# SCH_Aladdin_Flight_Controller_FC-H7_Easy.net
KiCad netlist of a schematic drawn in EasyEDA
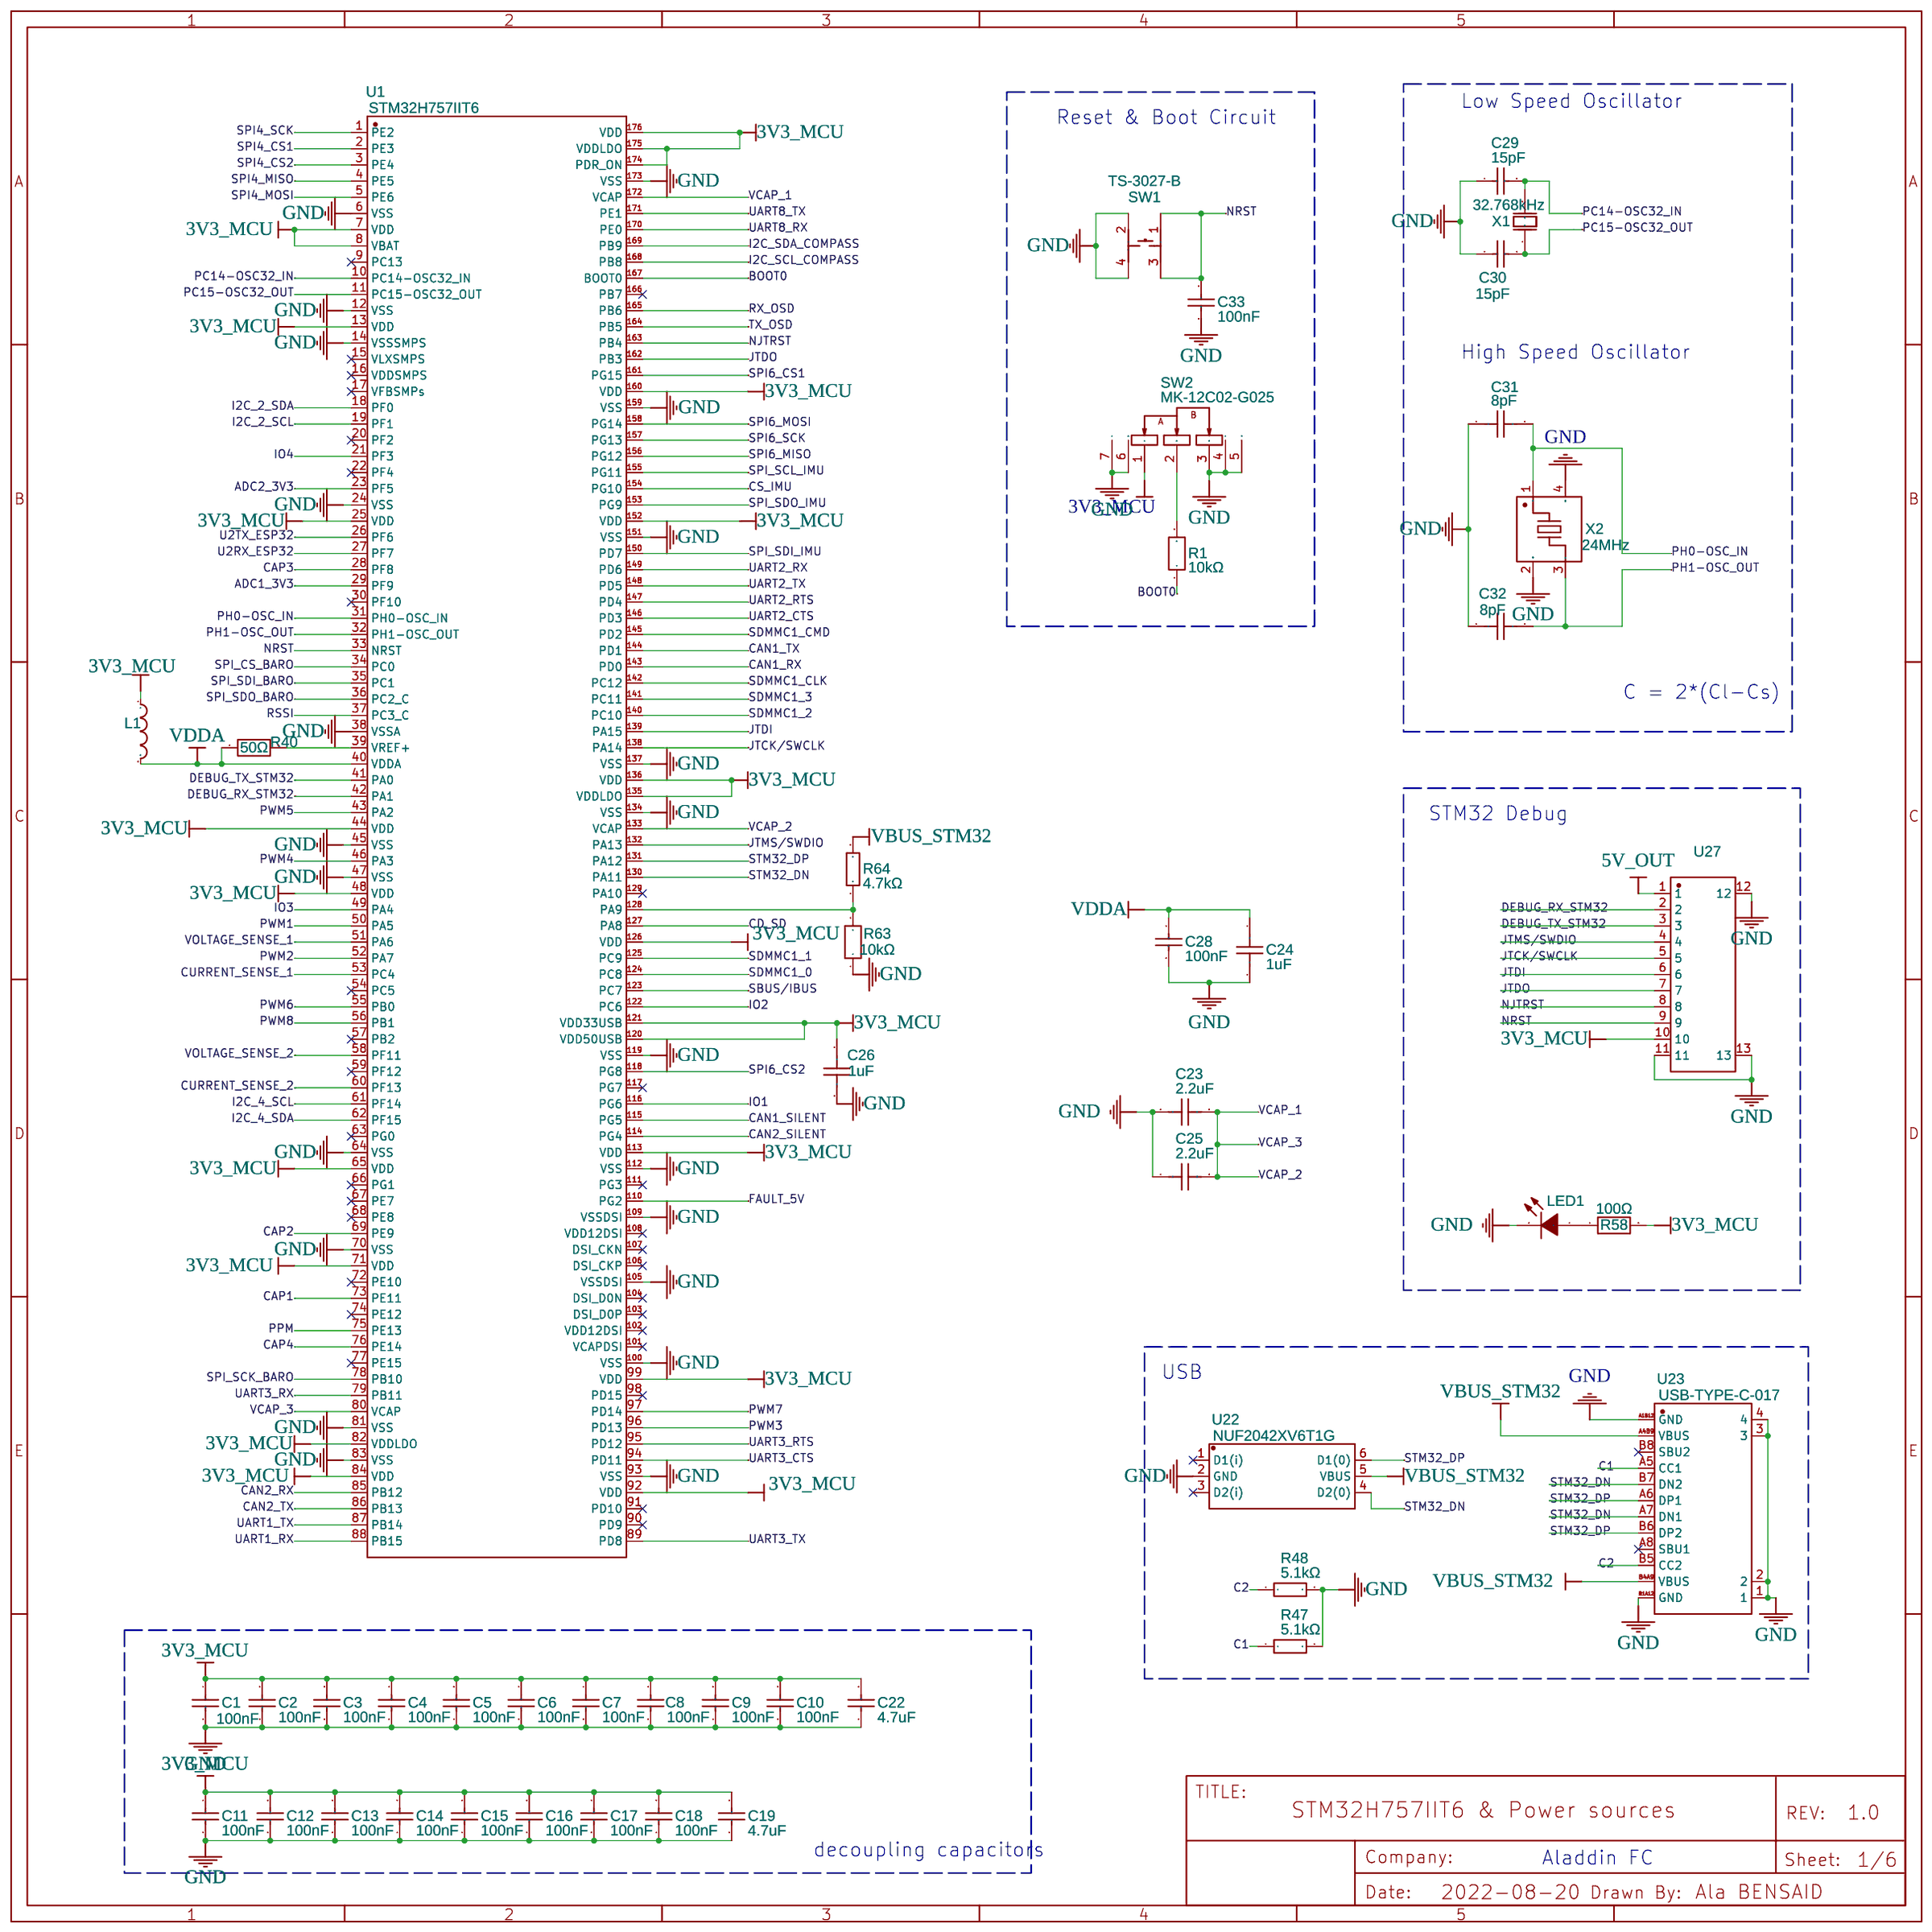
[diagram p0: STM32H757IIT6]
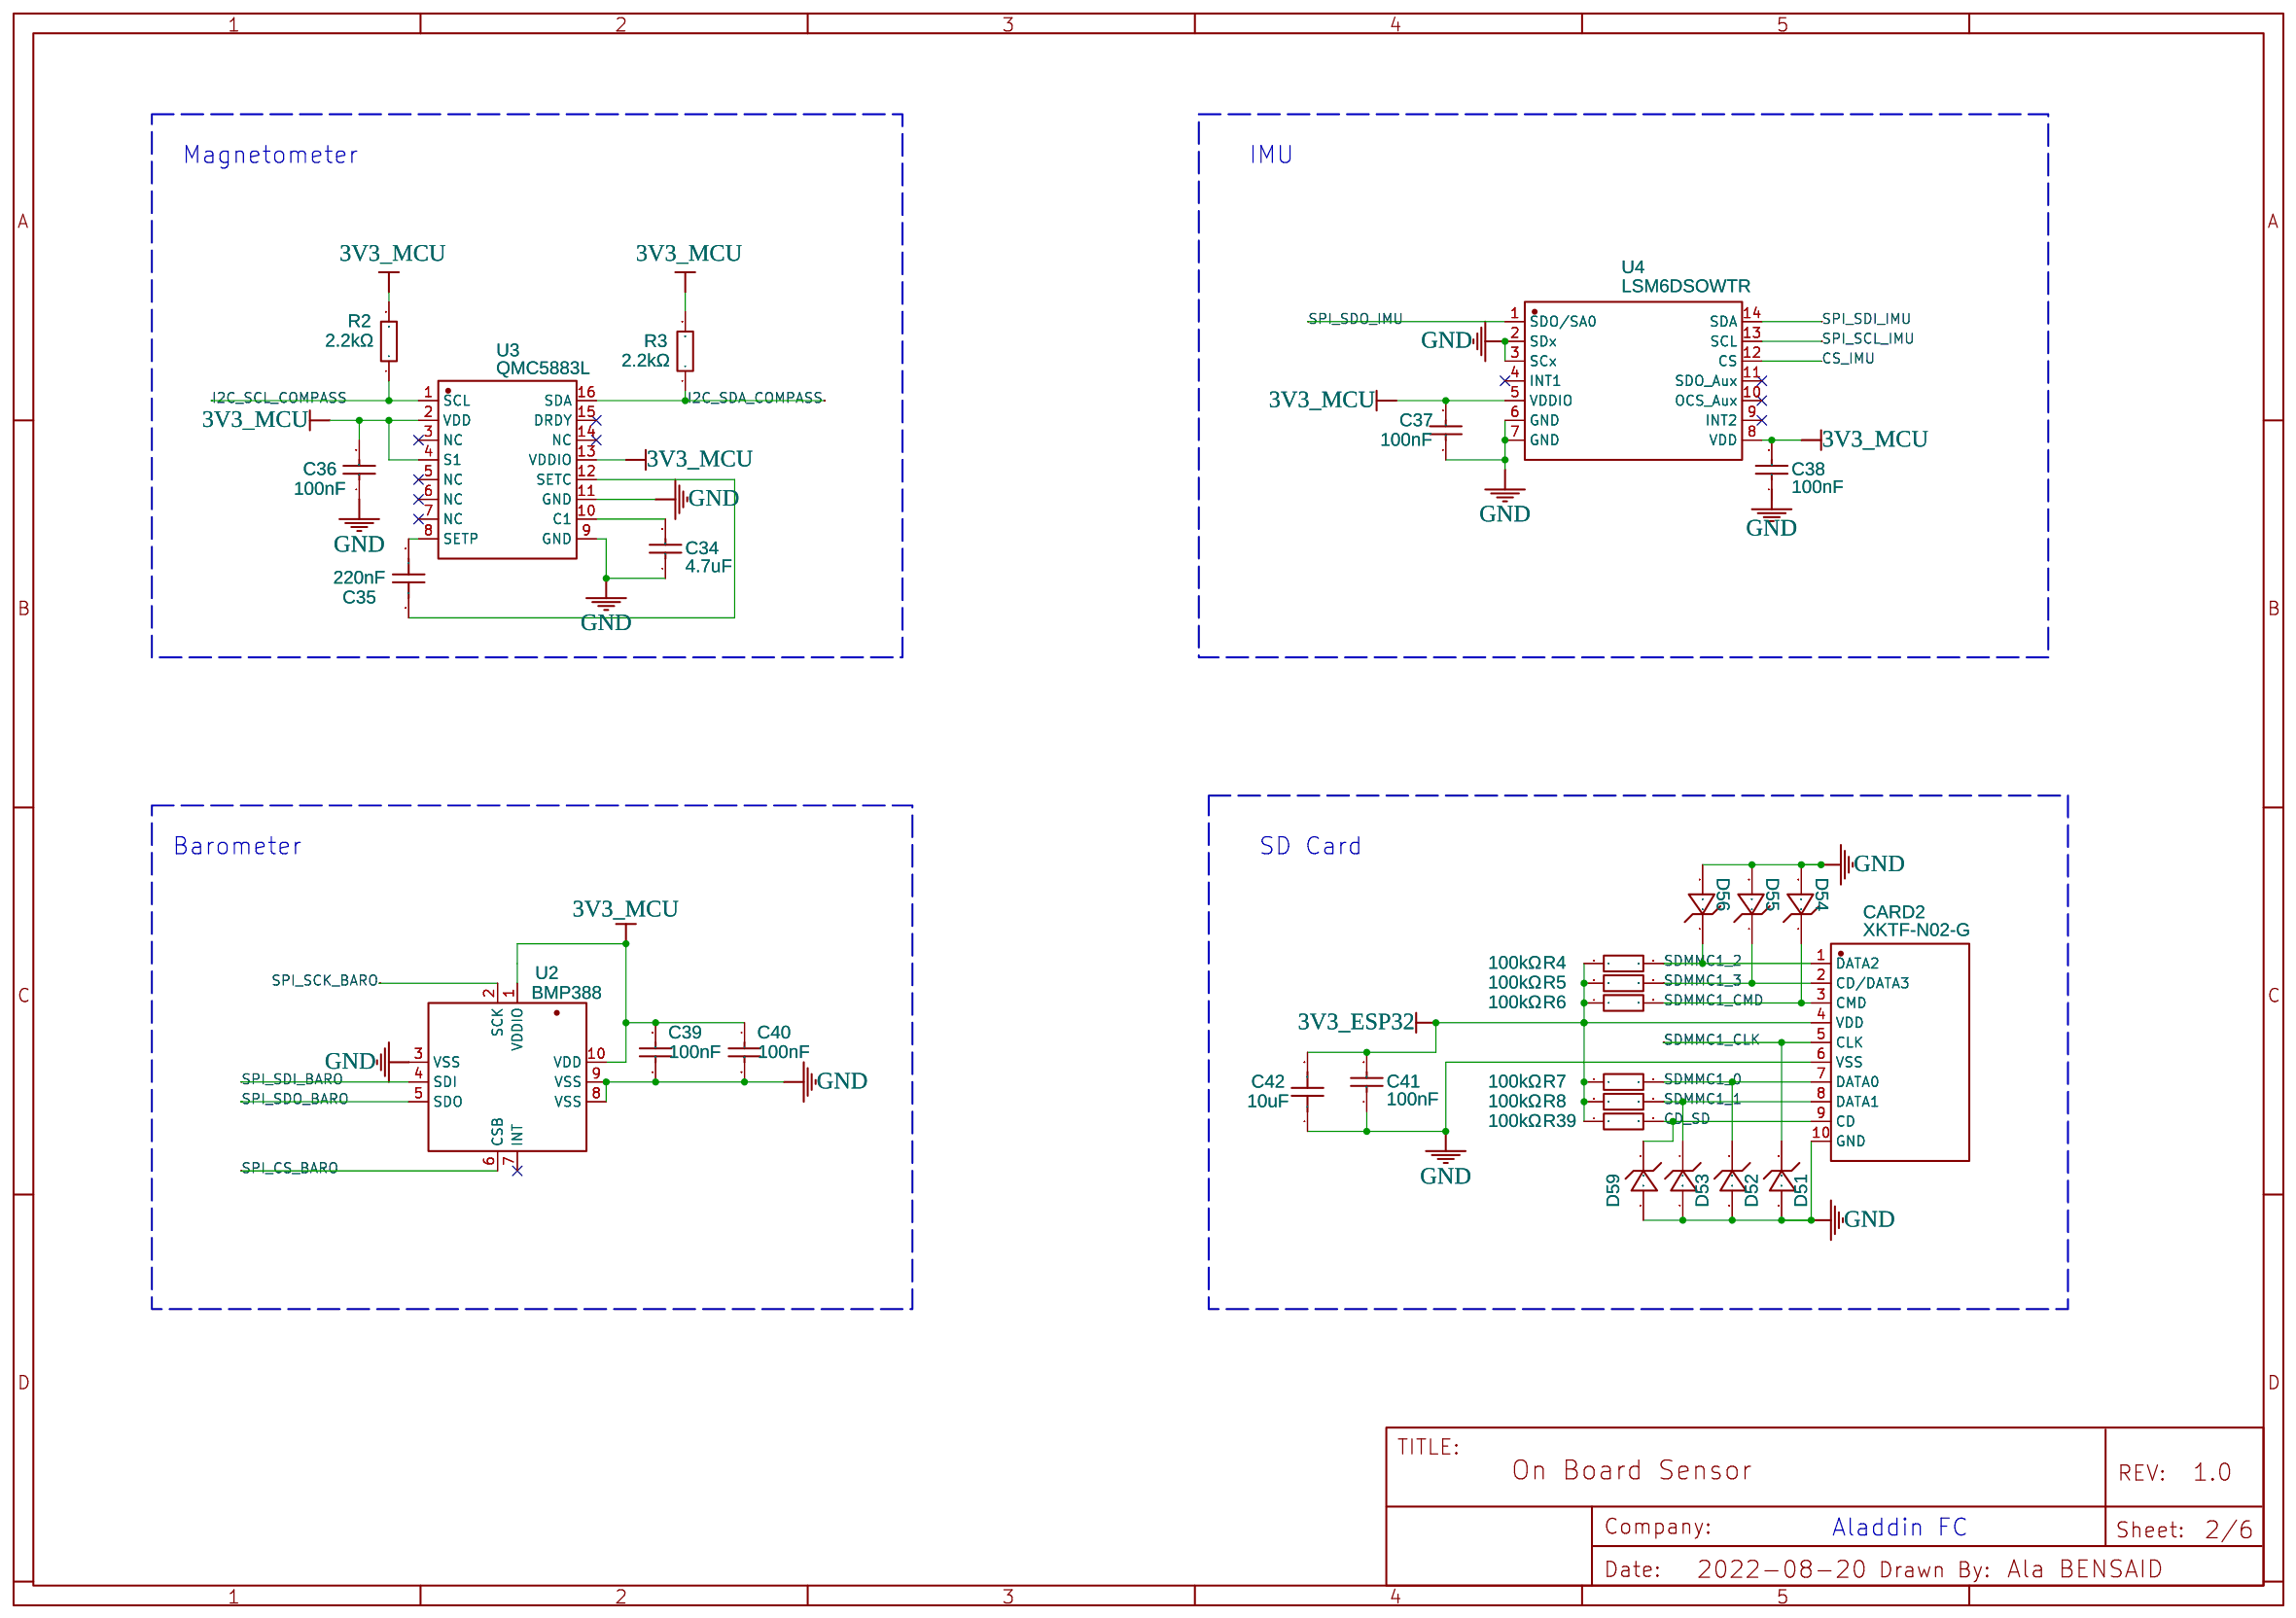
[diagram p1: On Board Sensor]
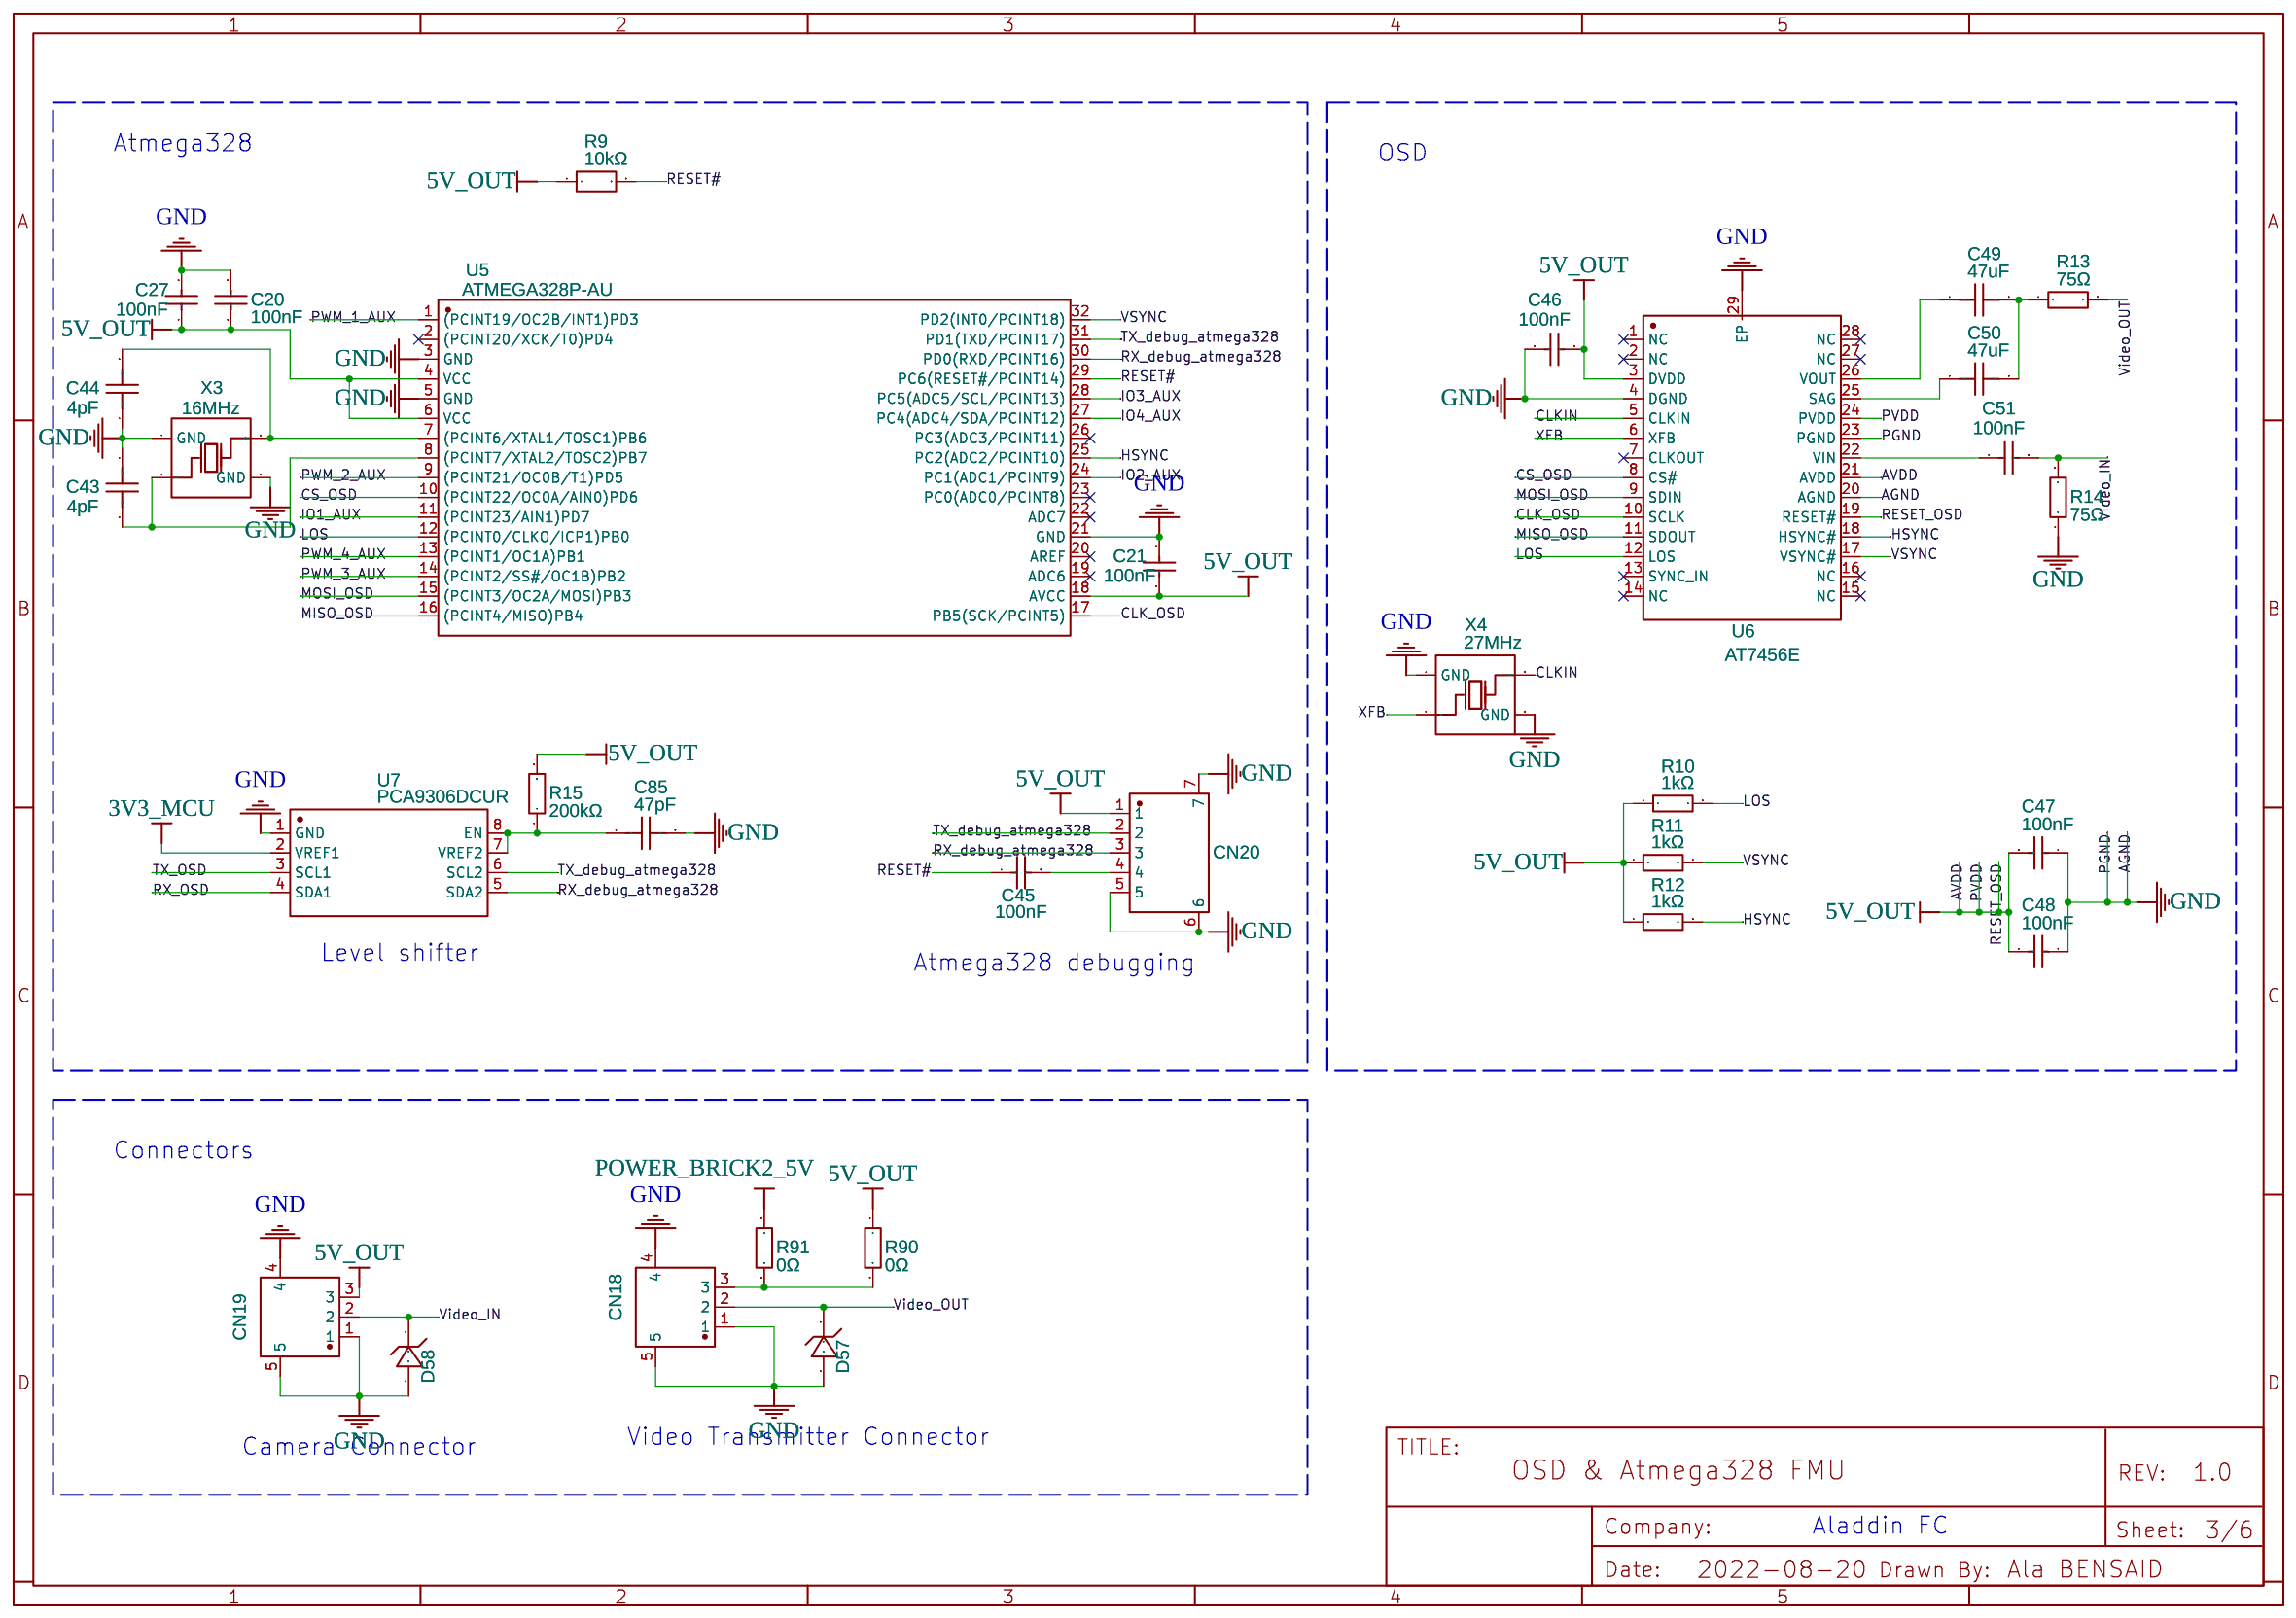
[diagram p2: OSD]
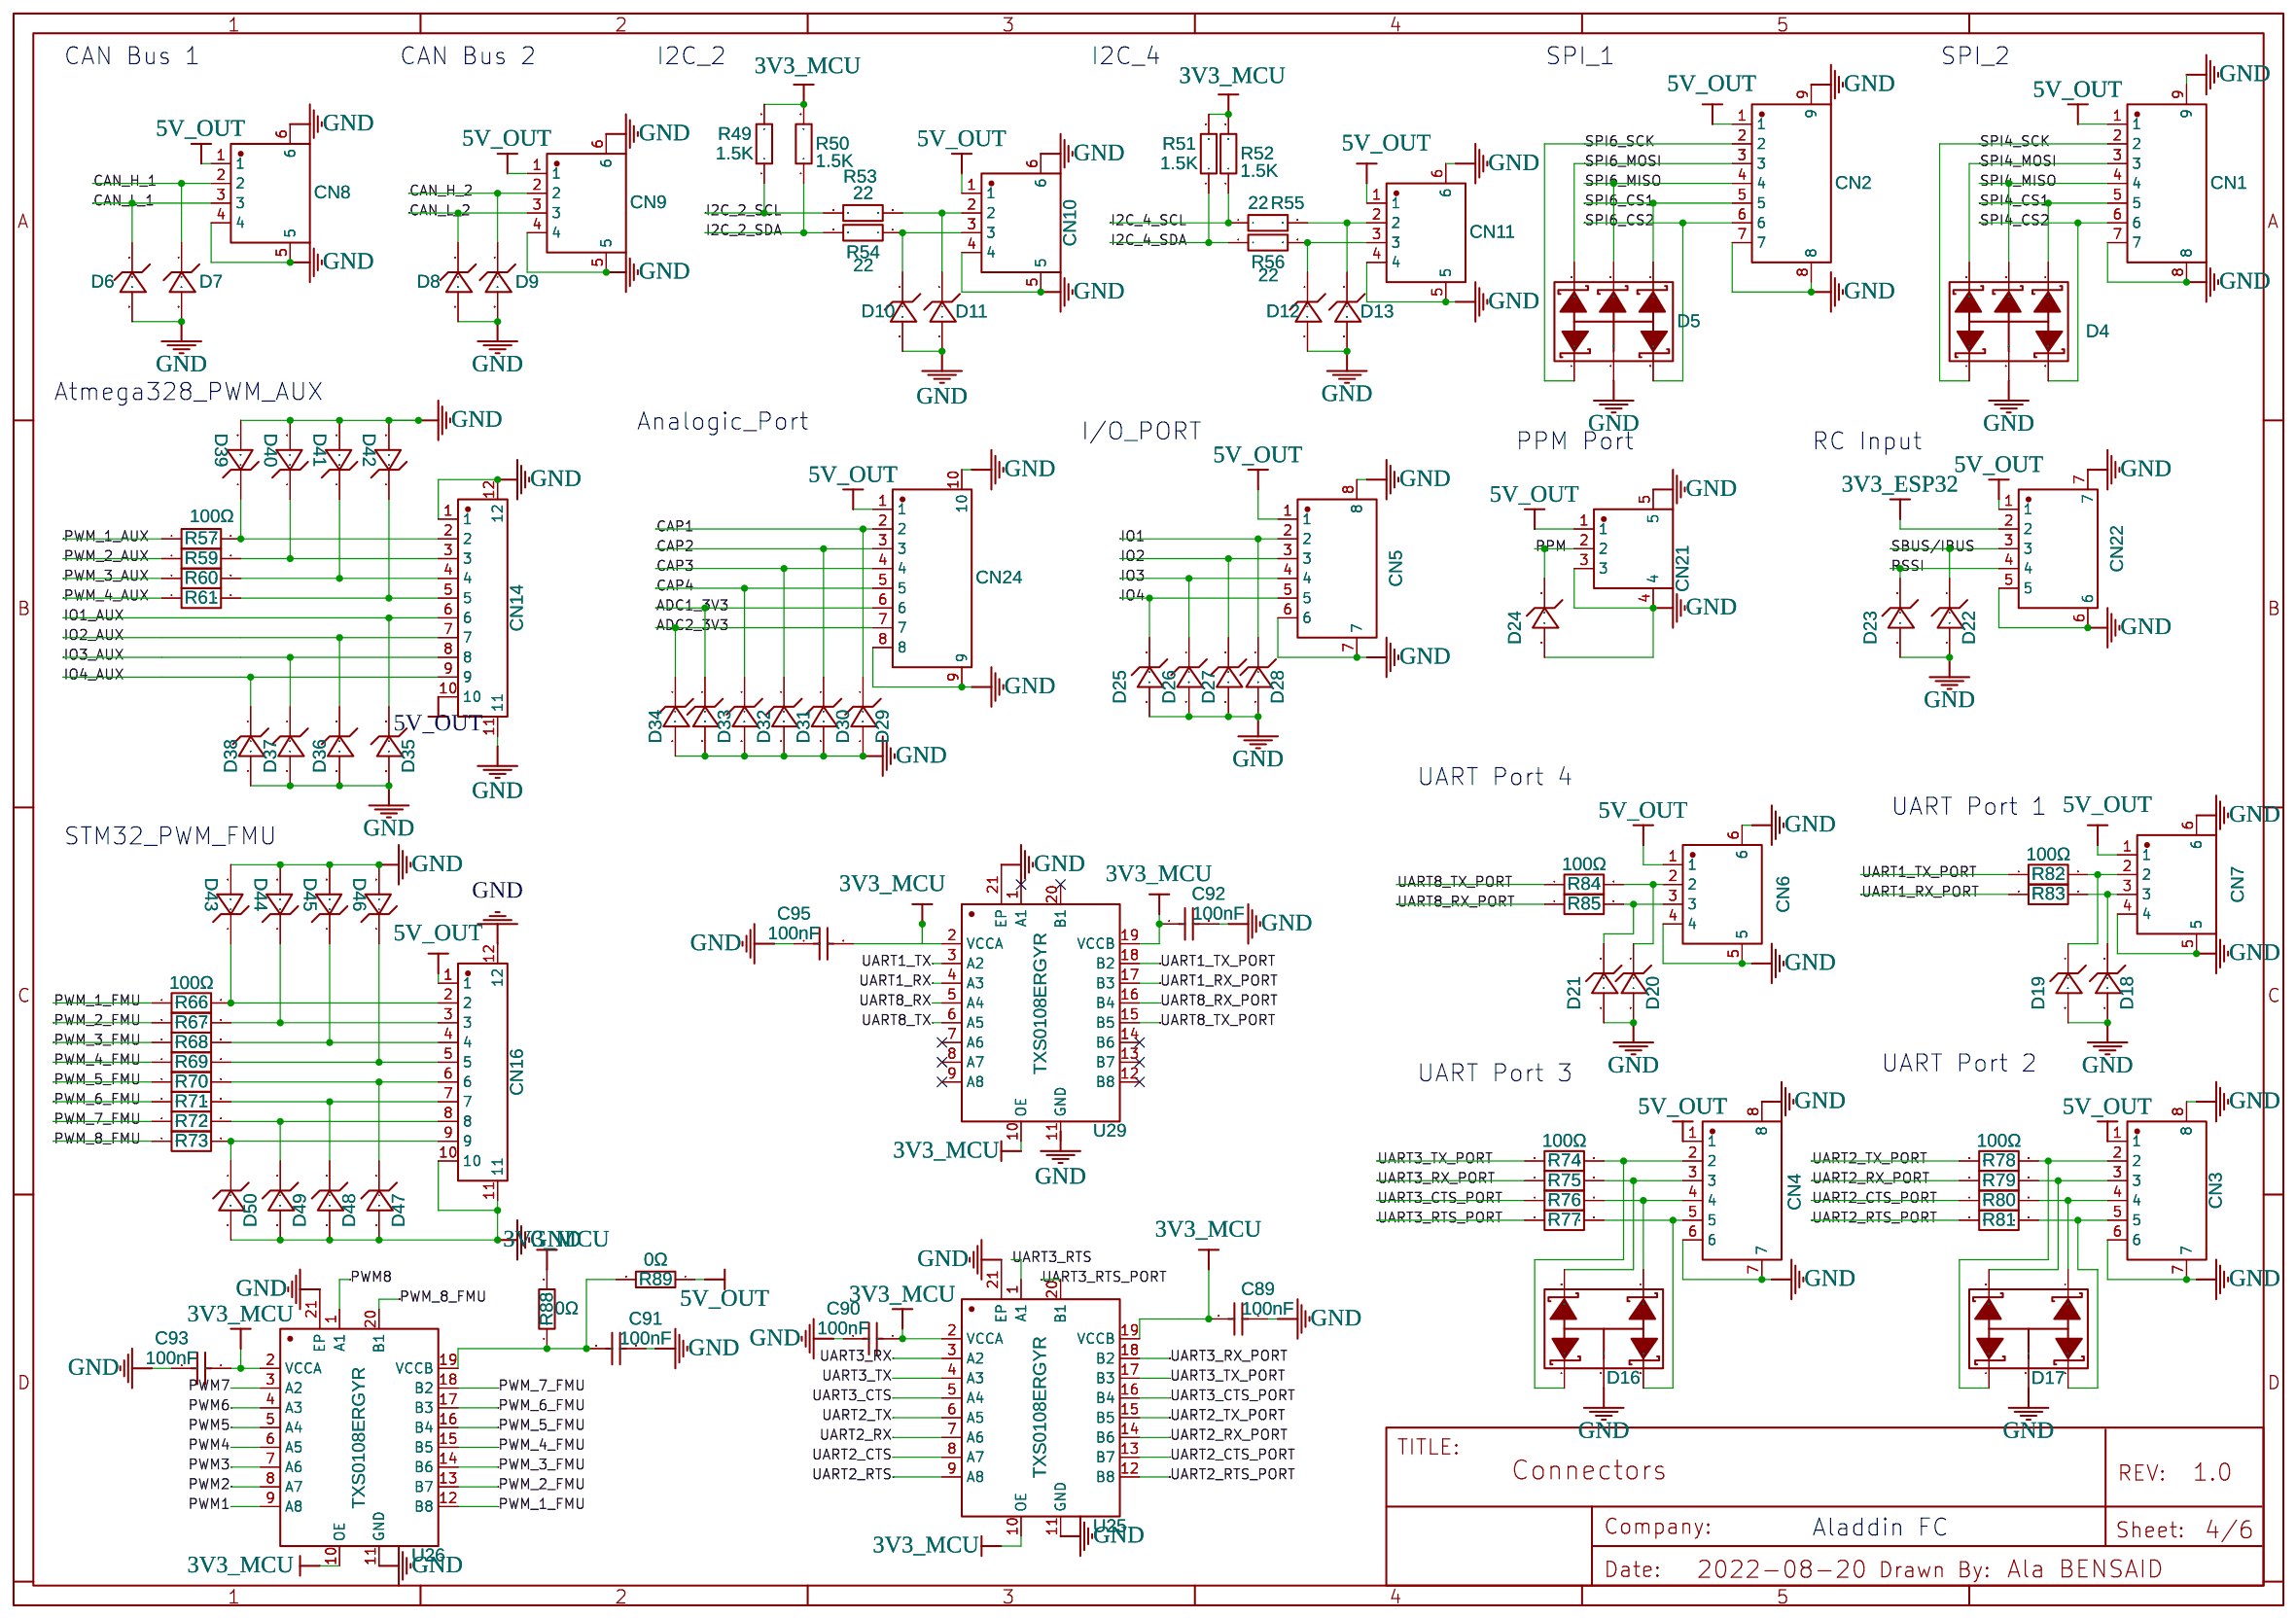
[diagram p3: Connectors]
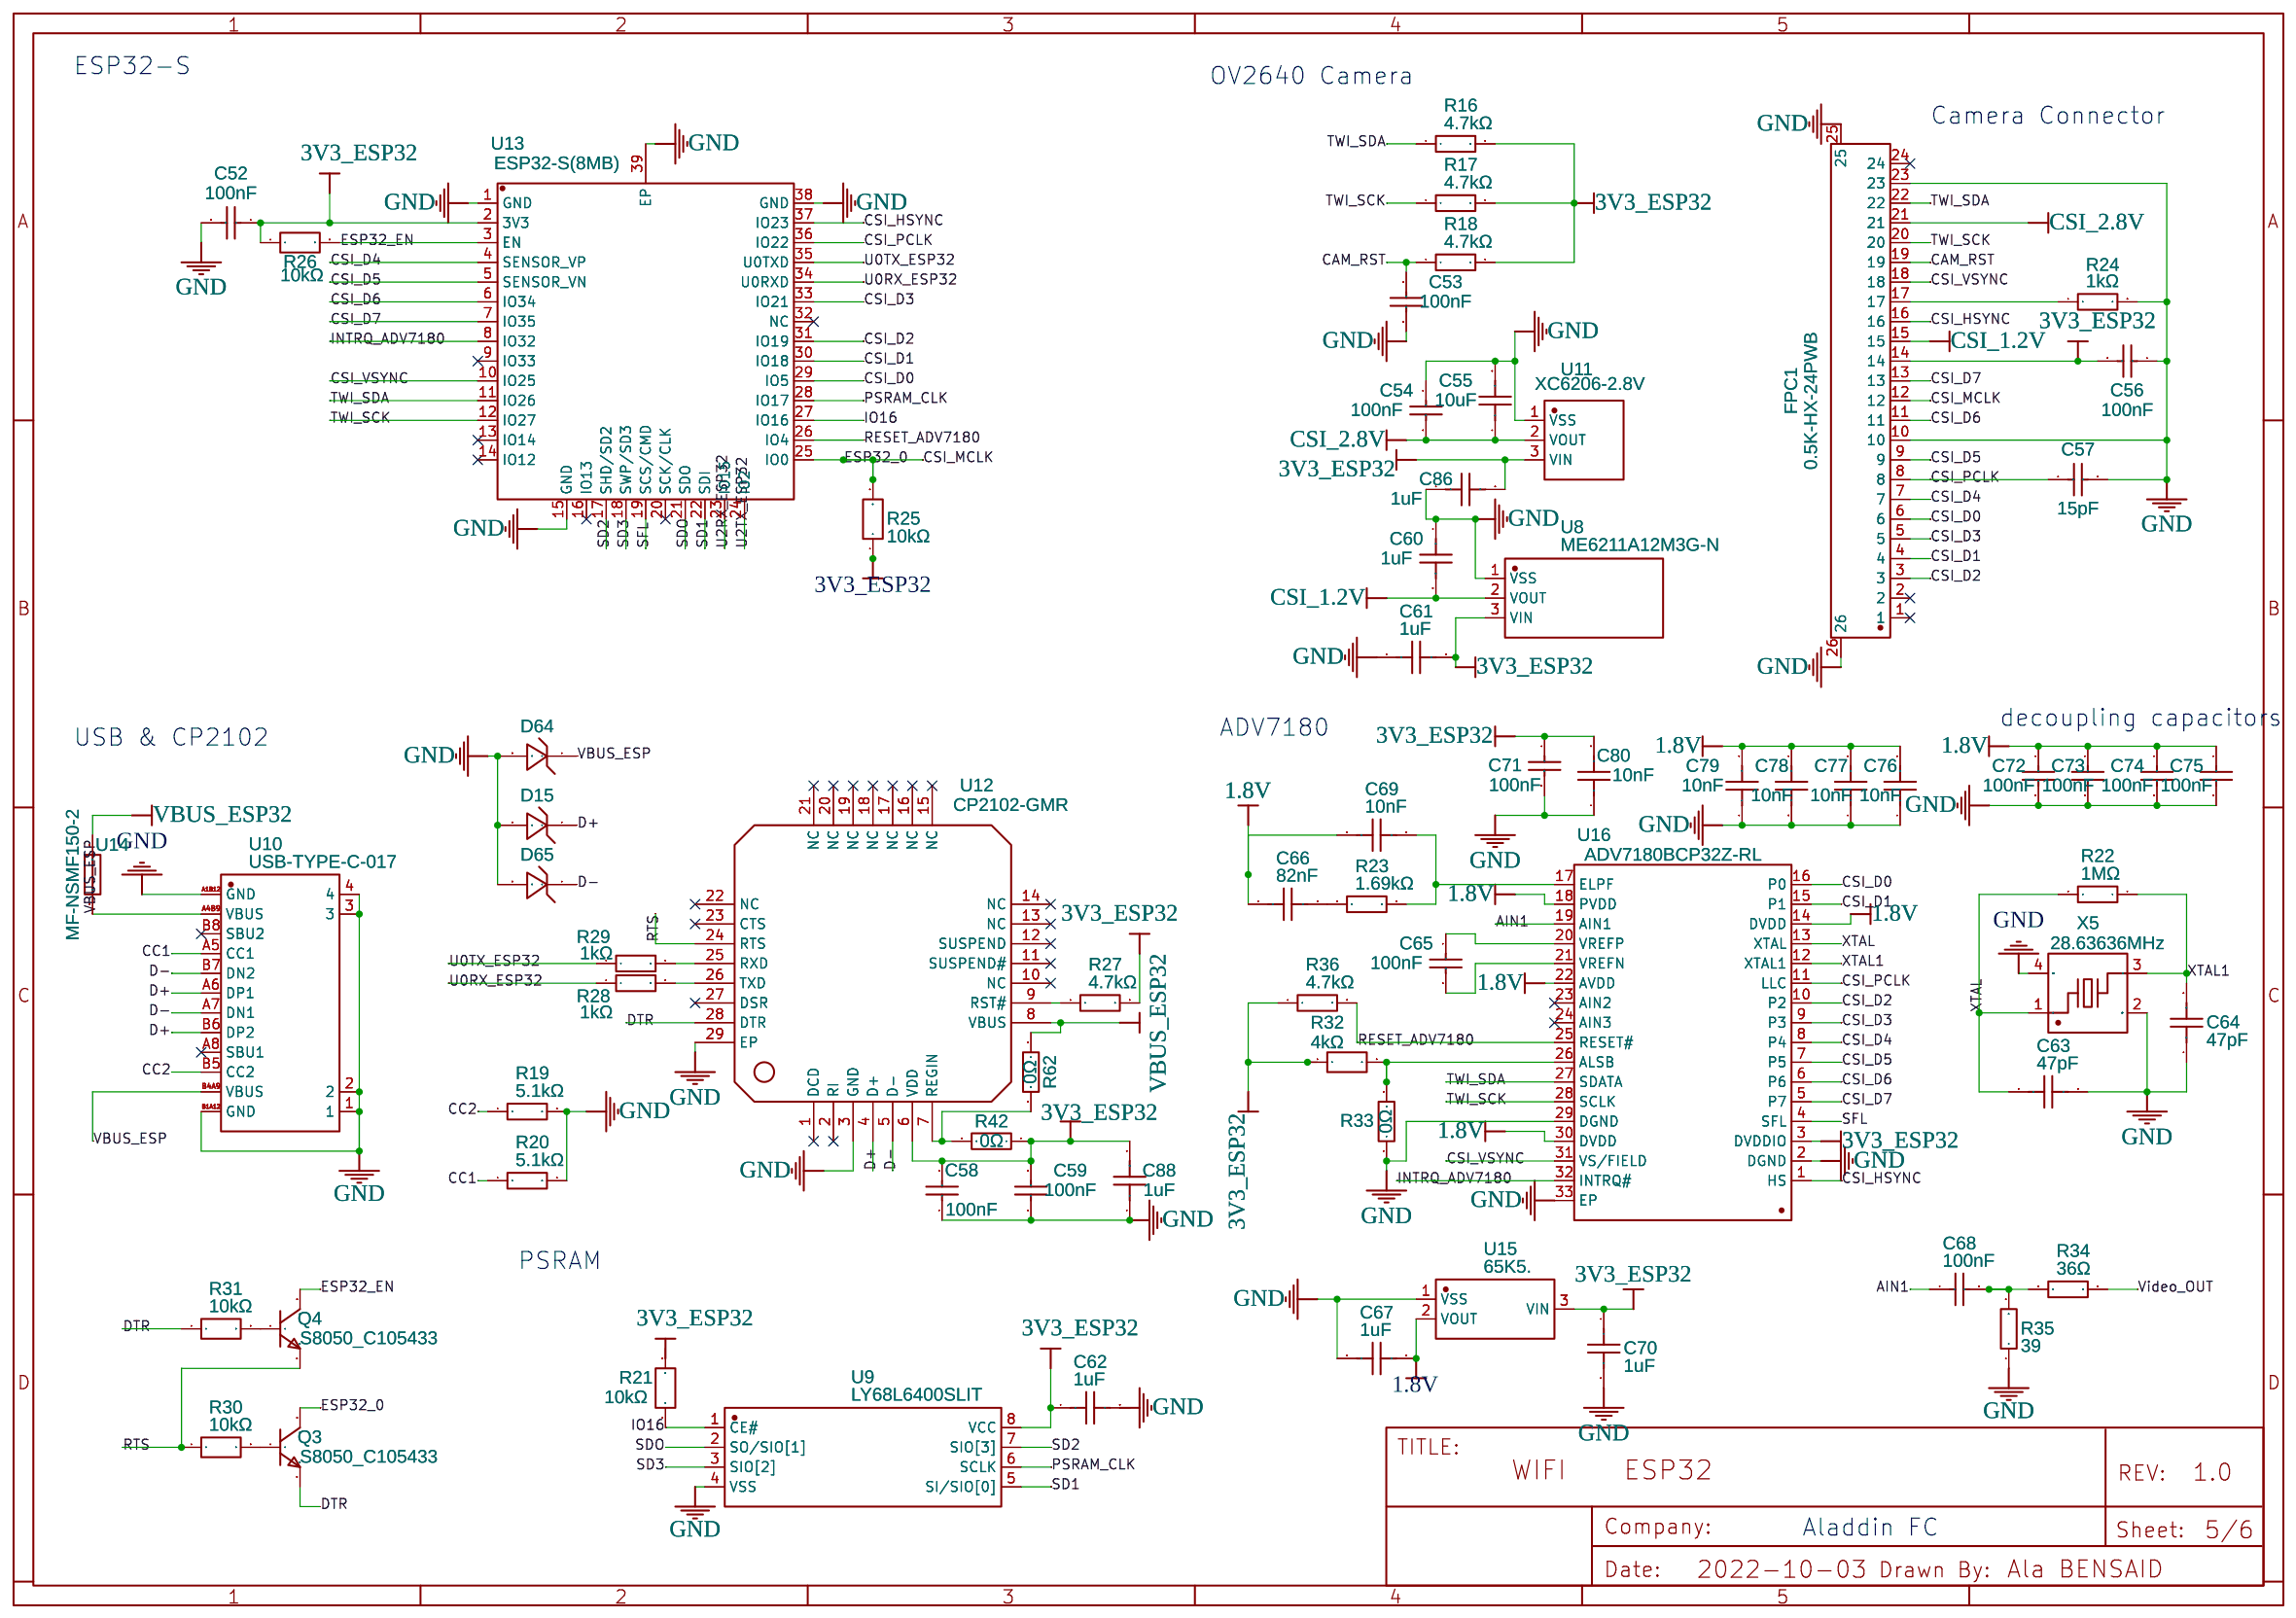
[diagram p4: WIFI ESP32]
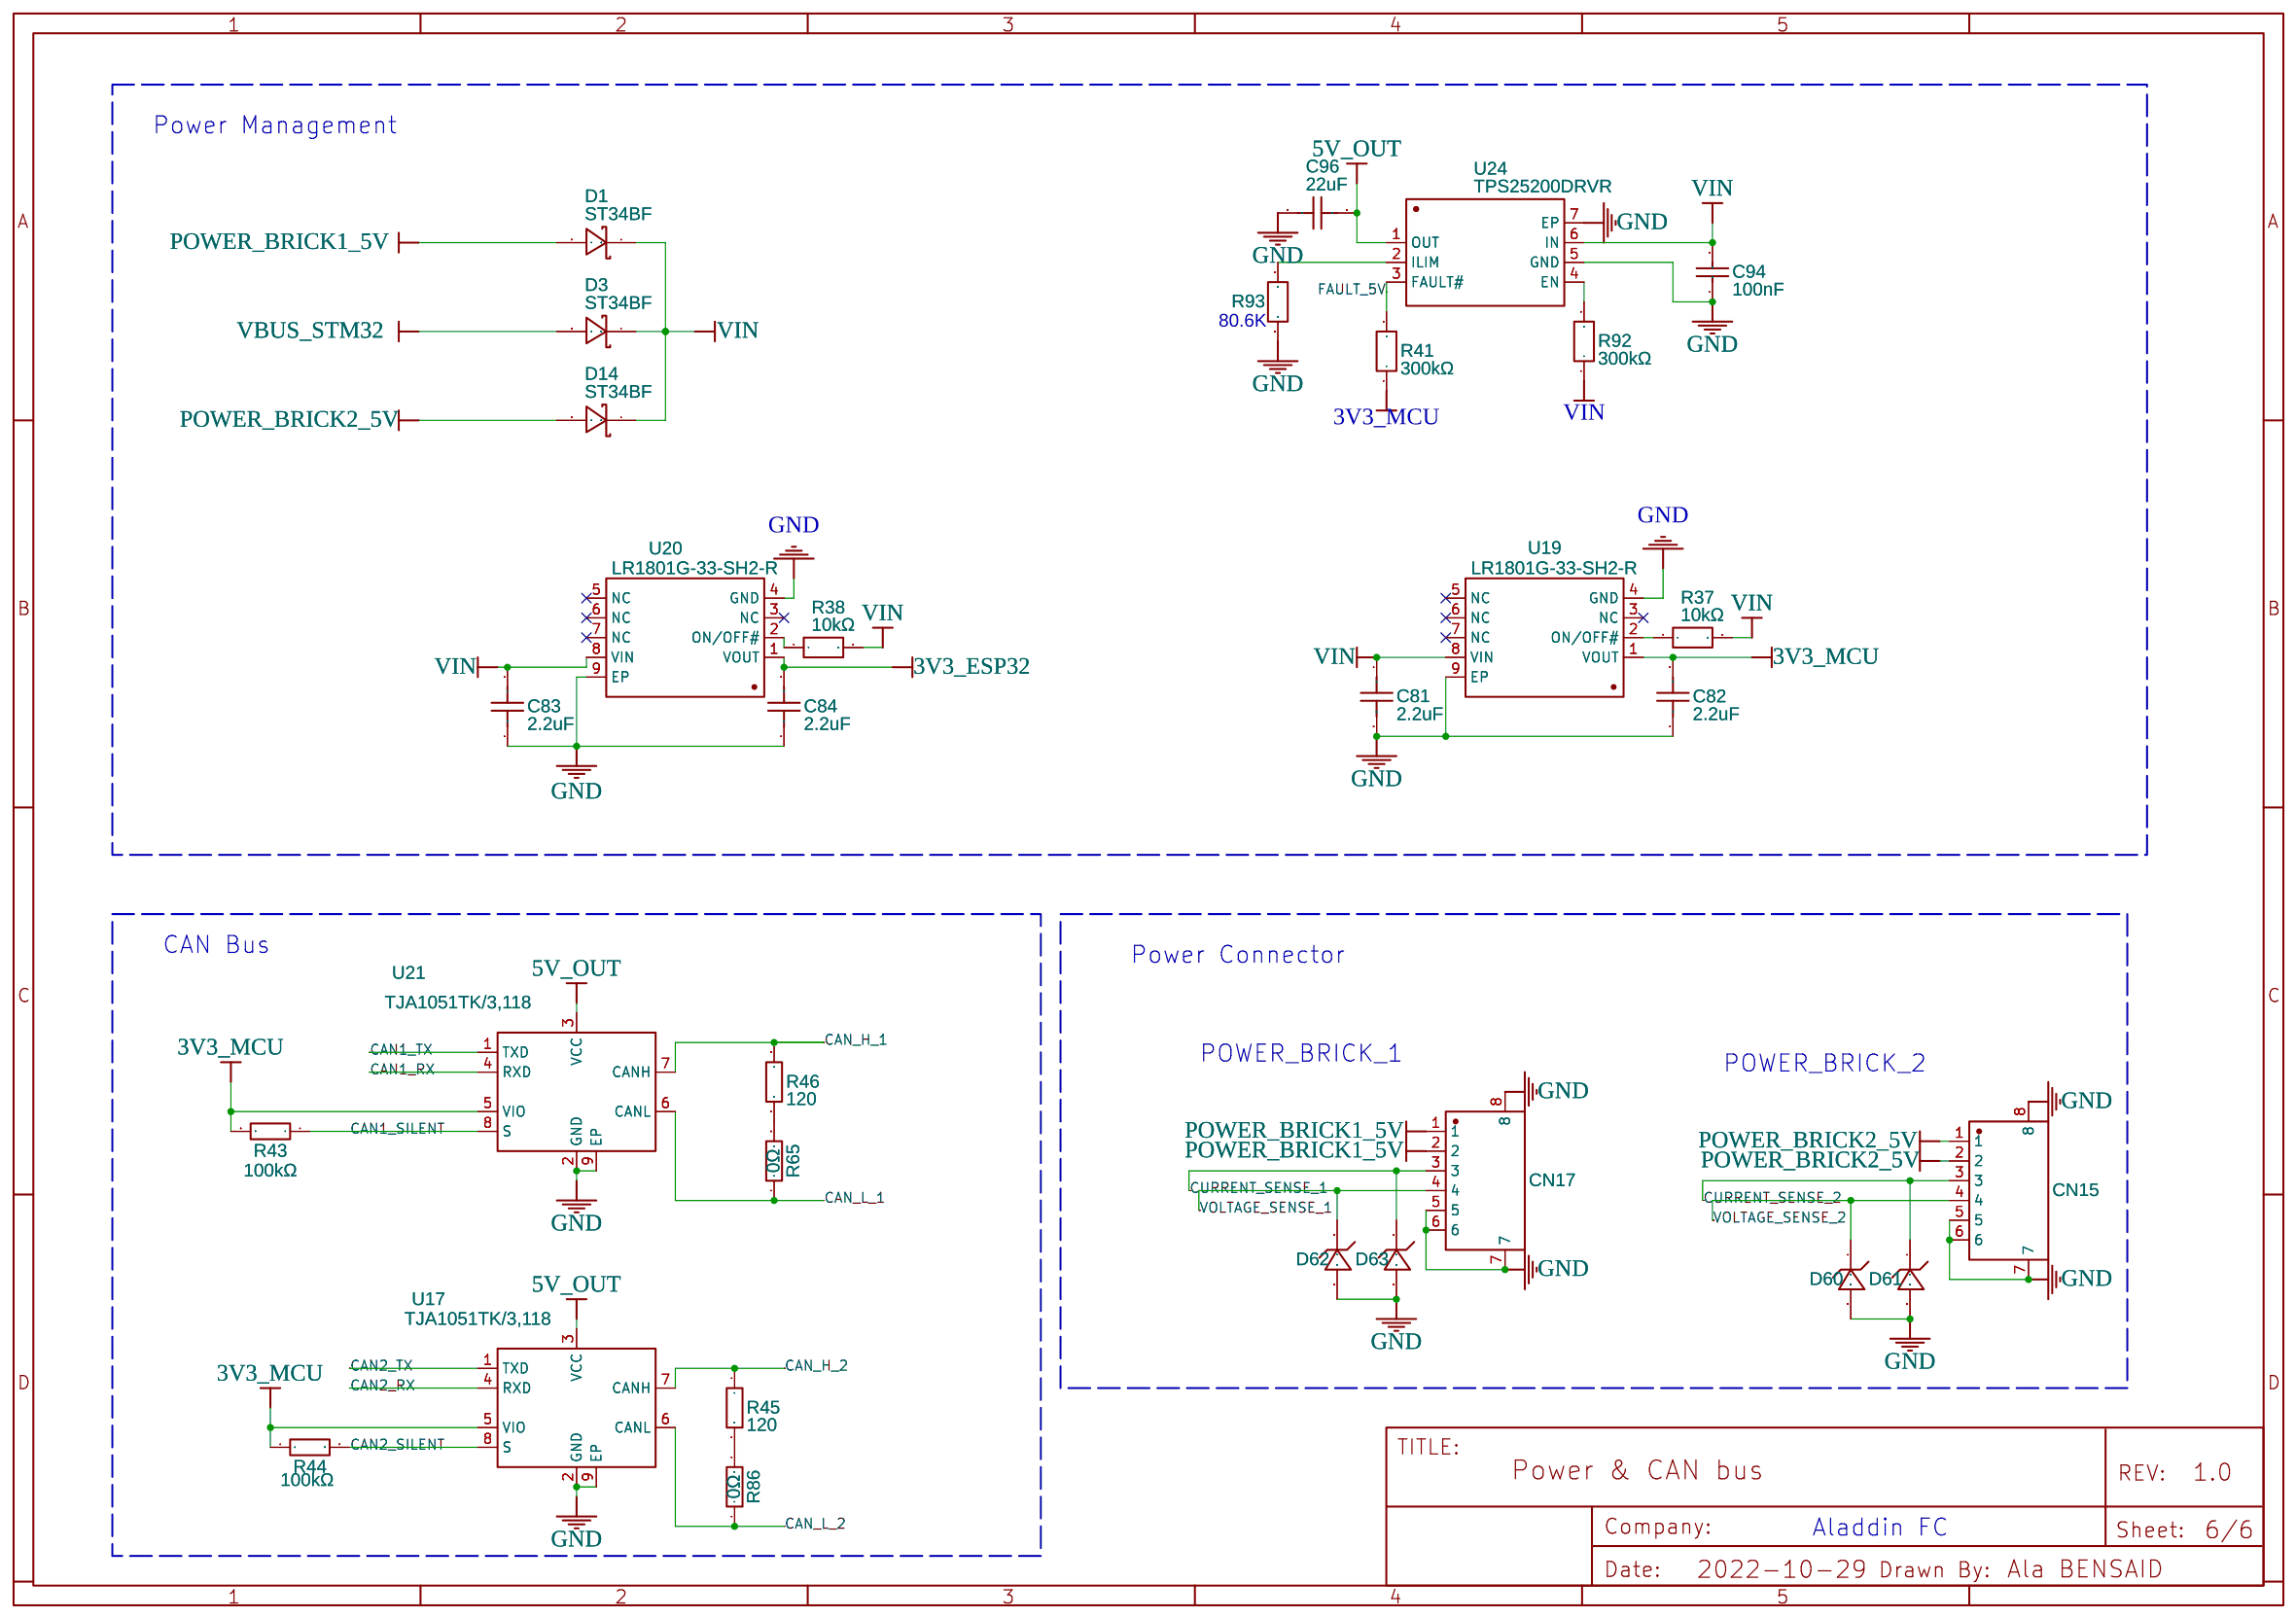
[diagram p5: Power & CAN bus]

(export (version "E")
  (design (tool "Eeschema 10.0.6"))
  (components
    (comp (ref "C1")
      (value "100nF")
      (fields
        (field (name "BOM_Manufacturer Part") "CL21B104KBCNNNC")
        (field (name "BOM_Supplier Part") "C1711")
      )
      (libsource (lib "") (part "CL21B104KBCNNNC"))
    )
    (comp (ref "C2")
      (value "100nF")
      (fields
        (field (name "BOM_Manufacturer Part") "CL21B104KBCNNNC")
        (field (name "BOM_Supplier Part") "C1711")
      )
      (libsource (lib "") (part "CL21B104KBCNNNC_1"))
    )
    (comp (ref "C3")
      (value "100nF")
      (fields
        (field (name "BOM_Manufacturer Part") "CL21B104KBCNNNC")
        (field (name "BOM_Supplier Part") "C1711")
      )
      (libsource (lib "") (part "CL21B104KBCNNNC_1"))
    )
    (comp (ref "C4")
      (value "100nF")
      (fields
        (field (name "BOM_Manufacturer Part") "CL21B104KBCNNNC")
        (field (name "BOM_Supplier Part") "C1711")
      )
      (libsource (lib "") (part "CL21B104KBCNNNC_1"))
    )
    (comp (ref "C5")
      (value "100nF")
      (fields
        (field (name "BOM_Manufacturer Part") "CL21B104KBCNNNC")
        (field (name "BOM_Supplier Part") "C1711")
      )
      (libsource (lib "") (part "CL21B104KBCNNNC_1"))
    )
    (comp (ref "C6")
      (value "100nF")
      (fields
        (field (name "BOM_Manufacturer Part") "CL21B104KBCNNNC")
        (field (name "BOM_Supplier Part") "C1711")
      )
      (libsource (lib "") (part "CL21B104KBCNNNC_1"))
    )
    (comp (ref "C7")
      (value "100nF")
      (fields
        (field (name "BOM_Manufacturer Part") "CL21B104KBCNNNC")
        (field (name "BOM_Supplier Part") "C1711")
      )
      (libsource (lib "") (part "CL21B104KBCNNNC"))
    )
    (comp (ref "C8")
      (value "100nF")
      (fields
        (field (name "BOM_Manufacturer Part") "CL21B104KBCNNNC")
        (field (name "BOM_Supplier Part") "C1711")
      )
      (libsource (lib "") (part "CL21B104KBCNNNC_1"))
    )
    (comp (ref "C9")
      (value "100nF")
      (fields
        (field (name "BOM_Manufacturer Part") "CL21B104KBCNNNC")
        (field (name "BOM_Supplier Part") "C1711")
      )
      (libsource (lib "") (part "CL21B104KBCNNNC_1"))
    )
    (comp (ref "C10")
      (value "100nF")
      (fields
        (field (name "BOM_Manufacturer Part") "CL21B104KBCNNNC")
        (field (name "BOM_Supplier Part") "C1711")
      )
      (libsource (lib "") (part "CL21B104KBCNNNC_1"))
    )
    (comp (ref "C11")
      (value "100nF")
      (fields
        (field (name "BOM_Manufacturer Part") "CL21B104KBCNNNC")
        (field (name "BOM_Supplier Part") "C1711")
      )
      (libsource (lib "") (part "CL21B104KBCNNNC"))
    )
    (comp (ref "C12")
      (value "100nF")
      (fields
        (field (name "BOM_Manufacturer Part") "CL21B104KBCNNNC")
        (field (name "BOM_Supplier Part") "C1711")
      )
      (libsource (lib "") (part "CL21B104KBCNNNC_1"))
    )
    (comp (ref "C13")
      (value "100nF")
      (fields
        (field (name "BOM_Manufacturer Part") "CL21B104KBCNNNC")
        (field (name "BOM_Supplier Part") "C1711")
      )
      (libsource (lib "") (part "CL21B104KBCNNNC_1"))
    )
    (comp (ref "C14")
      (value "100nF")
      (fields
        (field (name "BOM_Manufacturer Part") "CL21B104KBCNNNC")
        (field (name "BOM_Supplier Part") "C1711")
      )
      (libsource (lib "") (part "CL21B104KBCNNNC_1"))
    )
    (comp (ref "C15")
      (value "100nF")
      (fields
        (field (name "BOM_Manufacturer Part") "CL21B104KBCNNNC")
        (field (name "BOM_Supplier Part") "C1711")
      )
      (libsource (lib "") (part "CL21B104KBCNNNC_1"))
    )
    (comp (ref "C16")
      (value "100nF")
      (fields
        (field (name "BOM_Manufacturer Part") "CL21B104KBCNNNC")
        (field (name "BOM_Supplier Part") "C1711")
      )
      (libsource (lib "") (part "CL21B104KBCNNNC_1"))
    )
    (comp (ref "C17")
      (value "100nF")
      (fields
        (field (name "BOM_Manufacturer Part") "CL21B104KBCNNNC")
        (field (name "BOM_Supplier Part") "C1711")
      )
      (libsource (lib "") (part "CL21B104KBCNNNC"))
    )
    (comp (ref "C18")
      (value "100nF")
      (fields
        (field (name "BOM_Manufacturer Part") "CL21B104KBCNNNC")
        (field (name "BOM_Supplier Part") "C1711")
      )
      (libsource (lib "") (part "CL21B104KBCNNNC_1"))
    )
    (comp (ref "C19")
      (value "4.7uF")
      (fields
        (field (name "BOM_Manufacturer Part") "CL21B475KAFNNNE")
        (field (name "BOM_Supplier Part") "C98195")
      )
      (libsource (lib "") (part "CL21B475KAFNNNE"))
    )
    (comp (ref "C22")
      (value "4.7uF")
      (fields
        (field (name "BOM_Manufacturer Part") "CL21B475KAFNNNE")
        (field (name "BOM_Supplier Part") "C98195")
      )
      (libsource (lib "") (part "CL21B475KAFNNNE"))
    )
    (comp (ref "C23")
      (value "2.2uF")
      (fields
        (field (name "BOM_Manufacturer Part") "CS2012X5R225K500NRE")
        (field (name "BOM_Supplier Part") "C513763")
      )
      (libsource (lib "") (part "CS2012X5R225K500NRE"))
    )
    (comp (ref "C24")
      (value "1uF")
      (fields
        (field (name "BOM_Manufacturer Part") "UMK212BJ105KG-T")
        (field (name "BOM_Supplier Part") "C319195")
      )
      (libsource (lib "") (part "UMK212BJ105KG-T"))
    )
    (comp (ref "C25")
      (value "2.2uF")
      (fields
        (field (name "BOM_Manufacturer Part") "CS2012X5R225K500NRE")
        (field (name "BOM_Supplier Part") "C513763")
      )
      (libsource (lib "") (part "CS2012X5R225K500NRE"))
    )
    (comp (ref "C26")
      (value "1uF")
      (fields
        (field (name "BOM_Manufacturer Part") "UMK212BJ105KG-T")
        (field (name "BOM_Supplier Part") "C319195")
      )
      (libsource (lib "") (part "UMK212BJ105KG-T"))
    )
    (comp (ref "C28")
      (value "100nF")
      (fields
        (field (name "BOM_Manufacturer Part") "CL21B104KBCNNNC")
        (field (name "BOM_Supplier Part") "C1711")
      )
      (libsource (lib "") (part "CL21B104KBCNNNC"))
    )
    (comp (ref "C29")
      (value "15pF")
      (fields
        (field (name "BOM_Manufacturer Part") "CL10C150JB8NNNC")
        (field (name "BOM_Supplier Part") "C1644")
      )
      (libsource (lib "") (part "CL10C150JB8NNNC"))
    )
    (comp (ref "C30")
      (value "15pF")
      (fields
        (field (name "BOM_Manufacturer Part") "CL10C150JB8NNNC")
        (field (name "BOM_Supplier Part") "C1644")
      )
      (libsource (lib "") (part "CL10C150JB8NNNC"))
    )
    (comp (ref "C31")
      (value "8pF")
      (fields
        (field (name "BOM_Manufacturer Part") "CL21C080DBANNNC")
        (field (name "BOM_Supplier Part") "C170111")
      )
      (libsource (lib "") (part "CL21C080DBANNNC"))
    )
    (comp (ref "C32")
      (value "8pF")
      (fields
        (field (name "BOM_Manufacturer Part") "CL21C080DBANNNC")
        (field (name "BOM_Supplier Part") "C170111")
      )
      (libsource (lib "") (part "CL21C080DBANNNC"))
    )
    (comp (ref "C33")
      (value "100nF")
      (fields
        (field (name "BOM_Manufacturer Part") "CL21B104KBCNNNC")
        (field (name "BOM_Supplier Part") "C1711")
      )
      (libsource (lib "") (part "CL21B104KBCNNNC_1"))
    )
    (comp (ref "L1")
      (value "FCM1005KF-601T03")
      (fields (field (name "BOM_Supplier Part") "C427432"))
      (libsource (lib "") (part "FCM1005KF-601T03"))
    )
    (comp (ref "LED1")
      (value "SZYY0805B")
      (fields (field (name "BOM_Supplier Part") "C434433"))
      (libsource (lib "") (part "SZYY0805B"))
    )
    (comp (ref "R1")
      (value "10kΩ")
      (fields
        (field (name "BOM_Manufacturer Part") "ARG05BTC1002")
        (field (name "BOM_Supplier Part") "C406725")
      )
      (libsource (lib "") (part "ARG05BTC1002"))
    )
    (comp (ref "R40")
      (value "50Ω")
      (fields
        (field (name "BOM_Manufacturer Part") "ARG05FTC0500")
        (field (name "BOM_Supplier Part") "C2828866")
      )
      (libsource (lib "") (part "ARG05FTC0500"))
    )
    (comp (ref "R47")
      (value "5.1kΩ")
      (fields
        (field (name "BOM_Manufacturer Part") "RMC04025.1K5%N")
        (field (name "BOM_Supplier Part") "C325524")
      )
      (libsource (lib "") (part "RMC04025.1K5%N"))
    )
    (comp (ref "R48")
      (value "5.1kΩ")
      (fields
        (field (name "BOM_Manufacturer Part") "RMC04025.1K5%N")
        (field (name "BOM_Supplier Part") "C325524")
      )
      (libsource (lib "") (part "RMC04025.1K5%N"))
    )
    (comp (ref "R58")
      (value "100Ω")
      (fields
        (field (name "BOM_Manufacturer Part") "FRC0603J101 TS")
        (field (name "BOM_Supplier Part") "C2907089")
      )
      (libsource (lib "") (part "FRC0603J101 TS"))
    )
    (comp (ref "R63")
      (value "10kΩ")
      (fields
        (field (name "BOM_Manufacturer Part") "ARG05BTC1002")
        (field (name "BOM_Supplier Part") "C406725")
      )
      (libsource (lib "") (part "ARG05BTC1002"))
    )
    (comp (ref "R64")
      (value "4.7kΩ")
      (fields
        (field (name "BOM_Manufacturer Part") "RMC08054.7K1%N")
        (field (name "BOM_Supplier Part") "C269746")
      )
      (libsource (lib "") (part "RMC08054.7K1%N"))
    )
    (comp (ref "SW1")
      (value "TS-3027-B")
      (fields (field (name "BOM_Supplier Part") "C561482"))
      (libsource (lib "") (part "TS-3027-B"))
    )
    (comp (ref "SW2")
      (value "MK-12C02-G025")
      (fields (field (name "BOM_Supplier Part") "C778186"))
      (libsource (lib "") (part "MK-12C02-G025"))
    )
    (comp (ref "U1")
      (value "STM32H757IIT6")
      (fields (field (name "BOM_Supplier Part") "C730215"))
      (libsource (lib "") (part "STM32H757IIT6"))
    )
    (comp (ref "U22")
      (value "NUF2042XV6T1G")
      (fields (field (name "BOM_Supplier Part") "C90707"))
      (libsource (lib "") (part "NUF2042XV6T1G"))
    )
    (comp (ref "U23")
      (value "USB-TYPE-C-017")
      (fields (field (name "BOM_Supplier Part") "C2927037"))
      (libsource (lib "") (part "USB-TYPE-C-017"))
    )
    (comp (ref "U27")
      (value "A1257WR-S-11P")
      (fields (field (name "BOM_Supplier Part") "C272991"))
      (libsource (lib "") (part "A1257WR-S-11P"))
    )
    (comp (ref "X1")
      (value "32.768kHz")
      (fields
        (field (name "BOM_Manufacturer Part") "CM315D32768DZFT")
        (field (name "BOM_Supplier Part") "C182057")
      )
      (libsource (lib "") (part "CM315D32768DZFT"))
    )
    (comp (ref "X2")
      (value "24MHz")
      (fields (field (name "BOM_Manufacturer Part") "TZ1620C") (field (name "BOM_Supplier Part") "C498196"))
      (libsource (lib "") (part "TZ1620C"))
    )
    (comp (ref "C34")
      (value "4.7uF")
      (fields
        (field (name "BOM_Manufacturer Part") "CL21B475KAFNNNE")
        (field (name "BOM_Supplier Part") "C98195")
      )
      (libsource (lib "") (part "CL21B475KAFNNNE"))
    )
    (comp (ref "C35")
      (value "220nF")
      (fields
        (field (name "BOM_Manufacturer Part") "CC0805ZRY5V8BB224")
        (field (name "BOM_Supplier Part") "C327192")
      )
      (libsource (lib "") (part "CC0805ZRY5V8BB224"))
    )
    (comp (ref "C36")
      (value "100nF")
      (fields
        (field (name "BOM_Manufacturer Part") "CL21B104KBCNNNC")
        (field (name "BOM_Supplier Part") "C1711")
      )
      (libsource (lib "") (part "CL21B104KBCNNNC"))
    )
    (comp (ref "C37")
      (value "100nF")
      (fields
        (field (name "BOM_Manufacturer Part") "CL21B104KBCNNNC")
        (field (name "BOM_Supplier Part") "C1711")
      )
      (libsource (lib "") (part "CL21B104KBCNNNC"))
    )
    (comp (ref "C38")
      (value "100nF")
      (fields
        (field (name "BOM_Manufacturer Part") "CL21B104KBCNNNC")
        (field (name "BOM_Supplier Part") "C1711")
      )
      (libsource (lib "") (part "CL21B104KBCNNNC"))
    )
    (comp (ref "C39")
      (value "100nF")
      (fields
        (field (name "BOM_Manufacturer Part") "CL21B104KBCNNNC")
        (field (name "BOM_Supplier Part") "C1711")
      )
      (libsource (lib "") (part "CL21B104KBCNNNC_1"))
    )
    (comp (ref "C40")
      (value "100nF")
      (fields
        (field (name "BOM_Manufacturer Part") "CL21B104KBCNNNC")
        (field (name "BOM_Supplier Part") "C1711")
      )
      (libsource (lib "") (part "CL21B104KBCNNNC_1"))
    )
    (comp (ref "C41")
      (value "100nF")
      (fields
        (field (name "BOM_Manufacturer Part") "CL21B104KBCNNNC")
        (field (name "BOM_Supplier Part") "C1711")
      )
      (libsource (lib "") (part "CL21B104KBCNNNC"))
    )
    (comp (ref "C42")
      (value "10uF")
      (fields
        (field (name "BOM_Manufacturer Part") "TMK212BBJ106KGHT")
        (field (name "BOM_Supplier Part") "C386084")
      )
      (libsource (lib "") (part "TMK212BBJ106KGHT"))
    )
    (comp (ref "CARD2")
      (value "XKTF-N02-G")
      (fields (field (name "BOM_Supplier Part") "C1121875"))
      (libsource (lib "") (part "XKTF-N02-G"))
    )
    (comp (ref "D51")
      (value "ESD9X5V-2/TR")
      (fields (field (name "BOM_Supplier Part") "C239552"))
      (libsource (lib "") (part "ESD9X5V-2/TR_1"))
    )
    (comp (ref "D52")
      (value "ESD9X5V-2/TR")
      (fields (field (name "BOM_Supplier Part") "C239552"))
      (libsource (lib "") (part "ESD9X5V-2/TR_1"))
    )
    (comp (ref "D53")
      (value "ESD9X5V-2/TR")
      (fields (field (name "BOM_Supplier Part") "C239552"))
      (libsource (lib "") (part "ESD9X5V-2/TR_1"))
    )
    (comp (ref "D54")
      (value "ESD9X5V-2/TR")
      (fields (field (name "BOM_Supplier Part") "C239552"))
      (libsource (lib "") (part "ESD9X5V-2/TR"))
    )
    (comp (ref "D55")
      (value "ESD9X5V-2/TR")
      (fields (field (name "BOM_Supplier Part") "C239552"))
      (libsource (lib "") (part "ESD9X5V-2/TR"))
    )
    (comp (ref "D56")
      (value "ESD9X5V-2/TR")
      (fields (field (name "BOM_Supplier Part") "C239552"))
      (libsource (lib "") (part "ESD9X5V-2/TR"))
    )
    (comp (ref "D59")
      (value "ESD9X5V-2/TR")
      (fields (field (name "BOM_Supplier Part") "C239552"))
      (libsource (lib "") (part "ESD9X5V-2/TR_1"))
    )
    (comp (ref "R2")
      (value "2.2kΩ")
      (fields
        (field (name "BOM_Manufacturer Part") "AR05BTB2201")
        (field (name "BOM_Supplier Part") "C374634")
      )
      (libsource (lib "") (part "AR05BTB2201"))
    )
    (comp (ref "R3")
      (value "2.2kΩ")
      (fields
        (field (name "BOM_Manufacturer Part") "AR05BTB2201")
        (field (name "BOM_Supplier Part") "C374634")
      )
      (libsource (lib "") (part "AR05BTB2201"))
    )
    (comp (ref "R4")
      (value "100kΩ")
      (fields
        (field (name "BOM_Manufacturer Part") "ARG05BTC1003")
        (field (name "BOM_Supplier Part") "C406726")
      )
      (libsource (lib "") (part "ARG05BTC1003"))
    )
    (comp (ref "R5")
      (value "100kΩ")
      (fields
        (field (name "BOM_Manufacturer Part") "ARG05BTC1003")
        (field (name "BOM_Supplier Part") "C406726")
      )
      (libsource (lib "") (part "ARG05BTC1003"))
    )
    (comp (ref "R6")
      (value "100kΩ")
      (fields
        (field (name "BOM_Manufacturer Part") "ARG05BTC1003")
        (field (name "BOM_Supplier Part") "C406726")
      )
      (libsource (lib "") (part "ARG05BTC1003"))
    )
    (comp (ref "R7")
      (value "100kΩ")
      (fields
        (field (name "BOM_Manufacturer Part") "ARG05BTC1003")
        (field (name "BOM_Supplier Part") "C406726")
      )
      (libsource (lib "") (part "ARG05BTC1003"))
    )
    (comp (ref "R8")
      (value "100kΩ")
      (fields
        (field (name "BOM_Manufacturer Part") "ARG05BTC1003")
        (field (name "BOM_Supplier Part") "C406726")
      )
      (libsource (lib "") (part "ARG05BTC1003"))
    )
    (comp (ref "R39")
      (value "100kΩ")
      (fields
        (field (name "BOM_Manufacturer Part") "ARG05BTC1003")
        (field (name "BOM_Supplier Part") "C406726")
      )
      (libsource (lib "") (part "ARG05BTC1003"))
    )
    (comp (ref "U2")
      (value "BMP388")
      (fields (field (name "BOM_Supplier Part") "C779278"))
      (libsource (lib "") (part "BMP388"))
    )
    (comp (ref "U3")
      (value "QMC5883L")
      (fields (field (name "BOM_Supplier Part") "C976032"))
      (libsource (lib "") (part "QMC5883L"))
    )
    (comp (ref "U4")
      (value "LSM6DSOWTR")
      (fields (field (name "BOM_Supplier Part") "C2829074"))
      (libsource (lib "") (part "LSM6DSOWTR"))
    )
    (comp (ref "C20")
      (value "100nF")
      (fields
        (field (name "BOM_Manufacturer Part") "CL21B104KBCNNNC")
        (field (name "BOM_Supplier Part") "C1711")
      )
      (libsource (lib "") (part "CL21B104KBCNNNC_1"))
    )
    (comp (ref "C21")
      (value "100nF")
      (fields
        (field (name "BOM_Manufacturer Part") "CL21B104KBCNNNC")
        (field (name "BOM_Supplier Part") "C1711")
      )
      (libsource (lib "") (part "CL21B104KBCNNNC_3"))
    )
    (comp (ref "C27")
      (value "100nF")
      (fields
        (field (name "BOM_Manufacturer Part") "CL21B104KBCNNNC")
        (field (name "BOM_Supplier Part") "C1711")
      )
      (libsource (lib "") (part "CL21B104KBCNNNC_1"))
    )
    (comp (ref "C43")
      (value "4pF")
      (fields
        (field (name "BOM_Manufacturer Part") "TCC0805C0G4R0C500BT")
        (field (name "BOM_Supplier Part") "C282704")
      )
      (libsource (lib "") (part "TCC0805C0G4R0C500BT"))
    )
    (comp (ref "C44")
      (value "4pF")
      (fields
        (field (name "BOM_Manufacturer Part") "TCC0805C0G4R0C500BT")
        (field (name "BOM_Supplier Part") "C282704")
      )
      (libsource (lib "") (part "TCC0805C0G4R0C500BT_1"))
    )
    (comp (ref "C45")
      (value "100nF")
      (fields
        (field (name "BOM_Manufacturer Part") "CL21B104KBCNNNC")
        (field (name "BOM_Supplier Part") "C1711")
      )
      (libsource (lib "") (part "CL21B104KBCNNNC_2"))
    )
    (comp (ref "C46")
      (value "100nF")
      (fields
        (field (name "BOM_Manufacturer Part") "CL21B104KBCNNNC")
        (field (name "BOM_Supplier Part") "C1711")
      )
      (libsource (lib "") (part "CL21B104KBCNNNC_2"))
    )
    (comp (ref "C47")
      (value "100nF")
      (fields
        (field (name "BOM_Manufacturer Part") "CL21B104KBCNNNC")
        (field (name "BOM_Supplier Part") "C1711")
      )
      (libsource (lib "") (part "CL21B104KBCNNNC"))
    )
    (comp (ref "C48")
      (value "100nF")
      (fields
        (field (name "BOM_Manufacturer Part") "CL21B104KBCNNNC")
        (field (name "BOM_Supplier Part") "C1711")
      )
      (libsource (lib "") (part "CL21B104KBCNNNC"))
    )
    (comp (ref "C49")
      (value "47uF")
      (fields
        (field (name "BOM_Manufacturer Part") "JMK212BJ476MG-T")
        (field (name "BOM_Supplier Part") "C87159")
      )
      (libsource (lib "") (part "JMK212BJ476MG-T"))
    )
    (comp (ref "C50")
      (value "47uF")
      (fields
        (field (name "BOM_Manufacturer Part") "JMK212BJ476MG-T")
        (field (name "BOM_Supplier Part") "C87159")
      )
      (libsource (lib "") (part "JMK212BJ476MG-T"))
    )
    (comp (ref "C51")
      (value "100nF")
      (fields
        (field (name "BOM_Manufacturer Part") "CL21B104KBCNNNC")
        (field (name "BOM_Supplier Part") "C1711")
      )
      (libsource (lib "") (part "CL21B104KBCNNNC_2"))
    )
    (comp (ref "C85")
      (value "47pF")
      (fields
        (field (name "BOM_Manufacturer Part") "GCM21A5C2E470JX01D")
        (field (name "BOM_Supplier Part") "C440149")
      )
      (libsource (lib "") (part "GCM21A5C2E470JX01D"))
    )
    (comp (ref "CN18")
      (value "A1257WR-S-3P")
      (fields (field (name "BOM_Supplier Part") "C225126"))
      (libsource (lib "") (part "A1257WR-S-3P"))
    )
    (comp (ref "CN19")
      (value "A1257WR-S-3P")
      (fields (field (name "BOM_Supplier Part") "C225126"))
      (libsource (lib "") (part "A1257WR-S-3P"))
    )
    (comp (ref "CN20")
      (value "A1257WR-S-5P")
      (fields (field (name "BOM_Supplier Part") "C225128"))
      (libsource (lib "") (part "A1257WR-S-5P"))
    )
    (comp (ref "D57")
      (value "ESD9X5V-2/TR")
      (fields (field (name "BOM_Supplier Part") "C239552"))
      (libsource (lib "") (part "ESD9X5V-2/TR"))
    )
    (comp (ref "D58")
      (value "ESD9X5V-2/TR")
      (fields (field (name "BOM_Supplier Part") "C239552"))
      (libsource (lib "") (part "ESD9X5V-2/TR"))
    )
    (comp (ref "R9")
      (value "10kΩ")
      (fields
        (field (name "BOM_Manufacturer Part") "ARG05BTC1002")
        (field (name "BOM_Supplier Part") "C406725")
      )
      (libsource (lib "") (part "ARG05BTC1002"))
    )
    (comp (ref "R10")
      (value "1kΩ")
      (fields
        (field (name "BOM_Manufacturer Part") "ARG05BTC1001")
        (field (name "BOM_Supplier Part") "C309081")
      )
      (libsource (lib "") (part "ARG05BTC1001"))
    )
    (comp (ref "R11")
      (value "1kΩ")
      (fields
        (field (name "BOM_Manufacturer Part") "ARG05BTC1001")
        (field (name "BOM_Supplier Part") "C309081")
      )
      (libsource (lib "") (part "ARG05BTC1001"))
    )
    (comp (ref "R12")
      (value "1kΩ")
      (fields
        (field (name "BOM_Manufacturer Part") "ARG05BTC1001")
        (field (name "BOM_Supplier Part") "C309081")
      )
      (libsource (lib "") (part "ARG05BTC1001"))
    )
    (comp (ref "R13")
      (value "75Ω")
      (fields
        (field (name "BOM_Manufacturer Part") "AR05BTDW0750")
        (field (name "BOM_Supplier Part") "C319469")
      )
      (libsource (lib "") (part "AR05BTDW0750"))
    )
    (comp (ref "R14")
      (value "75Ω")
      (fields
        (field (name "BOM_Manufacturer Part") "AR05BTDW0750")
        (field (name "BOM_Supplier Part") "C319469")
      )
      (libsource (lib "") (part "AR05BTDW0750_1"))
    )
    (comp (ref "R15")
      (value "200kΩ")
      (fields
        (field (name "BOM_Manufacturer Part") "AR05BTDW2003")
        (field (name "BOM_Supplier Part") "C319784")
      )
      (libsource (lib "") (part "AR05BTDW2003"))
    )
    (comp (ref "R90")
      (value "0Ω")
      (fields
        (field (name "BOM_Manufacturer Part") "0805W8F0000T5E")
        (field (name "BOM_Supplier Part") "C17477")
      )
      (libsource (lib "") (part "0805W8F0000T5E"))
    )
    (comp (ref "R91")
      (value "0Ω")
      (fields
        (field (name "BOM_Manufacturer Part") "0805W8F0000T5E")
        (field (name "BOM_Supplier Part") "C17477")
      )
      (libsource (lib "") (part "0805W8F0000T5E"))
    )
    (comp (ref "U5")
      (value "ATMEGA328P-AU")
      (fields (field (name "BOM_Supplier Part") "C14877"))
      (libsource (lib "") (part "ATMEGA328P-AU"))
    )
    (comp (ref "U6")
      (value "AT7456E")
      (fields (field (name "BOM_Supplier Part") "C82351"))
      (libsource (lib "") (part "AT7456E"))
    )
    (comp (ref "U7")
      (value "PCA9306DCUR")
      (fields (field (name "BOM_Supplier Part") "C33196"))
      (libsource (lib "") (part "PCA9306DCUR"))
    )
    (comp (ref "X3")
      (value "16MHz")
      (fields
        (field (name "BOM_Manufacturer Part") "X1E0003410273")
        (field (name "BOM_Supplier Part") "C255906")
      )
      (libsource (lib "") (part "X1E0003410273"))
    )
    (comp (ref "X4")
      (value "27MHz")
      (fields
        (field (name "BOM_Manufacturer Part") "Q24FA20H00238")
        (field (name "BOM_Supplier Part") "C255960")
      )
      (libsource (lib "") (part "Q24FA20H00238"))
    )
    (comp (ref "C89")
      (value "100nF")
      (fields
        (field (name "BOM_Manufacturer Part") "CL21B104KBCNNNC")
        (field (name "BOM_Supplier Part") "C1711")
      )
      (libsource (lib "") (part "CL21B104KBCNNNC"))
    )
    (comp (ref "C90")
      (value "100nF")
      (fields
        (field (name "BOM_Manufacturer Part") "CL21B104KBCNNNC")
        (field (name "BOM_Supplier Part") "C1711")
      )
      (libsource (lib "") (part "CL21B104KBCNNNC"))
    )
    (comp (ref "C91")
      (value "100nF")
      (fields
        (field (name "BOM_Manufacturer Part") "CL21B104KBCNNNC")
        (field (name "BOM_Supplier Part") "C1711")
      )
      (libsource (lib "") (part "CL21B104KBCNNNC"))
    )
    (comp (ref "C92")
      (value "100nF")
      (fields
        (field (name "BOM_Manufacturer Part") "CL21B104KBCNNNC")
        (field (name "BOM_Supplier Part") "C1711")
      )
      (libsource (lib "") (part "CL21B104KBCNNNC_1"))
    )
    (comp (ref "C93")
      (value "100nF")
      (fields
        (field (name "BOM_Manufacturer Part") "CL21B104KBCNNNC")
        (field (name "BOM_Supplier Part") "C1711")
      )
      (libsource (lib "") (part "CL21B104KBCNNNC"))
    )
    (comp (ref "C95")
      (value "100nF")
      (fields
        (field (name "BOM_Manufacturer Part") "CL21B104KBCNNNC")
        (field (name "BOM_Supplier Part") "C1711")
      )
      (libsource (lib "") (part "CL21B104KBCNNNC_1"))
    )
    (comp (ref "CN1")
      (value "A1257WV-S-7P")
      (fields (field (name "BOM_Supplier Part") "C225123"))
      (libsource (lib "") (part "A1257WV-S-7P"))
    )
    (comp (ref "CN2")
      (value "A1257WV-S-7P")
      (fields (field (name "BOM_Supplier Part") "C225123"))
      (libsource (lib "") (part "A1257WV-S-7P"))
    )
    (comp (ref "CN3")
      (value "A1257WV-S-6P")
      (fields (field (name "BOM_Supplier Part") "C225122"))
      (libsource (lib "") (part "A1257WV-S-6P"))
    )
    (comp (ref "CN4")
      (value "A1257WV-S-6P")
      (fields (field (name "BOM_Supplier Part") "C225122"))
      (libsource (lib "") (part "A1257WV-S-6P"))
    )
    (comp (ref "CN5")
      (value "A1257WV-S-6P")
      (fields (field (name "BOM_Supplier Part") "C225122"))
      (libsource (lib "") (part "A1257WV-S-6P"))
    )
    (comp (ref "CN6")
      (value "A1257WV-S-4P")
      (fields (field (name "BOM_Supplier Part") "C225120"))
      (libsource (lib "") (part "A1257WV-S-4P"))
    )
    (comp (ref "CN7")
      (value "A1257WV-S-4P")
      (fields (field (name "BOM_Supplier Part") "C225120"))
      (libsource (lib "") (part "A1257WV-S-4P"))
    )
    (comp (ref "CN8")
      (value "A1257WV-S-4P")
      (fields (field (name "BOM_Supplier Part") "C225120"))
      (libsource (lib "") (part "A1257WV-S-4P"))
    )
    (comp (ref "CN9")
      (value "A1257WV-S-4P")
      (fields (field (name "BOM_Supplier Part") "C225120"))
      (libsource (lib "") (part "A1257WV-S-4P"))
    )
    (comp (ref "CN10")
      (value "A1257WV-S-4P")
      (fields (field (name "BOM_Supplier Part") "C225120"))
      (libsource (lib "") (part "A1257WV-S-4P"))
    )
    (comp (ref "CN11")
      (value "A1257WV-S-4P")
      (fields (field (name "BOM_Supplier Part") "C225120"))
      (libsource (lib "") (part "A1257WV-S-4P"))
    )
    (comp (ref "CN14")
      (value "GH125-S10CCA-00")
      (fields (field (name "BOM_Supplier Part") "C2886788"))
      (libsource (lib "") (part "GH125-S10CCA-00"))
    )
    (comp (ref "CN16")
      (value "GH125-S10CCA-00")
      (fields (field (name "BOM_Supplier Part") "C2886788"))
      (libsource (lib "") (part "GH125-S10CCA-00"))
    )
    (comp (ref "CN21")
      (value "A1257WR-S-3P")
      (fields (field (name "BOM_Supplier Part") "C225126"))
      (libsource (lib "") (part "A1257WR-S-3P"))
    )
    (comp (ref "CN22")
      (value "A1257WR-S-5P")
      (fields (field (name "BOM_Supplier Part") "C225128"))
      (libsource (lib "") (part "A1257WR-S-5P"))
    )
    (comp (ref "CN24")
      (value "A1257WR-S-8P")
      (fields (field (name "BOM_Supplier Part") "C225131"))
      (libsource (lib "") (part "A1257WR-S-8P"))
    )
    (comp (ref "D4")
      (value "SP1001-05JTG")
      (fields (field (name "BOM_Supplier Part") "C207268"))
      (libsource (lib "") (part "SP1001-05JTG"))
    )
    (comp (ref "D5")
      (value "SP1001-05JTG")
      (fields (field (name "BOM_Supplier Part") "C207268"))
      (libsource (lib "") (part "SP1001-05JTG"))
    )
    (comp (ref "D6")
      (value "ESD9X5V-2/TR")
      (fields (field (name "BOM_Supplier Part") "C239552"))
      (libsource (lib "") (part "ESD9X5V-2/TR"))
    )
    (comp (ref "D7")
      (value "ESD9X5V-2/TR")
      (fields (field (name "BOM_Supplier Part") "C239552"))
      (libsource (lib "") (part "ESD9X5V-2/TR"))
    )
    (comp (ref "D8")
      (value "ESD9X5V-2/TR")
      (fields (field (name "BOM_Supplier Part") "C239552"))
      (libsource (lib "") (part "ESD9X5V-2/TR"))
    )
    (comp (ref "D9")
      (value "ESD9X5V-2/TR")
      (fields (field (name "BOM_Supplier Part") "C239552"))
      (libsource (lib "") (part "ESD9X5V-2/TR"))
    )
    (comp (ref "D10")
      (value "ESD9X5V-2/TR")
      (fields (field (name "BOM_Supplier Part") "C239552"))
      (libsource (lib "") (part "ESD9X5V-2/TR"))
    )
    (comp (ref "D11")
      (value "ESD9X5V-2/TR")
      (fields (field (name "BOM_Supplier Part") "C239552"))
      (libsource (lib "") (part "ESD9X5V-2/TR"))
    )
    (comp (ref "D12")
      (value "ESD9X5V-2/TR")
      (fields (field (name "BOM_Supplier Part") "C239552"))
      (libsource (lib "") (part "ESD9X5V-2/TR"))
    )
    (comp (ref "D13")
      (value "ESD9X5V-2/TR")
      (fields (field (name "BOM_Supplier Part") "C239552"))
      (libsource (lib "") (part "ESD9X5V-2/TR"))
    )
    (comp (ref "D16")
      (value "SP1001-04JTG")
      (fields (field (name "BOM_Supplier Part") "C207267"))
      (libsource (lib "") (part "SP1001-04JTG"))
    )
    (comp (ref "D17")
      (value "SP1001-04JTG")
      (fields (field (name "BOM_Supplier Part") "C207267"))
      (libsource (lib "") (part "SP1001-04JTG"))
    )
    (comp (ref "D18")
      (value "ESD9X5V-2/TR")
      (fields (field (name "BOM_Supplier Part") "C239552"))
      (libsource (lib "") (part "ESD9X5V-2/TR"))
    )
    (comp (ref "D19")
      (value "ESD9X5V-2/TR")
      (fields (field (name "BOM_Supplier Part") "C239552"))
      (libsource (lib "") (part "ESD9X5V-2/TR"))
    )
    (comp (ref "D20")
      (value "ESD9X5V-2/TR")
      (fields (field (name "BOM_Supplier Part") "C239552"))
      (libsource (lib "") (part "ESD9X5V-2/TR"))
    )
    (comp (ref "D21")
      (value "ESD9X5V-2/TR")
      (fields (field (name "BOM_Supplier Part") "C239552"))
      (libsource (lib "") (part "ESD9X5V-2/TR"))
    )
    (comp (ref "D22")
      (value "ESD9X5V-2/TR")
      (fields (field (name "BOM_Supplier Part") "C239552"))
      (libsource (lib "") (part "ESD9X5V-2/TR"))
    )
    (comp (ref "D23")
      (value "ESD9X5V-2/TR")
      (fields (field (name "BOM_Supplier Part") "C239552"))
      (libsource (lib "") (part "ESD9X5V-2/TR"))
    )
    (comp (ref "D24")
      (value "ESD9X5V-2/TR")
      (fields (field (name "BOM_Supplier Part") "C239552"))
      (libsource (lib "") (part "ESD9X5V-2/TR"))
    )
    (comp (ref "D25")
      (value "ESD9X5V-2/TR")
      (fields (field (name "BOM_Supplier Part") "C239552"))
      (libsource (lib "") (part "ESD9X5V-2/TR"))
    )
    (comp (ref "D26")
      (value "ESD9X5V-2/TR")
      (fields (field (name "BOM_Supplier Part") "C239552"))
      (libsource (lib "") (part "ESD9X5V-2/TR"))
    )
    (comp (ref "D27")
      (value "ESD9X5V-2/TR")
      (fields (field (name "BOM_Supplier Part") "C239552"))
      (libsource (lib "") (part "ESD9X5V-2/TR"))
    )
    (comp (ref "D28")
      (value "ESD9X5V-2/TR")
      (fields (field (name "BOM_Supplier Part") "C239552"))
      (libsource (lib "") (part "ESD9X5V-2/TR"))
    )
    (comp (ref "D29")
      (value "ESD9X5V-2/TR")
      (fields (field (name "BOM_Supplier Part") "C239552"))
      (libsource (lib "") (part "ESD9X5V-2/TR"))
    )
    (comp (ref "D30")
      (value "ESD9X5V-2/TR")
      (fields (field (name "BOM_Supplier Part") "C239552"))
      (libsource (lib "") (part "ESD9X5V-2/TR"))
    )
    (comp (ref "D31")
      (value "ESD9X5V-2/TR")
      (fields (field (name "BOM_Supplier Part") "C239552"))
      (libsource (lib "") (part "ESD9X5V-2/TR"))
    )
    (comp (ref "D32")
      (value "ESD9X5V-2/TR")
      (fields (field (name "BOM_Supplier Part") "C239552"))
      (libsource (lib "") (part "ESD9X5V-2/TR"))
    )
    (comp (ref "D33")
      (value "ESD9X5V-2/TR")
      (fields (field (name "BOM_Supplier Part") "C239552"))
      (libsource (lib "") (part "ESD9X5V-2/TR"))
    )
    (comp (ref "D34")
      (value "ESD9X5V-2/TR")
      (fields (field (name "BOM_Supplier Part") "C239552"))
      (libsource (lib "") (part "ESD9X5V-2/TR"))
    )
    (comp (ref "D35")
      (value "ESD9X5V-2/TR")
      (fields (field (name "BOM_Supplier Part") "C239552"))
      (libsource (lib "") (part "ESD9X5V-2/TR"))
    )
    (comp (ref "D36")
      (value "ESD9X5V-2/TR")
      (fields (field (name "BOM_Supplier Part") "C239552"))
      (libsource (lib "") (part "ESD9X5V-2/TR"))
    )
    (comp (ref "D37")
      (value "ESD9X5V-2/TR")
      (fields (field (name "BOM_Supplier Part") "C239552"))
      (libsource (lib "") (part "ESD9X5V-2/TR"))
    )
    (comp (ref "D38")
      (value "ESD9X5V-2/TR")
      (fields (field (name "BOM_Supplier Part") "C239552"))
      (libsource (lib "") (part "ESD9X5V-2/TR"))
    )
    (comp (ref "D39")
      (value "ESD9X5V-2/TR")
      (fields (field (name "BOM_Supplier Part") "C239552"))
      (libsource (lib "") (part "ESD9X5V-2/TR_1"))
    )
    (comp (ref "D40")
      (value "ESD9X5V-2/TR")
      (fields (field (name "BOM_Supplier Part") "C239552"))
      (libsource (lib "") (part "ESD9X5V-2/TR_1"))
    )
    (comp (ref "D41")
      (value "ESD9X5V-2/TR")
      (fields (field (name "BOM_Supplier Part") "C239552"))
      (libsource (lib "") (part "ESD9X5V-2/TR_1"))
    )
    (comp (ref "D42")
      (value "ESD9X5V-2/TR")
      (fields (field (name "BOM_Supplier Part") "C239552"))
      (libsource (lib "") (part "ESD9X5V-2/TR_1"))
    )
    (comp (ref "D43")
      (value "ESD9X5V-2/TR")
      (fields (field (name "BOM_Supplier Part") "C239552"))
      (libsource (lib "") (part "ESD9X5V-2/TR_1"))
    )
    (comp (ref "D44")
      (value "ESD9X5V-2/TR")
      (fields (field (name "BOM_Supplier Part") "C239552"))
      (libsource (lib "") (part "ESD9X5V-2/TR_1"))
    )
    (comp (ref "D45")
      (value "ESD9X5V-2/TR")
      (fields (field (name "BOM_Supplier Part") "C239552"))
      (libsource (lib "") (part "ESD9X5V-2/TR_1"))
    )
    (comp (ref "D46")
      (value "ESD9X5V-2/TR")
      (fields (field (name "BOM_Supplier Part") "C239552"))
      (libsource (lib "") (part "ESD9X5V-2/TR_1"))
    )
    (comp (ref "D47")
      (value "ESD9X5V-2/TR")
      (fields (field (name "BOM_Supplier Part") "C239552"))
      (libsource (lib "") (part "ESD9X5V-2/TR"))
    )
    (comp (ref "D48")
      (value "ESD9X5V-2/TR")
      (fields (field (name "BOM_Supplier Part") "C239552"))
      (libsource (lib "") (part "ESD9X5V-2/TR"))
    )
    (comp (ref "D49")
      (value "ESD9X5V-2/TR")
      (fields (field (name "BOM_Supplier Part") "C239552"))
      (libsource (lib "") (part "ESD9X5V-2/TR"))
    )
    (comp (ref "D50")
      (value "ESD9X5V-2/TR")
      (fields (field (name "BOM_Supplier Part") "C239552"))
      (libsource (lib "") (part "ESD9X5V-2/TR"))
    )
    (comp (ref "R49")
      (value "1.5K")
      (fields
        (field (name "BOM_Manufacturer Part") "CR0805-FX-1501ELF")
        (field (name "BOM_Supplier Part") "C203762")
      )
      (libsource (lib "") (part "CR0805-FX-1501ELF"))
    )
    (comp (ref "R50")
      (value "1.5K")
      (fields
        (field (name "BOM_Manufacturer Part") "CR0805-FX-1501ELF")
        (field (name "BOM_Supplier Part") "C203762")
      )
      (libsource (lib "") (part "CR0805-FX-1501ELF"))
    )
    (comp (ref "R51")
      (value "1.5K")
      (fields
        (field (name "BOM_Manufacturer Part") "CR0805-FX-1501ELF")
        (field (name "BOM_Supplier Part") "C203762")
      )
      (libsource (lib "") (part "CR0805-FX-1501ELF"))
    )
    (comp (ref "R52")
      (value "1.5K")
      (fields
        (field (name "BOM_Manufacturer Part") "CR0805-FX-1501ELF")
        (field (name "BOM_Supplier Part") "C203762")
      )
      (libsource (lib "") (part "CR0805-FX-1501ELF"))
    )
    (comp (ref "R53")
      (value "22")
      (fields
        (field (name "BOM_Manufacturer Part") "CR0805-FX-22R0ELF")
        (field (name "BOM_Supplier Part") "C204317")
      )
      (libsource (lib "") (part "CR0805-FX-22R0ELF"))
    )
    (comp (ref "R54")
      (value "22")
      (fields
        (field (name "BOM_Manufacturer Part") "CR0805-FX-22R0ELF")
        (field (name "BOM_Supplier Part") "C204317")
      )
      (libsource (lib "") (part "CR0805-FX-22R0ELF_1"))
    )
    (comp (ref "R55")
      (value "22")
      (fields
        (field (name "BOM_Manufacturer Part") "CR0805-FX-22R0ELF")
        (field (name "BOM_Supplier Part") "C204317")
      )
      (libsource (lib "") (part "CR0805-FX-22R0ELF"))
    )
    (comp (ref "R56")
      (value "22")
      (fields
        (field (name "BOM_Manufacturer Part") "CR0805-FX-22R0ELF")
        (field (name "BOM_Supplier Part") "C204317")
      )
      (libsource (lib "") (part "CR0805-FX-22R0ELF"))
    )
    (comp (ref "R57")
      (value "100Ω")
      (fields
        (field (name "BOM_Manufacturer Part") "FRC0603J101 TS")
        (field (name "BOM_Supplier Part") "C2907089")
      )
      (libsource (lib "") (part "FRC0603J101 TS"))
    )
    (comp (ref "R59")
      (value "100Ω")
      (fields
        (field (name "BOM_Manufacturer Part") "FRC0603J101 TS")
        (field (name "BOM_Supplier Part") "C2907089")
      )
      (libsource (lib "") (part "FRC0603J101 TS"))
    )
    (comp (ref "R60")
      (value "100Ω")
      (fields
        (field (name "BOM_Manufacturer Part") "FRC0603J101 TS")
        (field (name "BOM_Supplier Part") "C2907089")
      )
      (libsource (lib "") (part "FRC0603J101 TS"))
    )
    (comp (ref "R61")
      (value "100Ω")
      (fields
        (field (name "BOM_Manufacturer Part") "FRC0603J101 TS")
        (field (name "BOM_Supplier Part") "C2907089")
      )
      (libsource (lib "") (part "FRC0603J101 TS"))
    )
    (comp (ref "R66")
      (value "100Ω")
      (fields
        (field (name "BOM_Manufacturer Part") "FRC0603J101 TS")
        (field (name "BOM_Supplier Part") "C2907089")
      )
      (libsource (lib "") (part "FRC0603J101 TS"))
    )
    (comp (ref "R67")
      (value "100Ω")
      (fields
        (field (name "BOM_Manufacturer Part") "FRC0603J101 TS")
        (field (name "BOM_Supplier Part") "C2907089")
      )
      (libsource (lib "") (part "FRC0603J101 TS"))
    )
    (comp (ref "R68")
      (value "100Ω")
      (fields
        (field (name "BOM_Manufacturer Part") "FRC0603J101 TS")
        (field (name "BOM_Supplier Part") "C2907089")
      )
      (libsource (lib "") (part "FRC0603J101 TS"))
    )
    (comp (ref "R69")
      (value "100Ω")
      (fields
        (field (name "BOM_Manufacturer Part") "FRC0603J101 TS")
        (field (name "BOM_Supplier Part") "C2907089")
      )
      (libsource (lib "") (part "FRC0603J101 TS"))
    )
    (comp (ref "R70")
      (value "100Ω")
      (fields
        (field (name "BOM_Manufacturer Part") "FRC0603J101 TS")
        (field (name "BOM_Supplier Part") "C2907089")
      )
      (libsource (lib "") (part "FRC0603J101 TS"))
    )
    (comp (ref "R71")
      (value "100Ω")
      (fields
        (field (name "BOM_Manufacturer Part") "FRC0603J101 TS")
        (field (name "BOM_Supplier Part") "C2907089")
      )
      (libsource (lib "") (part "FRC0603J101 TS"))
    )
    (comp (ref "R72")
      (value "100Ω")
      (fields
        (field (name "BOM_Manufacturer Part") "FRC0603J101 TS")
        (field (name "BOM_Supplier Part") "C2907089")
      )
      (libsource (lib "") (part "FRC0603J101 TS"))
    )
    (comp (ref "R73")
      (value "100Ω")
      (fields
        (field (name "BOM_Manufacturer Part") "FRC0603J101 TS")
        (field (name "BOM_Supplier Part") "C2907089")
      )
      (libsource (lib "") (part "FRC0603J101 TS"))
    )
    (comp (ref "R74")
      (value "100Ω")
      (fields
        (field (name "BOM_Manufacturer Part") "FRC0603J101 TS")
        (field (name "BOM_Supplier Part") "C2907089")
      )
      (libsource (lib "") (part "FRC0603J101 TS"))
    )
    (comp (ref "R75")
      (value "100Ω")
      (fields
        (field (name "BOM_Manufacturer Part") "FRC0603J101 TS")
        (field (name "BOM_Supplier Part") "C2907089")
      )
      (libsource (lib "") (part "FRC0603J101 TS"))
    )
    (comp (ref "R76")
      (value "100Ω")
      (fields
        (field (name "BOM_Manufacturer Part") "FRC0603J101 TS")
        (field (name "BOM_Supplier Part") "C2907089")
      )
      (libsource (lib "") (part "FRC0603J101 TS"))
    )
    (comp (ref "R77")
      (value "100Ω")
      (fields
        (field (name "BOM_Manufacturer Part") "FRC0603J101 TS")
        (field (name "BOM_Supplier Part") "C2907089")
      )
      (libsource (lib "") (part "FRC0603J101 TS"))
    )
    (comp (ref "R78")
      (value "100Ω")
      (fields
        (field (name "BOM_Manufacturer Part") "FRC0603J101 TS")
        (field (name "BOM_Supplier Part") "C2907089")
      )
      (libsource (lib "") (part "FRC0603J101 TS"))
    )
    (comp (ref "R79")
      (value "100Ω")
      (fields
        (field (name "BOM_Manufacturer Part") "FRC0603J101 TS")
        (field (name "BOM_Supplier Part") "C2907089")
      )
      (libsource (lib "") (part "FRC0603J101 TS"))
    )
    (comp (ref "R80")
      (value "100Ω")
      (fields
        (field (name "BOM_Manufacturer Part") "FRC0603J101 TS")
        (field (name "BOM_Supplier Part") "C2907089")
      )
      (libsource (lib "") (part "FRC0603J101 TS"))
    )
    (comp (ref "R81")
      (value "100Ω")
      (fields
        (field (name "BOM_Manufacturer Part") "FRC0603J101 TS")
        (field (name "BOM_Supplier Part") "C2907089")
      )
      (libsource (lib "") (part "FRC0603J101 TS"))
    )
    (comp (ref "R82")
      (value "100Ω")
      (fields
        (field (name "BOM_Manufacturer Part") "FRC0603J101 TS")
        (field (name "BOM_Supplier Part") "C2907089")
      )
      (libsource (lib "") (part "FRC0603J101 TS"))
    )
    (comp (ref "R83")
      (value "100Ω")
      (fields
        (field (name "BOM_Manufacturer Part") "FRC0603J101 TS")
        (field (name "BOM_Supplier Part") "C2907089")
      )
      (libsource (lib "") (part "FRC0603J101 TS"))
    )
    (comp (ref "R84")
      (value "100Ω")
      (fields
        (field (name "BOM_Manufacturer Part") "FRC0603J101 TS")
        (field (name "BOM_Supplier Part") "C2907089")
      )
      (libsource (lib "") (part "FRC0603J101 TS"))
    )
    (comp (ref "R85")
      (value "100Ω")
      (fields
        (field (name "BOM_Manufacturer Part") "FRC0603J101 TS")
        (field (name "BOM_Supplier Part") "C2907089")
      )
      (libsource (lib "") (part "FRC0603J101 TS"))
    )
    (comp (ref "R88")
      (value "0Ω")
      (fields
        (field (name "BOM_Manufacturer Part") "0805W8F0000T5E")
        (field (name "BOM_Supplier Part") "C17477")
      )
      (libsource (lib "") (part "0805W8F0000T5E"))
    )
    (comp (ref "R89")
      (value "0Ω")
      (fields
        (field (name "BOM_Manufacturer Part") "0805W8F0000T5E")
        (field (name "BOM_Supplier Part") "C17477")
      )
      (libsource (lib "") (part "0805W8F0000T5E_1"))
    )
    (comp (ref "U25")
      (value "TXS0108ERGYR")
      (fields (field (name "BOM_Supplier Part") "C90706"))
      (libsource (lib "") (part "TXS0108ERGYR"))
    )
    (comp (ref "U26")
      (value "TXS0108ERGYR")
      (fields (field (name "BOM_Supplier Part") "C90706"))
      (libsource (lib "") (part "TXS0108ERGYR"))
    )
    (comp (ref "U29")
      (value "TXS0108ERGYR")
      (fields (field (name "BOM_Supplier Part") "C90706"))
      (libsource (lib "") (part "TXS0108ERGYR"))
    )
    (comp (ref "C52")
      (value "100nF")
      (fields
        (field (name "BOM_Manufacturer Part") "CL21B104KBCNNNC")
        (field (name "BOM_Supplier Part") "C1711")
      )
      (libsource (lib "") (part "CL21B104KBCNNNC"))
    )
    (comp (ref "C53")
      (value "100nF")
      (fields
        (field (name "BOM_Manufacturer Part") "CL21B104KBCNNNC")
        (field (name "BOM_Supplier Part") "C1711")
      )
      (libsource (lib "") (part "CL21B104KBCNNNC_1"))
    )
    (comp (ref "C54")
      (value "100nF")
      (fields
        (field (name "BOM_Manufacturer Part") "CL21B104KBCNNNC")
        (field (name "BOM_Supplier Part") "C1711")
      )
      (libsource (lib "") (part "CL21B104KBCNNNC_1"))
    )
    (comp (ref "C55")
      (value "10uF")
      (fields
        (field (name "BOM_Manufacturer Part") "TMK212BBJ106KGHT")
        (field (name "BOM_Supplier Part") "C386084")
      )
      (libsource (lib "") (part "TMK212BBJ106KGHT"))
    )
    (comp (ref "C56")
      (value "100nF")
      (fields
        (field (name "BOM_Manufacturer Part") "CL21B104KBCNNNC")
        (field (name "BOM_Supplier Part") "C1711")
      )
      (libsource (lib "") (part "CL21B104KBCNNNC"))
    )
    (comp (ref "C57")
      (value "15pF")
      (fields
        (field (name "BOM_Manufacturer Part") "0805CG150J500NT")
        (field (name "BOM_Supplier Part") "C63339")
      )
      (libsource (lib "") (part "0805CG150J500NT"))
    )
    (comp (ref "C58")
      (value "100nF")
      (fields
        (field (name "BOM_Manufacturer Part") "CL21B104KBCNNNC")
        (field (name "BOM_Supplier Part") "C1711")
      )
      (libsource (lib "") (part "CL21B104KBCNNNC_2"))
    )
    (comp (ref "C59")
      (value "100nF")
      (fields
        (field (name "BOM_Manufacturer Part") "CL21B104KBCNNNC")
        (field (name "BOM_Supplier Part") "C1711")
      )
      (libsource (lib "") (part "CL21B104KBCNNNC_2"))
    )
    (comp (ref "C60")
      (value "1uF")
      (fields
        (field (name "BOM_Manufacturer Part") "UMK212BJ105KG-T")
        (field (name "BOM_Supplier Part") "C319195")
      )
      (libsource (lib "") (part "UMK212BJ105KG-T_2"))
    )
    (comp (ref "C61")
      (value "1uF")
      (fields
        (field (name "BOM_Manufacturer Part") "UMK212BJ105KG-T")
        (field (name "BOM_Supplier Part") "C319195")
      )
      (libsource (lib "") (part "UMK212BJ105KG-T"))
    )
    (comp (ref "C62")
      (value "1uF")
      (fields
        (field (name "BOM_Manufacturer Part") "UMK212BJ105KG-T")
        (field (name "BOM_Supplier Part") "C319195")
      )
      (libsource (lib "") (part "UMK212BJ105KG-T"))
    )
    (comp (ref "C63")
      (value "47pF")
      (fields
        (field (name "BOM_Manufacturer Part") "GCM21A5C2E470JX01D")
        (field (name "BOM_Supplier Part") "C440149")
      )
      (libsource (lib "") (part "GCM21A5C2E470JX01D_1"))
    )
    (comp (ref "C64")
      (value "47pF")
      (fields
        (field (name "BOM_Manufacturer Part") "GCM21A5C2E470JX01D")
        (field (name "BOM_Supplier Part") "C440149")
      )
      (libsource (lib "") (part "GCM21A5C2E470JX01D"))
    )
    (comp (ref "C65")
      (value "100nF")
      (fields
        (field (name "BOM_Manufacturer Part") "CL21B104KBCNNNC")
        (field (name "BOM_Supplier Part") "C1711")
      )
      (libsource (lib "") (part "CL21B104KBCNNNC_1"))
    )
    (comp (ref "C66")
      (value "82nF")
      (fields
        (field (name "BOM_Manufacturer Part") "CC0805JRX7R9BB823")
        (field (name "BOM_Supplier Part") "C520047")
      )
      (libsource (lib "") (part "CC0805JRX7R9BB823"))
    )
    (comp (ref "C67")
      (value "1uF")
      (fields
        (field (name "BOM_Manufacturer Part") "UMK212BJ105KG-T")
        (field (name "BOM_Supplier Part") "C319195")
      )
      (libsource (lib "") (part "UMK212BJ105KG-T"))
    )
    (comp (ref "C68")
      (value "100nF")
      (fields
        (field (name "BOM_Manufacturer Part") "CL21B104KBCNNNC")
        (field (name "BOM_Supplier Part") "C1711")
      )
      (libsource (lib "") (part "CL21B104KBCNNNC_3"))
    )
    (comp (ref "C69")
      (value "10nF")
      (fields
        (field (name "BOM_Manufacturer Part") "CC0805KRX7R9BB103")
        (field (name "BOM_Supplier Part") "C83170")
      )
      (libsource (lib "") (part "CC0805KRX7R9BB103_1"))
    )
    (comp (ref "C70")
      (value "1uF")
      (fields
        (field (name "BOM_Manufacturer Part") "UMK212BJ105KG-T")
        (field (name "BOM_Supplier Part") "C319195")
      )
      (libsource (lib "") (part "UMK212BJ105KG-T_2"))
    )
    (comp (ref "C71")
      (value "100nF")
      (fields
        (field (name "BOM_Manufacturer Part") "CL21B104KBCNNNC")
        (field (name "BOM_Supplier Part") "C1711")
      )
      (libsource (lib "") (part "CL21B104KBCNNNC_1"))
    )
    (comp (ref "C72")
      (value "100nF")
      (fields
        (field (name "BOM_Manufacturer Part") "CL21B104KBCNNNC")
        (field (name "BOM_Supplier Part") "C1711")
      )
      (libsource (lib "") (part "CL21B104KBCNNNC_1"))
    )
    (comp (ref "C73")
      (value "100nF")
      (fields
        (field (name "BOM_Manufacturer Part") "CL21B104KBCNNNC")
        (field (name "BOM_Supplier Part") "C1711")
      )
      (libsource (lib "") (part "CL21B104KBCNNNC_1"))
    )
    (comp (ref "C74")
      (value "100nF")
      (fields
        (field (name "BOM_Manufacturer Part") "CL21B104KBCNNNC")
        (field (name "BOM_Supplier Part") "C1711")
      )
      (libsource (lib "") (part "CL21B104KBCNNNC_1"))
    )
    (comp (ref "C75")
      (value "100nF")
      (fields
        (field (name "BOM_Manufacturer Part") "CL21B104KBCNNNC")
        (field (name "BOM_Supplier Part") "C1711")
      )
      (libsource (lib "") (part "CL21B104KBCNNNC_1"))
    )
    (comp (ref "C76")
      (value "10nF")
      (fields
        (field (name "BOM_Manufacturer Part") "CC0805KRX7R9BB103")
        (field (name "BOM_Supplier Part") "C83170")
      )
      (libsource (lib "") (part "CC0805KRX7R9BB103"))
    )
    (comp (ref "C77")
      (value "10nF")
      (fields
        (field (name "BOM_Manufacturer Part") "CC0805KRX7R9BB103")
        (field (name "BOM_Supplier Part") "C83170")
      )
      (libsource (lib "") (part "CC0805KRX7R9BB103"))
    )
    (comp (ref "C78")
      (value "10nF")
      (fields
        (field (name "BOM_Manufacturer Part") "CC0805KRX7R9BB103")
        (field (name "BOM_Supplier Part") "C83170")
      )
      (libsource (lib "") (part "CC0805KRX7R9BB103_2"))
    )
    (comp (ref "C79")
      (value "10nF")
      (fields
        (field (name "BOM_Manufacturer Part") "CC0805KRX7R9BB103")
        (field (name "BOM_Supplier Part") "C83170")
      )
      (libsource (lib "") (part "CC0805KRX7R9BB103"))
    )
    (comp (ref "C80")
      (value "10nF")
      (fields
        (field (name "BOM_Manufacturer Part") "CC0805KRX7R9BB103")
        (field (name "BOM_Supplier Part") "C83170")
      )
      (libsource (lib "") (part "CC0805KRX7R9BB103"))
    )
    (comp (ref "C86")
      (value "1uF")
      (fields
        (field (name "BOM_Manufacturer Part") "UMK212BJ105KG-T")
        (field (name "BOM_Supplier Part") "C319195")
      )
      (libsource (lib "") (part "UMK212BJ105KG-T"))
    )
    (comp (ref "C88")
      (value "1uF")
      (fields
        (field (name "BOM_Manufacturer Part") "UMK212BJ105KG-T")
        (field (name "BOM_Supplier Part") "C319195")
      )
      (libsource (lib "") (part "UMK212BJ105KG-T_1"))
    )
    (comp (ref "D15")
      (value "ESD9X5V-2/TR")
      (fields (field (name "BOM_Supplier Part") "C239552"))
      (libsource (lib "") (part "ESD9X5V-2/TR"))
    )
    (comp (ref "D64")
      (value "ESD9X5V-2/TR")
      (fields (field (name "BOM_Supplier Part") "C239552"))
      (libsource (lib "") (part "ESD9X5V-2/TR"))
    )
    (comp (ref "D65")
      (value "ESD9X5V-2/TR")
      (fields (field (name "BOM_Supplier Part") "C239552"))
      (libsource (lib "") (part "ESD9X5V-2/TR"))
    )
    (comp (ref "FPC1")
      (value "0.5K-HX-24PWB")
      (fields (field (name "BOM_Supplier Part") "C2919499"))
      (libsource (lib "") (part "0.5K-HX-24PWB"))
    )
    (comp (ref "Q3")
      (value "S8050_C105433")
      (fields (field (name "BOM_Manufacturer Part") "S8050") (field (name "BOM_Supplier Part") "C105433"))
      (libsource (lib "") (part "S8050_C105433"))
    )
    (comp (ref "Q4")
      (value "S8050_C105433")
      (fields (field (name "BOM_Manufacturer Part") "S8050") (field (name "BOM_Supplier Part") "C105433"))
      (libsource (lib "") (part "S8050_C105433"))
    )
    (comp (ref "R16")
      (value "4.7kΩ")
      (fields
        (field (name "BOM_Manufacturer Part") "RMC08054.7K1%N")
        (field (name "BOM_Supplier Part") "C269746")
      )
      (libsource (lib "") (part "RMC08054.7K1%N"))
    )
    (comp (ref "R17")
      (value "4.7kΩ")
      (fields
        (field (name "BOM_Manufacturer Part") "RMC08054.7K1%N")
        (field (name "BOM_Supplier Part") "C269746")
      )
      (libsource (lib "") (part "RMC08054.7K1%N"))
    )
    (comp (ref "R18")
      (value "4.7kΩ")
      (fields
        (field (name "BOM_Manufacturer Part") "RMC08054.7K1%N")
        (field (name "BOM_Supplier Part") "C269746")
      )
      (libsource (lib "") (part "RMC08054.7K1%N"))
    )
    (comp (ref "R19")
      (value "5.1kΩ")
      (fields
        (field (name "BOM_Manufacturer Part") "RMC04025.1K5%N")
        (field (name "BOM_Supplier Part") "C325524")
      )
      (libsource (lib "") (part "RMC04025.1K5%N"))
    )
    (comp (ref "R20")
      (value "5.1kΩ")
      (fields
        (field (name "BOM_Manufacturer Part") "RMC04025.1K5%N")
        (field (name "BOM_Supplier Part") "C325524")
      )
      (libsource (lib "") (part "RMC04025.1K5%N"))
    )
    (comp (ref "R21")
      (value "10kΩ")
      (fields
        (field (name "BOM_Manufacturer Part") "ARG05BTC1002")
        (field (name "BOM_Supplier Part") "C406725")
      )
      (libsource (lib "") (part "ARG05BTC1002"))
    )
    (comp (ref "R22")
      (value "1MΩ")
      (fields
        (field (name "BOM_Manufacturer Part") "AR05BTCW1004")
        (field (name "BOM_Supplier Part") "C316223")
      )
      (libsource (lib "") (part "AR05BTCW1004"))
    )
    (comp (ref "R23")
      (value "1.69kΩ")
      (fields
        (field (name "BOM_Manufacturer Part") "ARG05FTC1691")
        (field (name "BOM_Supplier Part") "C218401")
      )
      (libsource (lib "") (part "ARG05FTC1691"))
    )
    (comp (ref "R24")
      (value "1kΩ")
      (fields
        (field (name "BOM_Manufacturer Part") "ARG05BTC1001")
        (field (name "BOM_Supplier Part") "C309081")
      )
      (libsource (lib "") (part "ARG05BTC1001"))
    )
    (comp (ref "R25")
      (value "10kΩ")
      (fields
        (field (name "BOM_Manufacturer Part") "ARG05BTC1002")
        (field (name "BOM_Supplier Part") "C406725")
      )
      (libsource (lib "") (part "ARG05BTC1002"))
    )
    (comp (ref "R26")
      (value "10kΩ")
      (fields
        (field (name "BOM_Manufacturer Part") "ARG05BTC1002")
        (field (name "BOM_Supplier Part") "C406725")
      )
      (libsource (lib "") (part "ARG05BTC1002_1"))
    )
    (comp (ref "R27")
      (value "4.7kΩ")
      (fields
        (field (name "BOM_Manufacturer Part") "RMC08054.7K1%N")
        (field (name "BOM_Supplier Part") "C269746")
      )
      (libsource (lib "") (part "RMC08054.7K1%N"))
    )
    (comp (ref "R28")
      (value "1kΩ")
      (fields
        (field (name "BOM_Manufacturer Part") "ARG05BTC1001")
        (field (name "BOM_Supplier Part") "C309081")
      )
      (libsource (lib "") (part "ARG05BTC1001"))
    )
    (comp (ref "R29")
      (value "1kΩ")
      (fields
        (field (name "BOM_Manufacturer Part") "ARG05BTC1001")
        (field (name "BOM_Supplier Part") "C309081")
      )
      (libsource (lib "") (part "ARG05BTC1001"))
    )
    (comp (ref "R30")
      (value "10kΩ")
      (fields
        (field (name "BOM_Manufacturer Part") "ARG05BTC1002")
        (field (name "BOM_Supplier Part") "C406725")
      )
      (libsource (lib "") (part "ARG05BTC1002_1"))
    )
    (comp (ref "R31")
      (value "10kΩ")
      (fields
        (field (name "BOM_Manufacturer Part") "ARG05BTC1002")
        (field (name "BOM_Supplier Part") "C406725")
      )
      (libsource (lib "") (part "ARG05BTC1002_1"))
    )
    (comp (ref "R32")
      (value "4kΩ")
      (fields
        (field (name "BOM_Manufacturer Part") "ARG05FTC4001N")
        (field (name "BOM_Supplier Part") "C2828855")
      )
      (libsource (lib "") (part "ARG05FTC4001N"))
    )
    (comp (ref "R33")
      (value "0Ω")
      (fields
        (field (name "BOM_Manufacturer Part") "0805W8F0000T5E")
        (field (name "BOM_Supplier Part") "C17477")
      )
      (libsource (lib "") (part "0805W8F0000T5E_1"))
    )
    (comp (ref "R34")
      (value "36Ω")
      (fields
        (field (name "BOM_Manufacturer Part") "AECR0805F36R0K9")
        (field (name "BOM_Supplier Part") "C352217")
      )
      (libsource (lib "") (part "AECR0805F36R0K9"))
    )
    (comp (ref "R35")
      (value "39")
      (fields
        (field (name "BOM_Manufacturer Part") "AC0805JR-0739RL")
        (field (name "BOM_Supplier Part") "C229199")
      )
      (libsource (lib "") (part "AC0805JR-0739RL"))
    )
    (comp (ref "R36")
      (value "4.7kΩ")
      (fields
        (field (name "BOM_Manufacturer Part") "RMC08054.7K1%N")
        (field (name "BOM_Supplier Part") "C269746")
      )
      (libsource (lib "") (part "RMC08054.7K1%N"))
    )
    (comp (ref "R42")
      (value "0Ω")
      (fields
        (field (name "BOM_Manufacturer Part") "0805W8F0000T5E")
        (field (name "BOM_Supplier Part") "C17477")
      )
      (libsource (lib "") (part "0805W8F0000T5E"))
    )
    (comp (ref "R62")
      (value "0Ω")
      (fields
        (field (name "BOM_Manufacturer Part") "0805W8F0000T5E")
        (field (name "BOM_Supplier Part") "C17477")
      )
      (libsource (lib "") (part "0805W8F0000T5E_2"))
    )
    (comp (ref "U8")
      (value "ME6211A12M3G-N")
      (fields (field (name "BOM_Supplier Part") "C236678"))
      (libsource (lib "") (part "ME6211A12M3G-N"))
    )
    (comp (ref "U9")
      (value "LY68L6400SLIT")
      (fields (field (name "BOM_Supplier Part") "C261881"))
      (libsource (lib "") (part "LY68L6400SLIT"))
    )
    (comp (ref "U10")
      (value "USB-TYPE-C-017")
      (fields (field (name "BOM_Supplier Part") "C2927037"))
      (libsource (lib "") (part "USB-TYPE-C-017"))
    )
    (comp (ref "U11")
      (value "XC6206-2.8V")
      (fields (field (name "BOM_Supplier Part") "C2892669"))
      (libsource (lib "") (part "XC6206-2.8V"))
    )
    (comp (ref "U12")
      (value "CP2102-GMR")
      (fields (field (name "BOM_Supplier Part") "C6568"))
      (libsource (lib "") (part "CP2102-GMR"))
    )
    (comp (ref "U13")
      (value "ESP32-S(8MB)")
      (fields (field (name "BOM_Supplier Part") "C2991922"))
      (libsource (lib "") (part "ESP32-S(8MB)"))
    )
    (comp (ref "U14")
      (value "MF-NSMF150-2")
      (fields (field (name "BOM_Supplier Part") "C89655"))
      (libsource (lib "") (part "MF-NSMF150-2"))
    )
    (comp (ref "U15")
      (value "65K5.")
      (fields (field (name "BOM_Supplier Part") "C841299"))
      (libsource (lib "") (part "65K5."))
    )
    (comp (ref "U16")
      (value "ADV7180BCP32Z-RL")
      (fields (field (name "BOM_Supplier Part") "C459884"))
      (libsource (lib "") (part "ADV7180BCP32Z-RL"))
    )
    (comp (ref "X5")
      (value "28.63636MHz")
      (fields
        (field (name "BOM_Manufacturer Part") "7B028636R01")
        (field (name "BOM_Supplier Part") "C655017")
      )
      (libsource (lib "") (part "7B028636R01"))
    )
    (comp (ref "C81")
      (value "2.2uF")
      (fields
        (field (name "BOM_Manufacturer Part") "CC0805ZRY5V7BB225")
        (field (name "BOM_Supplier Part") "C107171")
      )
      (libsource (lib "") (part "CC0805ZRY5V7BB225_1"))
    )
    (comp (ref "C82")
      (value "2.2uF")
      (fields
        (field (name "BOM_Manufacturer Part") "CC0805ZRY5V7BB225")
        (field (name "BOM_Supplier Part") "C107171")
      )
      (libsource (lib "") (part "CC0805ZRY5V7BB225"))
    )
    (comp (ref "C83")
      (value "2.2uF")
      (fields
        (field (name "BOM_Manufacturer Part") "CC0805ZRY5V7BB225")
        (field (name "BOM_Supplier Part") "C107171")
      )
      (libsource (lib "") (part "CC0805ZRY5V7BB225"))
    )
    (comp (ref "C84")
      (value "2.2uF")
      (fields
        (field (name "BOM_Manufacturer Part") "CC0805ZRY5V7BB225")
        (field (name "BOM_Supplier Part") "C107171")
      )
      (libsource (lib "") (part "CC0805ZRY5V7BB225"))
    )
    (comp (ref "C94")
      (value "100nF")
      (fields
        (field (name "BOM_Manufacturer Part") "CL21B104KBCNNNC")
        (field (name "BOM_Supplier Part") "C1711")
      )
      (libsource (lib "") (part "CL21B104KBCNNNC"))
    )
    (comp (ref "C96")
      (value "22uF")
      (fields
        (field (name "BOM_Manufacturer Part") "CL21A226MAQNNNE")
        (field (name "BOM_Supplier Part") "C45783")
      )
      (libsource (lib "") (part "CL21A226MAQNNNE"))
    )
    (comp (ref "CN15")
      (value "A1257WV-S-6P")
      (fields (field (name "BOM_Supplier Part") "C225122"))
      (libsource (lib "") (part "A1257WV-S-6P"))
    )
    (comp (ref "CN17")
      (value "A1257WV-S-6P")
      (fields (field (name "BOM_Supplier Part") "C225122"))
      (libsource (lib "") (part "A1257WV-S-6P"))
    )
    (comp (ref "D1")
      (value "ST34BF")
      (fields (field (name "BOM_Supplier Part") "C414005"))
      (libsource (lib "") (part "ST34BF"))
    )
    (comp (ref "D3")
      (value "ST34BF")
      (fields (field (name "BOM_Supplier Part") "C414005"))
      (libsource (lib "") (part "ST34BF"))
    )
    (comp (ref "D14")
      (value "ST34BF")
      (fields (field (name "BOM_Supplier Part") "C414005"))
      (libsource (lib "") (part "ST34BF"))
    )
    (comp (ref "D60")
      (value "ESD9X5V-2/TR")
      (fields (field (name "BOM_Supplier Part") "C239552"))
      (libsource (lib "") (part "ESD9X5V-2/TR"))
    )
    (comp (ref "D61")
      (value "ESD9X5V-2/TR")
      (fields (field (name "BOM_Supplier Part") "C239552"))
      (libsource (lib "") (part "ESD9X5V-2/TR"))
    )
    (comp (ref "D62")
      (value "ESD9X5V-2/TR")
      (fields (field (name "BOM_Supplier Part") "C239552"))
      (libsource (lib "") (part "ESD9X5V-2/TR"))
    )
    (comp (ref "D63")
      (value "ESD9X5V-2/TR")
      (fields (field (name "BOM_Supplier Part") "C239552"))
      (libsource (lib "") (part "ESD9X5V-2/TR"))
    )
    (comp (ref "R37")
      (value "10kΩ")
      (fields
        (field (name "BOM_Manufacturer Part") "ARG05BTC1002")
        (field (name "BOM_Supplier Part") "C406725")
      )
      (libsource (lib "") (part "ARG05BTC1002"))
    )
    (comp (ref "R38")
      (value "10kΩ")
      (fields
        (field (name "BOM_Manufacturer Part") "ARG05BTC1002")
        (field (name "BOM_Supplier Part") "C406725")
      )
      (libsource (lib "") (part "ARG05BTC1002"))
    )
    (comp (ref "R41")
      (value "300kΩ")
      (fields
        (field (name "BOM_Manufacturer Part") "ERJ6GEYJ304V")
        (field (name "BOM_Supplier Part") "C410067")
      )
      (libsource (lib "") (part "ERJ6GEYJ304V"))
    )
    (comp (ref "R43")
      (value "100kΩ")
      (fields
        (field (name "BOM_Manufacturer Part") "ARG05BTC1003")
        (field (name "BOM_Supplier Part") "C406726")
      )
      (libsource (lib "") (part "ARG05BTC1003"))
    )
    (comp (ref "R44")
      (value "100kΩ")
      (fields
        (field (name "BOM_Manufacturer Part") "ARG05BTC1003")
        (field (name "BOM_Supplier Part") "C406726")
      )
      (libsource (lib "") (part "ARG05BTC1003_1"))
    )
    (comp (ref "R45")
      (value "120")
      (fields
        (field (name "BOM_Manufacturer Part") "AC0805FR-07120RL")
        (field (name "BOM_Supplier Part") "C228277")
      )
      (libsource (lib "") (part "AC0805FR-07120RL_1"))
    )
    (comp (ref "R46")
      (value "120")
      (fields
        (field (name "BOM_Manufacturer Part") "AC0805FR-07120RL")
        (field (name "BOM_Supplier Part") "C228277")
      )
      (libsource (lib "") (part "AC0805FR-07120RL"))
    )
    (comp (ref "R65")
      (value "0Ω")
      (fields
        (field (name "BOM_Manufacturer Part") "0805W8F0000T5E")
        (field (name "BOM_Supplier Part") "C17477")
      )
      (libsource (lib "") (part "0805W8F0000T5E"))
    )
    (comp (ref "R86")
      (value "0Ω")
      (fields
        (field (name "BOM_Manufacturer Part") "0805W8F0000T5E")
        (field (name "BOM_Supplier Part") "C17477")
      )
      (libsource (lib "") (part "0805W8F0000T5E"))
    )
    (comp (ref "R92")
      (value "300kΩ")
      (fields
        (field (name "BOM_Manufacturer Part") "ERJ6GEYJ304V")
        (field (name "BOM_Supplier Part") "C410067")
      )
      (libsource (lib "") (part "ERJ6GEYJ304V"))
    )
    (comp (ref "R93")
      (value "RC0805DR-0780K6L")
      (fields (field (name "BOM_Supplier Part") "C472215"))
      (libsource (lib "") (part "RC0805DR-0780K6L"))
    )
    (comp (ref "U17")
      (value "TJA1051TK/3,118")
      (fields (field (name "BOM_Supplier Part") "C124020"))
      (libsource (lib "") (part "TJA1051TK/3,118"))
    )
    (comp (ref "U19")
      (value "LR1801G-33-SH2-R")
      (fields (field (name "BOM_Supplier Part") "C410479"))
      (libsource (lib "") (part "LR1801G-33-SH2-R"))
    )
    (comp (ref "U20")
      (value "LR1801G-33-SH2-R")
      (fields (field (name "BOM_Supplier Part") "C410479"))
      (libsource (lib "") (part "LR1801G-33-SH2-R"))
    )
    (comp (ref "U21")
      (value "TJA1051TK/3,118")
      (fields (field (name "BOM_Supplier Part") "C124020"))
      (libsource (lib "") (part "TJA1051TK/3,118"))
    )
    (comp (ref "U24")
      (value "TPS25200DRVR")
      (fields (field (name "BOM_Supplier Part") "C128401"))
      (libsource (lib "") (part "TPS25200DRVR"))
    )
  )
  (nets
    (net (code "1") (name "1.8V") (class "Default")
      (node (ref "C66") (pin "1") (pinfunction "1_1") (pintype "unspecified"))
      (node (ref "C67") (pin "2") (pinfunction "2_2") (pintype "unspecified"))
      (node (ref "C69") (pin "1") (pinfunction "1_1") (pintype "unspecified"))
      (node (ref "C72") (pin "1") (pinfunction "1_1") (pintype "input"))
      (node (ref "C73") (pin "1") (pinfunction "1_1") (pintype "input"))
      (node (ref "C74") (pin "1") (pinfunction "1_1") (pintype "input"))
      (node (ref "C75") (pin "1") (pinfunction "1_1") (pintype "input"))
      (node (ref "C76") (pin "2") (pinfunction "2_2") (pintype "unspecified"))
      (node (ref "C77") (pin "2") (pinfunction "2_2") (pintype "unspecified"))
      (node (ref "C78") (pin "1") (pinfunction "1_1") (pintype "unspecified"))
      (node (ref "C79") (pin "2") (pinfunction "2_2") (pintype "unspecified"))
      (node (ref "U15") (pin "2") (pinfunction "VOUT_2") (pintype "unspecified"))
      (node (ref "U16") (pin "14") (pinfunction "DVDD_14") (pintype "unspecified"))
      (node (ref "U16") (pin "18") (pinfunction "PVDD_18") (pintype "unspecified"))
      (node (ref "U16") (pin "22") (pinfunction "AVDD_22") (pintype "unspecified"))
      (node (ref "U16") (pin "30") (pinfunction "DVDD_30") (pintype "unspecified"))
    )
    (net (code "2") (name "3V3_ESP32") (class "Default")
      (node (ref "C41") (pin "2") (pinfunction "2_2") (pintype "input"))
      (node (ref "C42") (pin "2") (pinfunction "2_2") (pintype "unspecified"))
      (node (ref "C52") (pin "1") (pinfunction "1_1") (pintype "input"))
      (node (ref "C56") (pin "2") (pinfunction "2_2") (pintype "input"))
      (node (ref "C58") (pin "2") (pinfunction "2_2") (pintype "input"))
      (node (ref "C59") (pin "2") (pinfunction "2_2") (pintype "input"))
      (node (ref "C61") (pin "2") (pinfunction "2_2") (pintype "unspecified"))
      (node (ref "C62") (pin "1") (pinfunction "1_1") (pintype "unspecified"))
      (node (ref "C70") (pin "1") (pinfunction "1_1") (pintype "unspecified"))
      (node (ref "C71") (pin "1") (pinfunction "1_1") (pintype "input"))
      (node (ref "C80") (pin "2") (pinfunction "2_2") (pintype "unspecified"))
      (node (ref "C84") (pin "2") (pinfunction "2_2") (pintype "unspecified"))
      (node (ref "C86") (pin "2") (pinfunction "2_2") (pintype "unspecified"))
      (node (ref "C88") (pin "2") (pinfunction "2_2") (pintype "unspecified"))
      (node (ref "CARD2") (pin "4") (pinfunction "VDD_4") (pintype "unspecified"))
      (node (ref "CN22") (pin "2") (pinfunction "2_2") (pintype "unspecified"))
      (node (ref "FPC1") (pin "14") (pinfunction "14_14") (pintype "unspecified"))
      (node (ref "R16") (pin "2") (pinfunction "2_2") (pintype "unspecified"))
      (node (ref "R17") (pin "2") (pinfunction "2_2") (pintype "unspecified"))
      (node (ref "R18") (pin "2") (pinfunction "2_2") (pintype "unspecified"))
      (node (ref "R21") (pin "2") (pinfunction "2_2") (pintype "unspecified"))
      (node (ref "R25") (pin "1") (pinfunction "1_1") (pintype "unspecified"))
      (node (ref "R26") (pin "1") (pinfunction "1_1") (pintype "unspecified"))
      (node (ref "R27") (pin "2") (pinfunction "2_2") (pintype "unspecified"))
      (node (ref "R32") (pin "1") (pinfunction "1_1") (pintype "unspecified"))
      (node (ref "R36") (pin "1") (pinfunction "1_1") (pintype "unspecified"))
      (node (ref "R39") (pin "1") (pinfunction "1_1") (pintype "unspecified"))
      (node (ref "R4") (pin "1") (pinfunction "1_1") (pintype "unspecified"))
      (node (ref "R42") (pin "1") (pinfunction "1_1") (pintype "input"))
      (node (ref "R5") (pin "1") (pinfunction "1_1") (pintype "unspecified"))
      (node (ref "R6") (pin "1") (pinfunction "1_1") (pintype "unspecified"))
      (node (ref "R7") (pin "1") (pinfunction "1_1") (pintype "unspecified"))
      (node (ref "R8") (pin "1") (pinfunction "1_1") (pintype "unspecified"))
      (node (ref "U11") (pin "3") (pinfunction "VIN_3") (pintype "unspecified"))
      (node (ref "U12") (pin "6") (pinfunction "VDD_6") (pintype "unspecified"))
      (node (ref "U13") (pin "2") (pinfunction "3V3_2") (pintype "unspecified"))
      (node (ref "U15") (pin "3") (pinfunction "VIN_3") (pintype "unspecified"))
      (node (ref "U16") (pin "3") (pinfunction "DVDDIO_3") (pintype "unspecified"))
      (node (ref "U20") (pin "1") (pinfunction "VOUT_1") (pintype "unspecified"))
      (node (ref "U8") (pin "3") (pinfunction "VIN_3") (pintype "unspecified"))
      (node (ref "U9") (pin "8") (pinfunction "VCC_8") (pintype "unspecified"))
    )
    (net (code "3") (name "3V3_MCU") (class "Default")
      (node (ref "C1") (pin "1") (pinfunction "1_1") (pintype "input"))
      (node (ref "C10") (pin "2") (pinfunction "2_2") (pintype "input"))
      (node (ref "C11") (pin "1") (pinfunction "1_1") (pintype "input"))
      (node (ref "C12") (pin "2") (pinfunction "2_2") (pintype "input"))
      (node (ref "C13") (pin "2") (pinfunction "2_2") (pintype "input"))
      (node (ref "C14") (pin "2") (pinfunction "2_2") (pintype "input"))
      (node (ref "C15") (pin "2") (pinfunction "2_2") (pintype "input"))
      (node (ref "C16") (pin "2") (pinfunction "2_2") (pintype "input"))
      (node (ref "C17") (pin "1") (pinfunction "1_1") (pintype "input"))
      (node (ref "C18") (pin "2") (pinfunction "2_2") (pintype "input"))
      (node (ref "C19") (pin "2") (pinfunction "2_2") (pintype "input"))
      (node (ref "C2") (pin "2") (pinfunction "2_2") (pintype "input"))
      (node (ref "C22") (pin "2") (pinfunction "2_2") (pintype "input"))
      (node (ref "C26") (pin "1") (pinfunction "1_1") (pintype "unspecified"))
      (node (ref "C3") (pin "2") (pinfunction "2_2") (pintype "input"))
      (node (ref "C36") (pin "2") (pinfunction "2_2") (pintype "input"))
      (node (ref "C37") (pin "2") (pinfunction "2_2") (pintype "input"))
      (node (ref "C38") (pin "2") (pinfunction "2_2") (pintype "input"))
      (node (ref "C39") (pin "1") (pinfunction "1_1") (pintype "input"))
      (node (ref "C4") (pin "2") (pinfunction "2_2") (pintype "input"))
      (node (ref "C40") (pin "1") (pinfunction "1_1") (pintype "input"))
      (node (ref "C5") (pin "2") (pinfunction "2_2") (pintype "input"))
      (node (ref "C6") (pin "2") (pinfunction "2_2") (pintype "input"))
      (node (ref "C7") (pin "1") (pinfunction "1_1") (pintype "input"))
      (node (ref "C8") (pin "2") (pinfunction "2_2") (pintype "input"))
      (node (ref "C82") (pin "2") (pinfunction "2_2") (pintype "unspecified"))
      (node (ref "C89") (pin "2") (pinfunction "2_2") (pintype "input"))
      (node (ref "C9") (pin "2") (pinfunction "2_2") (pintype "input"))
      (node (ref "C90") (pin "1") (pinfunction "1_1") (pintype "input"))
      (node (ref "C92") (pin "1") (pinfunction "1_1") (pintype "input"))
      (node (ref "C93") (pin "1") (pinfunction "1_1") (pintype "input"))
      (node (ref "C95") (pin "2") (pinfunction "2_2") (pintype "input"))
      (node (ref "L1") (pin "1") (pinfunction "1_1") (pintype "unspecified"))
      (node (ref "R2") (pin "2") (pinfunction "2_2") (pintype "unspecified"))
      (node (ref "R3") (pin "2") (pinfunction "2_2") (pintype "unspecified"))
      (node (ref "R41") (pin "1") (pinfunction "1_1") (pintype "unspecified"))
      (node (ref "R43") (pin "2") (pinfunction "2_2") (pintype "unspecified"))
      (node (ref "R44") (pin "1") (pinfunction "1_1") (pintype "unspecified"))
      (node (ref "R49") (pin "2") (pinfunction "2_2") (pintype "unspecified"))
      (node (ref "R50") (pin "2") (pinfunction "2_2") (pintype "unspecified"))
      (node (ref "R51") (pin "2") (pinfunction "2_2") (pintype "unspecified"))
      (node (ref "R52") (pin "2") (pinfunction "2_2") (pintype "unspecified"))
      (node (ref "R58") (pin "2") (pinfunction "2_2") (pintype "unspecified"))
      (node (ref "R88") (pin "2") (pinfunction "2_2") (pintype "input"))
      (node (ref "SW2") (pin "1") (pinfunction "1_1") (pintype "unspecified"))
      (node (ref "U1") (pin "113") (pinfunction "VDD_113") (pintype "unspecified"))
      (node (ref "U1") (pin "120") (pinfunction "VDD50USB_120") (pintype "unspecified"))
      (node (ref "U1") (pin "121") (pinfunction "VDD33USB_121") (pintype "unspecified"))
      (node (ref "U1") (pin "126") (pinfunction "VDD_126") (pintype "unspecified"))
      (node (ref "U1") (pin "13") (pinfunction "VDD_13") (pintype "unspecified"))
      (node (ref "U1") (pin "135") (pinfunction "VDDLDO_135") (pintype "unspecified"))
      (node (ref "U1") (pin "136") (pinfunction "VDD_136") (pintype "unspecified"))
      (node (ref "U1") (pin "152") (pinfunction "VDD_152") (pintype "unspecified"))
      (node (ref "U1") (pin "160") (pinfunction "VDD_160") (pintype "unspecified"))
      (node (ref "U1") (pin "174") (pinfunction "PDR_ON_174") (pintype "unspecified"))
      (node (ref "U1") (pin "175") (pinfunction "VDDLDO_175") (pintype "unspecified"))
      (node (ref "U1") (pin "176") (pinfunction "VDD_176") (pintype "unspecified"))
      (node (ref "U1") (pin "25") (pinfunction "VDD_25") (pintype "unspecified"))
      (node (ref "U1") (pin "44") (pinfunction "VDD_44") (pintype "unspecified"))
      (node (ref "U1") (pin "48") (pinfunction "VDD_48") (pintype "unspecified"))
      (node (ref "U1") (pin "65") (pinfunction "VDD_65") (pintype "unspecified"))
      (node (ref "U1") (pin "7") (pinfunction "VDD_7") (pintype "unspecified"))
      (node (ref "U1") (pin "71") (pinfunction "VDD_71") (pintype "unspecified"))
      (node (ref "U1") (pin "8") (pinfunction "VBAT_8") (pintype "unspecified"))
      (node (ref "U1") (pin "82") (pinfunction "VDDLDO_82") (pintype "unspecified"))
      (node (ref "U1") (pin "84") (pinfunction "VDD_84") (pintype "unspecified"))
      (node (ref "U1") (pin "92") (pinfunction "VDD_92") (pintype "unspecified"))
      (node (ref "U1") (pin "99") (pinfunction "VDD_99") (pintype "unspecified"))
      (node (ref "U17") (pin "5") (pinfunction "VIO_5") (pintype "bidirectional"))
      (node (ref "U19") (pin "1") (pinfunction "VOUT_1") (pintype "unspecified"))
      (node (ref "U2") (pin "1") (pinfunction "VDDIO_1") (pintype "unspecified"))
      (node (ref "U2") (pin "10") (pinfunction "VDD_10") (pintype "unspecified"))
      (node (ref "U21") (pin "5") (pinfunction "VIO_5") (pintype "bidirectional"))
      (node (ref "U25") (pin "10") (pinfunction "OE_10") (pintype "unspecified"))
      (node (ref "U25") (pin "19") (pinfunction "VCCB_19") (pintype "unspecified"))
      (node (ref "U25") (pin "2") (pinfunction "VCCA_2") (pintype "unspecified"))
      (node (ref "U26") (pin "10") (pinfunction "OE_10") (pintype "unspecified"))
      (node (ref "U26") (pin "2") (pinfunction "VCCA_2") (pintype "unspecified"))
      (node (ref "U27") (pin "10") (pinfunction "10_10") (pintype "unspecified"))
      (node (ref "U29") (pin "10") (pinfunction "OE_10") (pintype "unspecified"))
      (node (ref "U29") (pin "19") (pinfunction "VCCB_19") (pintype "unspecified"))
      (node (ref "U29") (pin "2") (pinfunction "VCCA_2") (pintype "unspecified"))
      (node (ref "U3") (pin "13") (pinfunction "VDDIO_13") (pintype "unspecified"))
      (node (ref "U3") (pin "2") (pinfunction "VDD_2") (pintype "unspecified"))
      (node (ref "U3") (pin "4") (pinfunction "S1_4") (pintype "unspecified"))
      (node (ref "U4") (pin "5") (pinfunction "VDDIO_5") (pintype "unspecified"))
      (node (ref "U4") (pin "8") (pinfunction "VDD_8") (pintype "unspecified"))
      (node (ref "U7") (pin "2") (pinfunction "VREF1_2") (pintype "unspecified"))
    )
    (net (code "4") (name "ADC1_3V3") (class "Default")
      (node (ref "CN24") (pin "6") (pinfunction "6_6") (pintype "unspecified"))
      (node (ref "D33") (pin "1") (pinfunction "1_1") (pintype "unspecified"))
      (node (ref "U1") (pin "29") (pinfunction "PF9_29") (pintype "unspecified"))
    )
    (net (code "5") (name "ADC2_3V3") (class "Default")
      (node (ref "CN24") (pin "7") (pinfunction "7_7") (pintype "unspecified"))
      (node (ref "D34") (pin "1") (pinfunction "1_1") (pintype "unspecified"))
      (node (ref "U1") (pin "23") (pinfunction "PF5_23") (pintype "unspecified"))
    )
    (net (code "6") (name "AGND") (class "Default")
      (node (ref "C1") (pin "2") (pinfunction "2_2") (pintype "input"))
      (node (ref "C10") (pin "1") (pinfunction "1_1") (pintype "input"))
      (node (ref "C11") (pin "2") (pinfunction "2_2") (pintype "input"))
      (node (ref "C12") (pin "1") (pinfunction "1_1") (pintype "input"))
      (node (ref "C13") (pin "1") (pinfunction "1_1") (pintype "input"))
      (node (ref "C14") (pin "1") (pinfunction "1_1") (pintype "input"))
      (node (ref "C15") (pin "1") (pinfunction "1_1") (pintype "input"))
      (node (ref "C16") (pin "1") (pinfunction "1_1") (pintype "input"))
      (node (ref "C17") (pin "2") (pinfunction "2_2") (pintype "input"))
      (node (ref "C18") (pin "1") (pinfunction "1_1") (pintype "input"))
      (node (ref "C19") (pin "1") (pinfunction "1_1") (pintype "input"))
      (node (ref "C2") (pin "1") (pinfunction "1_1") (pintype "input"))
      (node (ref "C20") (pin "2") (pinfunction "2_2") (pintype "input"))
      (node (ref "C21") (pin "1") (pinfunction "1_1") (pintype "input"))
      (node (ref "C22") (pin "1") (pinfunction "1_1") (pintype "input"))
      (node (ref "C23") (pin "1") (pinfunction "1_1") (pintype "unspecified"))
      (node (ref "C24") (pin "2") (pinfunction "2_2") (pintype "unspecified"))
      (node (ref "C25") (pin "1") (pinfunction "1_1") (pintype "unspecified"))
      (node (ref "C26") (pin "2") (pinfunction "2_2") (pintype "unspecified"))
      (node (ref "C27") (pin "2") (pinfunction "2_2") (pintype "input"))
      (node (ref "C28") (pin "2") (pinfunction "2_2") (pintype "input"))
      (node (ref "C29") (pin "1") (pinfunction "1_1") (pintype "input"))
      (node (ref "C3") (pin "1") (pinfunction "1_1") (pintype "input"))
      (node (ref "C30") (pin "1") (pinfunction "1_1") (pintype "input"))
      (node (ref "C31") (pin "1") (pinfunction "1_1") (pintype "unspecified"))
      (node (ref "C32") (pin "1") (pinfunction "1_1") (pintype "unspecified"))
      (node (ref "C33") (pin "1") (pinfunction "1_1") (pintype "input"))
      (node (ref "C34") (pin "1") (pinfunction "1_1") (pintype "input"))
      (node (ref "C36") (pin "1") (pinfunction "1_1") (pintype "input"))
      (node (ref "C37") (pin "1") (pinfunction "1_1") (pintype "input"))
      (node (ref "C38") (pin "1") (pinfunction "1_1") (pintype "input"))
      (node (ref "C39") (pin "2") (pinfunction "2_2") (pintype "input"))
      (node (ref "C4") (pin "1") (pinfunction "1_1") (pintype "input"))
      (node (ref "C40") (pin "2") (pinfunction "2_2") (pintype "input"))
      (node (ref "C41") (pin "1") (pinfunction "1_1") (pintype "input"))
      (node (ref "C42") (pin "1") (pinfunction "1_1") (pintype "unspecified"))
      (node (ref "C43") (pin "1") (pinfunction "1_1") (pintype "unspecified"))
      (node (ref "C44") (pin "1") (pinfunction "1_1") (pintype "unspecified"))
      (node (ref "C46") (pin "1") (pinfunction "1_1") (pintype "input"))
      (node (ref "C47") (pin "1") (pinfunction "1_1") (pintype "input"))
      (node (ref "C48") (pin "1") (pinfunction "1_1") (pintype "input"))
      (node (ref "C5") (pin "1") (pinfunction "1_1") (pintype "input"))
      (node (ref "C52") (pin "2") (pinfunction "2_2") (pintype "input"))
      (node (ref "C53") (pin "2") (pinfunction "2_2") (pintype "input"))
      (node (ref "C54") (pin "1") (pinfunction "1_1") (pintype "input"))
      (node (ref "C55") (pin "2") (pinfunction "2_2") (pintype "unspecified"))
      (node (ref "C56") (pin "1") (pinfunction "1_1") (pintype "input"))
      (node (ref "C57") (pin "1") (pinfunction "1_1") (pintype "input"))
      (node (ref "C58") (pin "1") (pinfunction "1_1") (pintype "input"))
      (node (ref "C59") (pin "1") (pinfunction "1_1") (pintype "input"))
      (node (ref "C6") (pin "1") (pinfunction "1_1") (pintype "input"))
      (node (ref "C60") (pin "1") (pinfunction "1_1") (pintype "unspecified"))
      (node (ref "C61") (pin "1") (pinfunction "1_1") (pintype "unspecified"))
      (node (ref "C62") (pin "2") (pinfunction "2_2") (pintype "unspecified"))
      (node (ref "C63") (pin "2") (pinfunction "2_2") (pintype "unspecified"))
      (node (ref "C64") (pin "1") (pinfunction "1_1") (pintype "unspecified"))
      (node (ref "C67") (pin "1") (pinfunction "1_1") (pintype "unspecified"))
      (node (ref "C7") (pin "2") (pinfunction "2_2") (pintype "input"))
      (node (ref "C70") (pin "2") (pinfunction "2_2") (pintype "unspecified"))
      (node (ref "C71") (pin "2") (pinfunction "2_2") (pintype "input"))
      (node (ref "C72") (pin "2") (pinfunction "2_2") (pintype "input"))
      (node (ref "C73") (pin "2") (pinfunction "2_2") (pintype "input"))
      (node (ref "C74") (pin "2") (pinfunction "2_2") (pintype "input"))
      (node (ref "C75") (pin "2") (pinfunction "2_2") (pintype "input"))
      (node (ref "C76") (pin "1") (pinfunction "1_1") (pintype "unspecified"))
      (node (ref "C77") (pin "1") (pinfunction "1_1") (pintype "unspecified"))
      (node (ref "C78") (pin "2") (pinfunction "2_2") (pintype "unspecified"))
      (node (ref "C79") (pin "1") (pinfunction "1_1") (pintype "unspecified"))
      (node (ref "C8") (pin "1") (pinfunction "1_1") (pintype "input"))
      (node (ref "C80") (pin "1") (pinfunction "1_1") (pintype "unspecified"))
      (node (ref "C81") (pin "2") (pinfunction "2_2") (pintype "unspecified"))
      (node (ref "C82") (pin "1") (pinfunction "1_1") (pintype "unspecified"))
      (node (ref "C83") (pin "1") (pinfunction "1_1") (pintype "unspecified"))
      (node (ref "C84") (pin "1") (pinfunction "1_1") (pintype "unspecified"))
      (node (ref "C85") (pin "2") (pinfunction "2_2") (pintype "unspecified"))
      (node (ref "C86") (pin "1") (pinfunction "1_1") (pintype "unspecified"))
      (node (ref "C88") (pin "1") (pinfunction "1_1") (pintype "unspecified"))
      (node (ref "C89") (pin "1") (pinfunction "1_1") (pintype "input"))
      (node (ref "C9") (pin "1") (pinfunction "1_1") (pintype "input"))
      (node (ref "C90") (pin "2") (pinfunction "2_2") (pintype "input"))
      (node (ref "C91") (pin "1") (pinfunction "1_1") (pintype "input"))
      (node (ref "C92") (pin "2") (pinfunction "2_2") (pintype "input"))
      (node (ref "C93") (pin "2") (pinfunction "2_2") (pintype "input"))
      (node (ref "C94") (pin "1") (pinfunction "1_1") (pintype "input"))
      (node (ref "C95") (pin "1") (pinfunction "1_1") (pintype "input"))
      (node (ref "C96") (pin "1") (pinfunction "1_1") (pintype "unspecified"))
      (node (ref "CARD2") (pin "10") (pinfunction "GND_10") (pintype "unspecified"))
      (node (ref "CARD2") (pin "6") (pinfunction "VSS_6") (pintype "unspecified"))
      (node (ref "CN1") (pin "7") (pinfunction "7_7") (pintype "unspecified"))
      (node (ref "CN1") (pin "8") (pinfunction "8_8") (pintype "unspecified"))
      (node (ref "CN1") (pin "9") (pinfunction "9_9") (pintype "unspecified"))
      (node (ref "CN10") (pin "4") (pinfunction "4_4") (pintype "unspecified"))
      (node (ref "CN10") (pin "5") (pinfunction "5_5") (pintype "unspecified"))
      (node (ref "CN10") (pin "6") (pinfunction "6_6") (pintype "unspecified"))
      (node (ref "CN11") (pin "4") (pinfunction "4_4") (pintype "unspecified"))
      (node (ref "CN11") (pin "5") (pinfunction "5_5") (pintype "unspecified"))
      (node (ref "CN11") (pin "6") (pinfunction "6_6") (pintype "unspecified"))
      (node (ref "CN14") (pin "1") (pinfunction "1_1") (pintype "unspecified"))
      (node (ref "CN14") (pin "11") (pinfunction "11_11") (pintype "unspecified"))
      (node (ref "CN14") (pin "12") (pinfunction "12_12") (pintype "unspecified"))
      (node (ref "CN15") (pin "5") (pinfunction "5_5") (pintype "unspecified"))
      (node (ref "CN15") (pin "6") (pinfunction "6_6") (pintype "unspecified"))
      (node (ref "CN15") (pin "7") (pinfunction "7_7") (pintype "unspecified"))
      (node (ref "CN15") (pin "8") (pinfunction "8_8") (pintype "unspecified"))
      (node (ref "CN16") (pin "10") (pinfunction "10_10") (pintype "unspecified"))
      (node (ref "CN16") (pin "11") (pinfunction "11_11") (pintype "unspecified"))
      (node (ref "CN16") (pin "12") (pinfunction "12_12") (pintype "unspecified"))
      (node (ref "CN17") (pin "5") (pinfunction "5_5") (pintype "unspecified"))
      (node (ref "CN17") (pin "6") (pinfunction "6_6") (pintype "unspecified"))
      (node (ref "CN17") (pin "7") (pinfunction "7_7") (pintype "unspecified"))
      (node (ref "CN17") (pin "8") (pinfunction "8_8") (pintype "unspecified"))
      (node (ref "CN18") (pin "1") (pinfunction "1_1") (pintype "unspecified"))
      (node (ref "CN18") (pin "4") (pinfunction "4_4") (pintype "unspecified"))
      (node (ref "CN18") (pin "5") (pinfunction "5_5") (pintype "unspecified"))
      (node (ref "CN19") (pin "1") (pinfunction "1_1") (pintype "unspecified"))
      (node (ref "CN19") (pin "4") (pinfunction "4_4") (pintype "unspecified"))
      (node (ref "CN19") (pin "5") (pinfunction "5_5") (pintype "unspecified"))
      (node (ref "CN2") (pin "7") (pinfunction "7_7") (pintype "unspecified"))
      (node (ref "CN2") (pin "8") (pinfunction "8_8") (pintype "unspecified"))
      (node (ref "CN2") (pin "9") (pinfunction "9_9") (pintype "unspecified"))
      (node (ref "CN20") (pin "5") (pinfunction "5_5") (pintype "unspecified"))
      (node (ref "CN20") (pin "6") (pinfunction "6_6") (pintype "unspecified"))
      (node (ref "CN20") (pin "7") (pinfunction "7_7") (pintype "unspecified"))
      (node (ref "CN21") (pin "3") (pinfunction "3_3") (pintype "unspecified"))
      (node (ref "CN21") (pin "4") (pinfunction "4_4") (pintype "unspecified"))
      (node (ref "CN21") (pin "5") (pinfunction "5_5") (pintype "unspecified"))
      (node (ref "CN22") (pin "5") (pinfunction "5_5") (pintype "unspecified"))
      (node (ref "CN22") (pin "6") (pinfunction "6_6") (pintype "unspecified"))
      (node (ref "CN22") (pin "7") (pinfunction "7_7") (pintype "unspecified"))
      (node (ref "CN24") (pin "10") (pinfunction "10_10") (pintype "unspecified"))
      (node (ref "CN24") (pin "8") (pinfunction "8_8") (pintype "unspecified"))
      (node (ref "CN24") (pin "9") (pinfunction "9_9") (pintype "unspecified"))
      (node (ref "CN3") (pin "6") (pinfunction "6_6") (pintype "unspecified"))
      (node (ref "CN3") (pin "7") (pinfunction "7_7") (pintype "unspecified"))
      (node (ref "CN3") (pin "8") (pinfunction "8_8") (pintype "unspecified"))
      (node (ref "CN4") (pin "6") (pinfunction "6_6") (pintype "unspecified"))
      (node (ref "CN4") (pin "7") (pinfunction "7_7") (pintype "unspecified"))
      (node (ref "CN4") (pin "8") (pinfunction "8_8") (pintype "unspecified"))
      (node (ref "CN5") (pin "6") (pinfunction "6_6") (pintype "unspecified"))
      (node (ref "CN5") (pin "7") (pinfunction "7_7") (pintype "unspecified"))
      (node (ref "CN5") (pin "8") (pinfunction "8_8") (pintype "unspecified"))
      (node (ref "CN6") (pin "4") (pinfunction "4_4") (pintype "unspecified"))
      (node (ref "CN6") (pin "5") (pinfunction "5_5") (pintype "unspecified"))
      (node (ref "CN6") (pin "6") (pinfunction "6_6") (pintype "unspecified"))
      (node (ref "CN7") (pin "4") (pinfunction "4_4") (pintype "unspecified"))
      (node (ref "CN7") (pin "5") (pinfunction "5_5") (pintype "unspecified"))
      (node (ref "CN7") (pin "6") (pinfunction "6_6") (pintype "unspecified"))
      (node (ref "CN8") (pin "4") (pinfunction "4_4") (pintype "unspecified"))
      (node (ref "CN8") (pin "5") (pinfunction "5_5") (pintype "unspecified"))
      (node (ref "CN8") (pin "6") (pinfunction "6_6") (pintype "unspecified"))
      (node (ref "CN9") (pin "4") (pinfunction "4_4") (pintype "unspecified"))
      (node (ref "CN9") (pin "5") (pinfunction "5_5") (pintype "unspecified"))
      (node (ref "CN9") (pin "6") (pinfunction "6_6") (pintype "unspecified"))
      (node (ref "D10") (pin "2") (pinfunction "2_2") (pintype "unspecified"))
      (node (ref "D11") (pin "2") (pinfunction "2_2") (pintype "unspecified"))
      (node (ref "D12") (pin "2") (pinfunction "2_2") (pintype "unspecified"))
      (node (ref "D13") (pin "2") (pinfunction "2_2") (pintype "unspecified"))
      (node (ref "D15") (pin "2") (pinfunction "2_2") (pintype "unspecified"))
      (node (ref "D16") (pin "2") (pinfunction "2_2") (pintype "unspecified"))
      (node (ref "D17") (pin "2") (pinfunction "2_2") (pintype "unspecified"))
      (node (ref "D18") (pin "2") (pinfunction "2_2") (pintype "unspecified"))
      (node (ref "D19") (pin "2") (pinfunction "2_2") (pintype "unspecified"))
      (node (ref "D20") (pin "2") (pinfunction "2_2") (pintype "unspecified"))
      (node (ref "D21") (pin "2") (pinfunction "2_2") (pintype "unspecified"))
      (node (ref "D22") (pin "2") (pinfunction "2_2") (pintype "unspecified"))
      (node (ref "D23") (pin "2") (pinfunction "2_2") (pintype "unspecified"))
      (node (ref "D24") (pin "2") (pinfunction "2_2") (pintype "unspecified"))
      (node (ref "D25") (pin "2") (pinfunction "2_2") (pintype "unspecified"))
      (node (ref "D26") (pin "2") (pinfunction "2_2") (pintype "unspecified"))
      (node (ref "D27") (pin "2") (pinfunction "2_2") (pintype "unspecified"))
      (node (ref "D28") (pin "2") (pinfunction "2_2") (pintype "unspecified"))
      (node (ref "D29") (pin "2") (pinfunction "2_2") (pintype "unspecified"))
      (node (ref "D30") (pin "2") (pinfunction "2_2") (pintype "unspecified"))
      (node (ref "D31") (pin "2") (pinfunction "2_2") (pintype "unspecified"))
      (node (ref "D32") (pin "2") (pinfunction "2_2") (pintype "unspecified"))
      (node (ref "D33") (pin "2") (pinfunction "2_2") (pintype "unspecified"))
      (node (ref "D34") (pin "2") (pinfunction "2_2") (pintype "unspecified"))
      (node (ref "D35") (pin "2") (pinfunction "2_2") (pintype "unspecified"))
      (node (ref "D36") (pin "2") (pinfunction "2_2") (pintype "unspecified"))
      (node (ref "D37") (pin "2") (pinfunction "2_2") (pintype "unspecified"))
      (node (ref "D38") (pin "2") (pinfunction "2_2") (pintype "unspecified"))
      (node (ref "D39") (pin "2") (pinfunction "2_2") (pintype "unspecified"))
      (node (ref "D4") (pin "2") (pinfunction "2_2") (pintype "unspecified"))
      (node (ref "D40") (pin "2") (pinfunction "2_2") (pintype "unspecified"))
      (node (ref "D41") (pin "2") (pinfunction "2_2") (pintype "unspecified"))
      (node (ref "D42") (pin "2") (pinfunction "2_2") (pintype "unspecified"))
      (node (ref "D43") (pin "2") (pinfunction "2_2") (pintype "unspecified"))
      (node (ref "D44") (pin "2") (pinfunction "2_2") (pintype "unspecified"))
      (node (ref "D45") (pin "2") (pinfunction "2_2") (pintype "unspecified"))
      (node (ref "D46") (pin "2") (pinfunction "2_2") (pintype "unspecified"))
      (node (ref "D47") (pin "2") (pinfunction "2_2") (pintype "unspecified"))
      (node (ref "D48") (pin "2") (pinfunction "2_2") (pintype "unspecified"))
      (node (ref "D49") (pin "2") (pinfunction "2_2") (pintype "unspecified"))
      (node (ref "D5") (pin "2") (pinfunction "2_2") (pintype "unspecified"))
      (node (ref "D50") (pin "2") (pinfunction "2_2") (pintype "unspecified"))
      (node (ref "D51") (pin "2") (pinfunction "2_2") (pintype "unspecified"))
      (node (ref "D52") (pin "2") (pinfunction "2_2") (pintype "unspecified"))
      (node (ref "D53") (pin "2") (pinfunction "2_2") (pintype "unspecified"))
      (node (ref "D54") (pin "2") (pinfunction "2_2") (pintype "unspecified"))
      (node (ref "D55") (pin "2") (pinfunction "2_2") (pintype "unspecified"))
      (node (ref "D56") (pin "2") (pinfunction "2_2") (pintype "unspecified"))
      (node (ref "D57") (pin "2") (pinfunction "2_2") (pintype "unspecified"))
      (node (ref "D58") (pin "2") (pinfunction "2_2") (pintype "unspecified"))
      (node (ref "D59") (pin "2") (pinfunction "2_2") (pintype "unspecified"))
      (node (ref "D6") (pin "2") (pinfunction "2_2") (pintype "unspecified"))
      (node (ref "D60") (pin "2") (pinfunction "2_2") (pintype "unspecified"))
      (node (ref "D61") (pin "2") (pinfunction "2_2") (pintype "unspecified"))
      (node (ref "D62") (pin "2") (pinfunction "2_2") (pintype "unspecified"))
      (node (ref "D63") (pin "2") (pinfunction "2_2") (pintype "unspecified"))
      (node (ref "D64") (pin "2") (pinfunction "2_2") (pintype "unspecified"))
      (node (ref "D65") (pin "2") (pinfunction "2_2") (pintype "unspecified"))
      (node (ref "D7") (pin "2") (pinfunction "2_2") (pintype "unspecified"))
      (node (ref "D8") (pin "2") (pinfunction "2_2") (pintype "unspecified"))
      (node (ref "D9") (pin "2") (pinfunction "2_2") (pintype "unspecified"))
      (node (ref "FPC1") (pin "10") (pinfunction "10_10") (pintype "unspecified"))
      (node (ref "FPC1") (pin "23") (pinfunction "23_23") (pintype "unspecified"))
      (node (ref "FPC1") (pin "25") (pinfunction "25_25") (pintype "unspecified"))
      (node (ref "FPC1") (pin "26") (pinfunction "26_26") (pintype "unspecified"))
      (node (ref "LED1") (pin "2") (pinfunction "-_2") (pintype "unspecified"))
      (node (ref "R14") (pin "1") (pinfunction "1_1") (pintype "unspecified"))
      (node (ref "R19") (pin "2") (pinfunction "2_2") (pintype "unspecified"))
      (node (ref "R20") (pin "2") (pinfunction "2_2") (pintype "unspecified"))
      (node (ref "R24") (pin "2") (pinfunction "2_2") (pintype "unspecified"))
      (node (ref "R33") (pin "1") (pinfunction "1_1") (pintype "input"))
      (node (ref "R35") (pin "1") (pinfunction "1_1") (pintype "unspecified"))
      (node (ref "R47") (pin "2") (pinfunction "2_2") (pintype "unspecified"))
      (node (ref "R48") (pin "2") (pinfunction "2_2") (pintype "unspecified"))
      (node (ref "R63") (pin "1") (pinfunction "1_1") (pintype "unspecified"))
      (node (ref "R93") (pin "1") (pinfunction "1_1") (pintype "unspecified"))
      (node (ref "SW1") (pin "2") (pinfunction "2_2") (pintype "unspecified"))
      (node (ref "SW1") (pin "4") (pinfunction "4_4") (pintype "unspecified"))
      (node (ref "SW2") (pin "3") (pinfunction "3_3") (pintype "unspecified"))
      (node (ref "SW2") (pin "4") (pinfunction "4_4") (pintype "unspecified"))
      (node (ref "SW2") (pin "5") (pinfunction "5_5") (pintype "unspecified"))
      (node (ref "SW2") (pin "6") (pinfunction "6_6") (pintype "unspecified"))
      (node (ref "SW2") (pin "7") (pinfunction "7_7") (pintype "unspecified"))
      (node (ref "U1") (pin "100") (pinfunction "VSS_100") (pintype "unspecified"))
      (node (ref "U1") (pin "105") (pinfunction "VSSDSI_105") (pintype "unspecified"))
      (node (ref "U1") (pin "109") (pinfunction "VSSDSI_109") (pintype "unspecified"))
      (node (ref "U1") (pin "112") (pinfunction "VSS_112") (pintype "unspecified"))
      (node (ref "U1") (pin "119") (pinfunction "VSS_119") (pintype "unspecified"))
      (node (ref "U1") (pin "12") (pinfunction "VSS_12") (pintype "unspecified"))
      (node (ref "U1") (pin "134") (pinfunction "VSS_134") (pintype "unspecified"))
      (node (ref "U1") (pin "137") (pinfunction "VSS_137") (pintype "unspecified"))
      (node (ref "U1") (pin "14") (pinfunction "VSSSMPS_14") (pintype "unspecified"))
      (node (ref "U1") (pin "151") (pinfunction "VSS_151") (pintype "unspecified"))
      (node (ref "U1") (pin "159") (pinfunction "VSS_159") (pintype "unspecified"))
      (node (ref "U1") (pin "173") (pinfunction "VSS_173") (pintype "unspecified"))
      (node (ref "U1") (pin "24") (pinfunction "VSS_24") (pintype "unspecified"))
      (node (ref "U1") (pin "38") (pinfunction "VSSA_38") (pintype "unspecified"))
      (node (ref "U1") (pin "45") (pinfunction "VSS_45") (pintype "unspecified"))
      (node (ref "U1") (pin "47") (pinfunction "VSS_47") (pintype "unspecified"))
      (node (ref "U1") (pin "6") (pinfunction "VSS_6") (pintype "unspecified"))
      (node (ref "U1") (pin "64") (pinfunction "VSS_64") (pintype "unspecified"))
      (node (ref "U1") (pin "70") (pinfunction "VSS_70") (pintype "unspecified"))
      (node (ref "U1") (pin "81") (pinfunction "VSS_81") (pintype "unspecified"))
      (node (ref "U1") (pin "83") (pinfunction "VSS_83") (pintype "unspecified"))
      (node (ref "U1") (pin "93") (pinfunction "VSS_93") (pintype "unspecified"))
      (node (ref "U10") (pin "1") (pinfunction "1_1") (pintype "unspecified"))
      (node (ref "U10") (pin "2") (pinfunction "2_2") (pintype "unspecified"))
      (node (ref "U10") (pin "3") (pinfunction "3_3") (pintype "unspecified"))
      (node (ref "U10") (pin "4") (pinfunction "4_4") (pintype "unspecified"))
      (node (ref "U10") (pin "A1B12") (pinfunction "GND_A1B12") (pintype "unspecified"))
      (node (ref "U10") (pin "B1A12") (pinfunction "GND_B1A12") (pintype "unspecified"))
      (node (ref "U11") (pin "1") (pinfunction "VSS_1") (pintype "unspecified"))
      (node (ref "U12") (pin "29") (pinfunction "EP_29") (pintype "unspecified"))
      (node (ref "U12") (pin "3") (pinfunction "GND_3") (pintype "unspecified"))
      (node (ref "U13") (pin "1") (pinfunction "GND_1") (pintype "unspecified"))
      (node (ref "U13") (pin "15") (pinfunction "GND_15") (pintype "unspecified"))
      (node (ref "U13") (pin "38") (pinfunction "GND_38") (pintype "unspecified"))
      (node (ref "U13") (pin "39") (pinfunction "EP_39") (pintype "unspecified"))
      (node (ref "U15") (pin "1") (pinfunction "VSS_1") (pintype "unspecified"))
      (node (ref "U16") (pin "2") (pinfunction "DGND_2") (pintype "unspecified"))
      (node (ref "U16") (pin "29") (pinfunction "DGND_29") (pintype "unspecified"))
      (node (ref "U16") (pin "33") (pinfunction "EP_33") (pintype "unspecified"))
      (node (ref "U17") (pin "2") (pinfunction "GND_2") (pintype "bidirectional"))
      (node (ref "U17") (pin "9") (pinfunction "EP_9") (pintype "bidirectional"))
      (node (ref "U19") (pin "4") (pinfunction "GND_4") (pintype "unspecified"))
      (node (ref "U19") (pin "9") (pinfunction "EP_9") (pintype "unspecified"))
      (node (ref "U2") (pin "3") (pinfunction "VSS_3") (pintype "unspecified"))
      (node (ref "U2") (pin "8") (pinfunction "VSS_8") (pintype "unspecified"))
      (node (ref "U2") (pin "9") (pinfunction "VSS_9") (pintype "unspecified"))
      (node (ref "U20") (pin "4") (pinfunction "GND_4") (pintype "unspecified"))
      (node (ref "U20") (pin "9") (pinfunction "EP_9") (pintype "unspecified"))
      (node (ref "U21") (pin "2") (pinfunction "GND_2") (pintype "bidirectional"))
      (node (ref "U21") (pin "9") (pinfunction "EP_9") (pintype "bidirectional"))
      (node (ref "U22") (pin "2") (pinfunction "GND_2") (pintype "unspecified"))
      (node (ref "U23") (pin "1") (pinfunction "1_1") (pintype "unspecified"))
      (node (ref "U23") (pin "2") (pinfunction "2_2") (pintype "unspecified"))
      (node (ref "U23") (pin "3") (pinfunction "3_3") (pintype "unspecified"))
      (node (ref "U23") (pin "4") (pinfunction "4_4") (pintype "unspecified"))
      (node (ref "U23") (pin "A1B12") (pinfunction "GND_A1B12") (pintype "unspecified"))
      (node (ref "U23") (pin "B1A12") (pinfunction "GND_B1A12") (pintype "unspecified"))
      (node (ref "U24") (pin "5") (pinfunction "GND_5") (pintype "unspecified"))
      (node (ref "U24") (pin "7") (pinfunction "EP_7") (pintype "unspecified"))
      (node (ref "U25") (pin "11") (pinfunction "GND_11") (pintype "unspecified"))
      (node (ref "U25") (pin "21") (pinfunction "EP_21") (pintype "unspecified"))
      (node (ref "U26") (pin "11") (pinfunction "GND_11") (pintype "unspecified"))
      (node (ref "U26") (pin "21") (pinfunction "EP_21") (pintype "unspecified"))
      (node (ref "U27") (pin "11") (pinfunction "11_11") (pintype "unspecified"))
      (node (ref "U27") (pin "12") (pinfunction "12_12") (pintype "unspecified"))
      (node (ref "U27") (pin "13") (pinfunction "13_13") (pintype "unspecified"))
      (node (ref "U29") (pin "11") (pinfunction "GND_11") (pintype "unspecified"))
      (node (ref "U29") (pin "21") (pinfunction "EP_21") (pintype "unspecified"))
      (node (ref "U3") (pin "11") (pinfunction "GND_11") (pintype "unspecified"))
      (node (ref "U3") (pin "9") (pinfunction "GND_9") (pintype "unspecified"))
      (node (ref "U4") (pin "2") (pinfunction "SDx_2") (pintype "unspecified"))
      (node (ref "U4") (pin "3") (pinfunction "SCx_3") (pintype "unspecified"))
      (node (ref "U4") (pin "6") (pinfunction "GND_6") (pintype "unspecified"))
      (node (ref "U4") (pin "7") (pinfunction "GND_7") (pintype "unspecified"))
      (node (ref "U5") (pin "21") (pinfunction "GND_21") (pintype "unspecified"))
      (node (ref "U5") (pin "3") (pinfunction "GND_3") (pintype "unspecified"))
      (node (ref "U5") (pin "5") (pinfunction "GND_5") (pintype "unspecified"))
      (node (ref "U6") (pin "20") (pinfunction "AGND_20") (pintype "unspecified"))
      (node (ref "U6") (pin "23") (pinfunction "PGND_23") (pintype "unspecified"))
      (node (ref "U6") (pin "29") (pinfunction "EP_29") (pintype "unspecified"))
      (node (ref "U6") (pin "4") (pinfunction "DGND_4") (pintype "unspecified"))
      (node (ref "U7") (pin "1") (pinfunction "GND_1") (pintype "unspecified"))
      (node (ref "U8") (pin "1") (pinfunction "VSS_1") (pintype "unspecified"))
      (node (ref "U9") (pin "4") (pinfunction "VSS_4") (pintype "unspecified"))
      (node (ref "X2") (pin "2") (pinfunction "GND_2") (pintype "input"))
      (node (ref "X2") (pin "4") (pinfunction "GND_4") (pintype "input"))
      (node (ref "X3") (pin "2") (pinfunction "GND_2") (pintype "input"))
      (node (ref "X3") (pin "4") (pinfunction "GND_4") (pintype "input"))
      (node (ref "X4") (pin "2") (pinfunction "GND_2") (pintype "input"))
      (node (ref "X4") (pin "4") (pinfunction "GND_4") (pintype "input"))
      (node (ref "X5") (pin "2") (pinfunction "GND_2") (pintype "input"))
      (node (ref "X5") (pin "4") (pinfunction "GND_4") (pintype "input"))
    )
    (net (code "7") (name "AIN1") (class "Default")
      (node (ref "C68") (pin "1") (pinfunction "1_1") (pintype "input"))
      (node (ref "U16") (pin "19") (pinfunction "AIN1_19") (pintype "unspecified"))
    )
    (net (code "8") (name "AVDD") (class "Default")
      (node (ref "C20") (pin "1") (pinfunction "1_1") (pintype "input"))
      (node (ref "C21") (pin "2") (pinfunction "2_2") (pintype "input"))
      (node (ref "C27") (pin "1") (pinfunction "1_1") (pintype "input"))
      (node (ref "C46") (pin "2") (pinfunction "2_2") (pintype "input"))
      (node (ref "C47") (pin "2") (pinfunction "2_2") (pintype "input"))
      (node (ref "C48") (pin "2") (pinfunction "2_2") (pintype "input"))
      (node (ref "C96") (pin "2") (pinfunction "2_2") (pintype "unspecified"))
      (node (ref "CN1") (pin "1") (pinfunction "1_1") (pintype "unspecified"))
      (node (ref "CN10") (pin "1") (pinfunction "1_1") (pintype "unspecified"))
      (node (ref "CN11") (pin "1") (pinfunction "1_1") (pintype "unspecified"))
      (node (ref "CN14") (pin "10") (pinfunction "10_10") (pintype "unspecified"))
      (node (ref "CN16") (pin "1") (pinfunction "1_1") (pintype "unspecified"))
      (node (ref "CN19") (pin "3") (pinfunction "3_3") (pintype "unspecified"))
      (node (ref "CN2") (pin "1") (pinfunction "1_1") (pintype "unspecified"))
      (node (ref "CN20") (pin "1") (pinfunction "1_1") (pintype "unspecified"))
      (node (ref "CN21") (pin "1") (pinfunction "1_1") (pintype "unspecified"))
      (node (ref "CN22") (pin "1") (pinfunction "1_1") (pintype "unspecified"))
      (node (ref "CN24") (pin "1") (pinfunction "1_1") (pintype "unspecified"))
      (node (ref "CN3") (pin "1") (pinfunction "1_1") (pintype "unspecified"))
      (node (ref "CN4") (pin "1") (pinfunction "1_1") (pintype "unspecified"))
      (node (ref "CN5") (pin "1") (pinfunction "1_1") (pintype "unspecified"))
      (node (ref "CN6") (pin "1") (pinfunction "1_1") (pintype "unspecified"))
      (node (ref "CN7") (pin "1") (pinfunction "1_1") (pintype "unspecified"))
      (node (ref "CN8") (pin "1") (pinfunction "1_1") (pintype "unspecified"))
      (node (ref "CN9") (pin "1") (pinfunction "1_1") (pintype "unspecified"))
      (node (ref "R10") (pin "1") (pinfunction "1_1") (pintype "unspecified"))
      (node (ref "R11") (pin "1") (pinfunction "1_1") (pintype "unspecified"))
      (node (ref "R12") (pin "1") (pinfunction "1_1") (pintype "unspecified"))
      (node (ref "R15") (pin "2") (pinfunction "2_2") (pintype "unspecified"))
      (node (ref "R89") (pin "1") (pinfunction "1_1") (pintype "input"))
      (node (ref "R9") (pin "1") (pinfunction "1_1") (pintype "unspecified"))
      (node (ref "R90") (pin "1") (pinfunction "1_1") (pintype "input"))
      (node (ref "U17") (pin "3") (pinfunction "VCC_3") (pintype "bidirectional"))
      (node (ref "U21") (pin "3") (pinfunction "VCC_3") (pintype "bidirectional"))
      (node (ref "U24") (pin "1") (pinfunction "OUT_1") (pintype "unspecified"))
      (node (ref "U27") (pin "1") (pinfunction "1_1") (pintype "unspecified"))
      (node (ref "U5") (pin "18") (pinfunction "AVCC_18") (pintype "unspecified"))
      (node (ref "U5") (pin "4") (pinfunction "VCC_4") (pintype "unspecified"))
      (node (ref "U5") (pin "6") (pinfunction "VCC_6") (pintype "unspecified"))
      (node (ref "U6") (pin "19") (pinfunction "RESET#_19") (pintype "unspecified"))
      (node (ref "U6") (pin "21") (pinfunction "AVDD_21") (pintype "unspecified"))
      (node (ref "U6") (pin "24") (pinfunction "PVDD_24") (pintype "unspecified"))
      (node (ref "U6") (pin "3") (pinfunction "DVDD_3") (pintype "unspecified"))
    )
    (net (code "9") (name "BOOT0") (class "Default")
      (node (ref "R1") (pin "1") (pinfunction "1_1") (pintype "unspecified"))
      (node (ref "U1") (pin "167") (pinfunction "BOOT0_167") (pintype "unspecified"))
    )
    (net (code "10") (name "C1") (class "Default")
      (node (ref "R47") (pin "1") (pinfunction "1_1") (pintype "unspecified"))
      (node (ref "U23") (pin "A5") (pinfunction "CC1_A5") (pintype "unspecified"))
    )
    (net (code "11") (name "C2") (class "Default")
      (node (ref "R48") (pin "1") (pinfunction "1_1") (pintype "unspecified"))
      (node (ref "U23") (pin "B5") (pinfunction "CC2_B5") (pintype "unspecified"))
    )
    (net (code "12") (name "CAM_RST") (class "Default")
      (node (ref "C53") (pin "1") (pinfunction "1_1") (pintype "input"))
      (node (ref "FPC1") (pin "19") (pinfunction "19_19") (pintype "unspecified"))
      (node (ref "R18") (pin "1") (pinfunction "1_1") (pintype "unspecified"))
    )
    (net (code "13") (name "CAN1_RX") (class "Default")
      (node (ref "U1") (pin "143") (pinfunction "PD0_143") (pintype "unspecified"))
      (node (ref "U21") (pin "4") (pinfunction "RXD_4") (pintype "output"))
    )
    (net (code "14") (name "CAN1_SILENT") (class "Default")
      (node (ref "R43") (pin "1") (pinfunction "1_1") (pintype "unspecified"))
      (node (ref "U1") (pin "115") (pinfunction "PG5_115") (pintype "unspecified"))
      (node (ref "U21") (pin "8") (pinfunction "S_8") (pintype "input"))
    )
    (net (code "15") (name "CAN1_TX") (class "Default")
      (node (ref "U1") (pin "144") (pinfunction "PD1_144") (pintype "unspecified"))
      (node (ref "U21") (pin "1") (pinfunction "TXD_1") (pintype "input"))
    )
    (net (code "16") (name "CAN2_RX") (class "Default")
      (node (ref "U1") (pin "85") (pinfunction "PB12_85") (pintype "unspecified"))
      (node (ref "U17") (pin "4") (pinfunction "RXD_4") (pintype "output"))
    )
    (net (code "17") (name "CAN2_SILENT") (class "Default")
      (node (ref "R44") (pin "2") (pinfunction "2_2") (pintype "unspecified"))
      (node (ref "U1") (pin "114") (pinfunction "PG4_114") (pintype "unspecified"))
      (node (ref "U17") (pin "8") (pinfunction "S_8") (pintype "input"))
    )
    (net (code "18") (name "CAN2_TX") (class "Default")
      (node (ref "U1") (pin "86") (pinfunction "PB13_86") (pintype "unspecified"))
      (node (ref "U17") (pin "1") (pinfunction "TXD_1") (pintype "input"))
    )
    (net (code "19") (name "CAN_H_1") (class "Default")
      (node (ref "CN8") (pin "2") (pinfunction "2_2") (pintype "unspecified"))
      (node (ref "D7") (pin "1") (pinfunction "1_1") (pintype "unspecified"))
      (node (ref "R46") (pin "2") (pinfunction "2_2") (pintype "unspecified"))
      (node (ref "U21") (pin "7") (pinfunction "CANH_7") (pintype "bidirectional"))
    )
    (net (code "20") (name "CAN_H_2") (class "Default")
      (node (ref "CN9") (pin "2") (pinfunction "2_2") (pintype "unspecified"))
      (node (ref "D9") (pin "1") (pinfunction "1_1") (pintype "unspecified"))
      (node (ref "R45") (pin "1") (pinfunction "1_1") (pintype "unspecified"))
      (node (ref "U17") (pin "7") (pinfunction "CANH_7") (pintype "bidirectional"))
    )
    (net (code "21") (name "CAN_L_1") (class "Default")
      (node (ref "CN8") (pin "3") (pinfunction "3_3") (pintype "unspecified"))
      (node (ref "D6") (pin "1") (pinfunction "1_1") (pintype "unspecified"))
      (node (ref "R65") (pin "1") (pinfunction "1_1") (pintype "input"))
      (node (ref "U21") (pin "6") (pinfunction "CANL_6") (pintype "bidirectional"))
    )
    (net (code "22") (name "CAN_L_2") (class "Default")
      (node (ref "CN9") (pin "3") (pinfunction "3_3") (pintype "unspecified"))
      (node (ref "D8") (pin "1") (pinfunction "1_1") (pintype "unspecified"))
      (node (ref "R86") (pin "1") (pinfunction "1_1") (pintype "input"))
      (node (ref "U17") (pin "6") (pinfunction "CANL_6") (pintype "bidirectional"))
    )
    (net (code "23") (name "CAP1") (class "Default")
      (node (ref "CN24") (pin "2") (pinfunction "2_2") (pintype "unspecified"))
      (node (ref "D29") (pin "1") (pinfunction "1_1") (pintype "unspecified"))
      (node (ref "U1") (pin "73") (pinfunction "PE11_73") (pintype "unspecified"))
    )
    (net (code "24") (name "CAP2") (class "Default")
      (node (ref "CN24") (pin "3") (pinfunction "3_3") (pintype "unspecified"))
      (node (ref "D30") (pin "1") (pinfunction "1_1") (pintype "unspecified"))
      (node (ref "U1") (pin "69") (pinfunction "PE9_69") (pintype "unspecified"))
    )
    (net (code "25") (name "CAP3") (class "Default")
      (node (ref "CN24") (pin "4") (pinfunction "4_4") (pintype "unspecified"))
      (node (ref "D31") (pin "1") (pinfunction "1_1") (pintype "unspecified"))
      (node (ref "U1") (pin "28") (pinfunction "PF8_28") (pintype "unspecified"))
    )
    (net (code "26") (name "CAP4") (class "Default")
      (node (ref "CN24") (pin "5") (pinfunction "5_5") (pintype "unspecified"))
      (node (ref "D32") (pin "1") (pinfunction "1_1") (pintype "unspecified"))
      (node (ref "U1") (pin "76") (pinfunction "PE14_76") (pintype "unspecified"))
    )
    (net (code "27") (name "CC1") (class "Default")
      (node (ref "R20") (pin "1") (pinfunction "1_1") (pintype "unspecified"))
      (node (ref "U10") (pin "A5") (pinfunction "CC1_A5") (pintype "unspecified"))
    )
    (net (code "28") (name "CC2") (class "Default")
      (node (ref "R19") (pin "1") (pinfunction "1_1") (pintype "unspecified"))
      (node (ref "U10") (pin "B5") (pinfunction "CC2_B5") (pintype "unspecified"))
    )
    (net (code "29") (name "CD_SD") (class "Default")
      (node (ref "CARD2") (pin "9") (pinfunction "CD_9") (pintype "unspecified"))
      (node (ref "D59") (pin "1") (pinfunction "1_1") (pintype "unspecified"))
      (node (ref "R39") (pin "2") (pinfunction "2_2") (pintype "unspecified"))
      (node (ref "U1") (pin "127") (pinfunction "PA8_127") (pintype "unspecified"))
    )
    (net (code "30") (name "CLKIN") (class "Default")
      (node (ref "U6") (pin "5") (pinfunction "CLKIN_5") (pintype "unspecified"))
      (node (ref "X4") (pin "3") (pinfunction "OSC2_3") (pintype "input"))
    )
    (net (code "31") (name "CLK_OSD") (class "Default")
      (node (ref "U5") (pin "17") (pinfunction "PB5(SCK/PCINT5)_17") (pintype "unspecified"))
      (node (ref "U6") (pin "10") (pinfunction "SCLK_10") (pintype "unspecified"))
    )
    (net (code "32") (name "CSI_1.2V") (class "Default")
      (node (ref "C60") (pin "2") (pinfunction "2_2") (pintype "unspecified"))
      (node (ref "FPC1") (pin "15") (pinfunction "15_15") (pintype "unspecified"))
      (node (ref "U8") (pin "2") (pinfunction "VOUT_2") (pintype "unspecified"))
    )
    (net (code "33") (name "CSI_2.8V") (class "Default")
      (node (ref "C54") (pin "2") (pinfunction "2_2") (pintype "input"))
      (node (ref "C55") (pin "1") (pinfunction "1_1") (pintype "unspecified"))
      (node (ref "FPC1") (pin "21") (pinfunction "21_21") (pintype "unspecified"))
      (node (ref "U11") (pin "2") (pinfunction "VOUT_2") (pintype "unspecified"))
    )
    (net (code "34") (name "CSI_D0") (class "Default")
      (node (ref "FPC1") (pin "6") (pinfunction "6_6") (pintype "unspecified"))
      (node (ref "U13") (pin "29") (pinfunction "IO5_29") (pintype "unspecified"))
      (node (ref "U16") (pin "16") (pinfunction "P0_16") (pintype "unspecified"))
    )
    (net (code "35") (name "CSI_D1") (class "Default")
      (node (ref "FPC1") (pin "4") (pinfunction "4_4") (pintype "unspecified"))
      (node (ref "U13") (pin "30") (pinfunction "IO18_30") (pintype "unspecified"))
      (node (ref "U16") (pin "15") (pinfunction "P1_15") (pintype "unspecified"))
    )
    (net (code "36") (name "CSI_D2") (class "Default")
      (node (ref "FPC1") (pin "3") (pinfunction "3_3") (pintype "unspecified"))
      (node (ref "U13") (pin "31") (pinfunction "IO19_31") (pintype "unspecified"))
      (node (ref "U16") (pin "10") (pinfunction "P2_10") (pintype "unspecified"))
    )
    (net (code "37") (name "CSI_D3") (class "Default")
      (node (ref "FPC1") (pin "5") (pinfunction "5_5") (pintype "unspecified"))
      (node (ref "U13") (pin "33") (pinfunction "IO21_33") (pintype "unspecified"))
      (node (ref "U16") (pin "9") (pinfunction "P3_9") (pintype "unspecified"))
    )
    (net (code "38") (name "CSI_D4") (class "Default")
      (node (ref "FPC1") (pin "7") (pinfunction "7_7") (pintype "unspecified"))
      (node (ref "U13") (pin "4") (pinfunction "SENSOR_VP_4") (pintype "unspecified"))
      (node (ref "U16") (pin "8") (pinfunction "P4_8") (pintype "unspecified"))
    )
    (net (code "39") (name "CSI_D5") (class "Default")
      (node (ref "FPC1") (pin "9") (pinfunction "9_9") (pintype "unspecified"))
      (node (ref "U13") (pin "5") (pinfunction "SENSOR_VN_5") (pintype "unspecified"))
      (node (ref "U16") (pin "7") (pinfunction "P5_7") (pintype "unspecified"))
    )
    (net (code "40") (name "CSI_D6") (class "Default")
      (node (ref "FPC1") (pin "11") (pinfunction "11_11") (pintype "unspecified"))
      (node (ref "U13") (pin "6") (pinfunction "IO34_6") (pintype "unspecified"))
      (node (ref "U16") (pin "6") (pinfunction "P6_6") (pintype "unspecified"))
    )
    (net (code "41") (name "CSI_D7") (class "Default")
      (node (ref "FPC1") (pin "13") (pinfunction "13_13") (pintype "unspecified"))
      (node (ref "U13") (pin "7") (pinfunction "IO35_7") (pintype "unspecified"))
      (node (ref "U16") (pin "5") (pinfunction "P7_5") (pintype "unspecified"))
    )
    (net (code "42") (name "CSI_HSYNC") (class "Default")
      (node (ref "FPC1") (pin "16") (pinfunction "16_16") (pintype "unspecified"))
      (node (ref "U13") (pin "37") (pinfunction "IO23_37") (pintype "unspecified"))
      (node (ref "U16") (pin "1") (pinfunction "HS_1") (pintype "unspecified"))
    )
    (net (code "43") (name "CSI_MCLK") (class "Default")
      (node (ref "FPC1") (pin "12") (pinfunction "12_12") (pintype "unspecified"))
      (node (ref "Q3") (pin "3") (pinfunction "3_3") (pintype "input"))
      (node (ref "R25") (pin "2") (pinfunction "2_2") (pintype "unspecified"))
      (node (ref "U13") (pin "25") (pinfunction "IO0_25") (pintype "unspecified"))
    )
    (net (code "44") (name "CSI_PCLK") (class "Default")
      (node (ref "C57") (pin "2") (pinfunction "2_2") (pintype "input"))
      (node (ref "FPC1") (pin "8") (pinfunction "8_8") (pintype "unspecified"))
      (node (ref "U13") (pin "36") (pinfunction "IO22_36") (pintype "unspecified"))
      (node (ref "U16") (pin "11") (pinfunction "LLC_11") (pintype "unspecified"))
    )
    (net (code "45") (name "CSI_VSYNC") (class "Default")
      (node (ref "FPC1") (pin "18") (pinfunction "18_18") (pintype "unspecified"))
      (node (ref "U13") (pin "10") (pinfunction "IO25_10") (pintype "unspecified"))
      (node (ref "U16") (pin "31") (pinfunction "VS/FIELD_31") (pintype "unspecified"))
    )
    (net (code "46") (name "CS_IMU") (class "Default")
      (node (ref "U1") (pin "154") (pinfunction "PG10_154") (pintype "unspecified"))
      (node (ref "U4") (pin "12") (pinfunction "CS_12") (pintype "unspecified"))
    )
    (net (code "47") (name "CS_OSD") (class "Default")
      (node (ref "U5") (pin "10") (pinfunction "(PCINT22/OC0A/AIN0)PD6_10") (pintype "unspecified"))
      (node (ref "U6") (pin "8") (pinfunction "CS#_8") (pintype "unspecified"))
    )
    (net (code "48") (name "CURRENT_SENSE_1") (class "Default")
      (node (ref "CN17") (pin "3") (pinfunction "3_3") (pintype "unspecified"))
      (node (ref "D63") (pin "1") (pinfunction "1_1") (pintype "unspecified"))
      (node (ref "U1") (pin "53") (pinfunction "PC4_53") (pintype "unspecified"))
    )
    (net (code "49") (name "CURRENT_SENSE_2") (class "Default")
      (node (ref "CN15") (pin "3") (pinfunction "3_3") (pintype "unspecified"))
      (node (ref "D61") (pin "1") (pinfunction "1_1") (pintype "unspecified"))
      (node (ref "U1") (pin "60") (pinfunction "PF13_60") (pintype "unspecified"))
    )
    (net (code "50") (name "D+") (class "Default")
      (node (ref "D15") (pin "1") (pinfunction "1_1") (pintype "unspecified"))
      (node (ref "U10") (pin "A6") (pinfunction "DP1_A6") (pintype "unspecified"))
      (node (ref "U10") (pin "B6") (pinfunction "DP2_B6") (pintype "unspecified"))
      (node (ref "U12") (pin "4") (pinfunction "D+_4") (pintype "unspecified"))
    )
    (net (code "51") (name "D-") (class "Default")
      (node (ref "D65") (pin "1") (pinfunction "1_1") (pintype "unspecified"))
      (node (ref "U10") (pin "A7") (pinfunction "DN1_A7") (pintype "unspecified"))
      (node (ref "U10") (pin "B7") (pinfunction "DN2_B7") (pintype "unspecified"))
      (node (ref "U12") (pin "5") (pinfunction "D-_5") (pintype "unspecified"))
    )
    (net (code "52") (name "DEBUG_RX_STM32") (class "Default")
      (node (ref "U1") (pin "42") (pinfunction "PA1_42") (pintype "unspecified"))
      (node (ref "U27") (pin "2") (pinfunction "2_2") (pintype "unspecified"))
    )
    (net (code "53") (name "DEBUG_TX_STM32") (class "Default")
      (node (ref "U1") (pin "41") (pinfunction "PA0_41") (pintype "unspecified"))
      (node (ref "U27") (pin "3") (pinfunction "3_3") (pintype "unspecified"))
    )
    (net (code "54") (name "DTR") (class "Default")
      (node (ref "Q3") (pin "2") (pinfunction "2_2") (pintype "input"))
      (node (ref "R31") (pin "1") (pinfunction "1_1") (pintype "unspecified"))
      (node (ref "U12") (pin "28") (pinfunction "DTR_28") (pintype "unspecified"))
    )
    (net (code "55") (name "ESP32_EN") (class "Default")
      (node (ref "Q4") (pin "3") (pinfunction "3_3") (pintype "input"))
      (node (ref "R26") (pin "2") (pinfunction "2_2") (pintype "unspecified"))
      (node (ref "U13") (pin "3") (pinfunction "EN_3") (pintype "unspecified"))
    )
    (net (code "56") (name "FAULT_5V") (class "Default")
      (node (ref "R41") (pin "2") (pinfunction "2_2") (pintype "unspecified"))
      (node (ref "U1") (pin "110") (pinfunction "PG2_110") (pintype "unspecified"))
      (node (ref "U24") (pin "3") (pinfunction "FAULT#_3") (pintype "unspecified"))
    )
    (net (code "57") (name "HSYNC") (class "Default")
      (node (ref "R12") (pin "2") (pinfunction "2_2") (pintype "unspecified"))
      (node (ref "U5") (pin "25") (pinfunction "PC2(ADC2/PCINT10)_25") (pintype "unspecified"))
      (node (ref "U6") (pin "18") (pinfunction "HSYNC#_18") (pintype "unspecified"))
    )
    (net (code "58") (name "I2C_2_SCL") (class "Default")
      (node (ref "R49") (pin "1") (pinfunction "1_1") (pintype "unspecified"))
      (node (ref "R53") (pin "1") (pinfunction "1_1") (pintype "unspecified"))
      (node (ref "U1") (pin "19") (pinfunction "PF1_19") (pintype "unspecified"))
    )
    (net (code "59") (name "I2C_2_SDA") (class "Default")
      (node (ref "R50") (pin "1") (pinfunction "1_1") (pintype "unspecified"))
      (node (ref "R54") (pin "2") (pinfunction "2_2") (pintype "unspecified"))
      (node (ref "U1") (pin "18") (pinfunction "PF0_18") (pintype "unspecified"))
    )
    (net (code "60") (name "I2C_4_SCL") (class "Default")
      (node (ref "R52") (pin "1") (pinfunction "1_1") (pintype "unspecified"))
      (node (ref "R55") (pin "1") (pinfunction "1_1") (pintype "unspecified"))
      (node (ref "U1") (pin "61") (pinfunction "PF14_61") (pintype "unspecified"))
    )
    (net (code "61") (name "I2C_4_SDA") (class "Default")
      (node (ref "R51") (pin "1") (pinfunction "1_1") (pintype "unspecified"))
      (node (ref "R56") (pin "1") (pinfunction "1_1") (pintype "unspecified"))
      (node (ref "U1") (pin "62") (pinfunction "PF15_62") (pintype "unspecified"))
    )
    (net (code "62") (name "I2C_SCL_COMPASS") (class "Default")
      (node (ref "R2") (pin "1") (pinfunction "1_1") (pintype "unspecified"))
      (node (ref "U1") (pin "168") (pinfunction "PB8_168") (pintype "unspecified"))
      (node (ref "U3") (pin "1") (pinfunction "SCL_1") (pintype "unspecified"))
    )
    (net (code "63") (name "I2C_SDA_COMPASS") (class "Default")
      (node (ref "R3") (pin "1") (pinfunction "1_1") (pintype "unspecified"))
      (node (ref "U1") (pin "169") (pinfunction "PB9_169") (pintype "unspecified"))
      (node (ref "U3") (pin "16") (pinfunction "SDA_16") (pintype "unspecified"))
    )
    (net (code "64") (name "INTRQ_ADV7180") (class "Default")
      (node (ref "U13") (pin "8") (pinfunction "IO32_8") (pintype "unspecified"))
      (node (ref "U16") (pin "32") (pinfunction "INTRQ#_32") (pintype "unspecified"))
    )
    (net (code "65") (name "IO1") (class "Default")
      (node (ref "CN5") (pin "2") (pinfunction "2_2") (pintype "unspecified"))
      (node (ref "D28") (pin "1") (pinfunction "1_1") (pintype "unspecified"))
      (node (ref "U1") (pin "116") (pinfunction "PG6_116") (pintype "unspecified"))
    )
    (net (code "66") (name "IO1_AUX") (class "Default")
      (node (ref "CN14") (pin "6") (pinfunction "6_6") (pintype "unspecified"))
      (node (ref "D35") (pin "1") (pinfunction "1_1") (pintype "unspecified"))
      (node (ref "U5") (pin "11") (pinfunction "(PCINT23/AIN1)PD7_11") (pintype "unspecified"))
    )
    (net (code "67") (name "IO2") (class "Default")
      (node (ref "CN5") (pin "3") (pinfunction "3_3") (pintype "unspecified"))
      (node (ref "D27") (pin "1") (pinfunction "1_1") (pintype "unspecified"))
      (node (ref "U1") (pin "122") (pinfunction "PC6_122") (pintype "unspecified"))
    )
    (net (code "68") (name "IO2_AUX") (class "Default")
      (node (ref "CN14") (pin "7") (pinfunction "7_7") (pintype "unspecified"))
      (node (ref "D36") (pin "1") (pinfunction "1_1") (pintype "unspecified"))
      (node (ref "U5") (pin "24") (pinfunction "PC1(ADC1/PCINT9)_24") (pintype "unspecified"))
    )
    (net (code "69") (name "IO3") (class "Default")
      (node (ref "CN5") (pin "4") (pinfunction "4_4") (pintype "unspecified"))
      (node (ref "D26") (pin "1") (pinfunction "1_1") (pintype "unspecified"))
      (node (ref "U1") (pin "49") (pinfunction "PA4_49") (pintype "unspecified"))
    )
    (net (code "70") (name "IO3_AUX") (class "Default")
      (node (ref "CN14") (pin "8") (pinfunction "8_8") (pintype "unspecified"))
      (node (ref "D37") (pin "1") (pinfunction "1_1") (pintype "unspecified"))
      (node (ref "U5") (pin "28") (pinfunction "PC5(ADC5/SCL/PCINT13)_28") (pintype "unspecified"))
    )
    (net (code "71") (name "IO4") (class "Default")
      (node (ref "CN5") (pin "5") (pinfunction "5_5") (pintype "unspecified"))
      (node (ref "D25") (pin "1") (pinfunction "1_1") (pintype "unspecified"))
      (node (ref "U1") (pin "21") (pinfunction "PF3_21") (pintype "unspecified"))
    )
    (net (code "72") (name "IO4_AUX") (class "Default")
      (node (ref "CN14") (pin "9") (pinfunction "9_9") (pintype "unspecified"))
      (node (ref "D38") (pin "1") (pinfunction "1_1") (pintype "unspecified"))
      (node (ref "U5") (pin "27") (pinfunction "PC4(ADC4/SDA/PCINT12)_27") (pintype "unspecified"))
    )
    (net (code "73") (name "IO16") (class "Default")
      (node (ref "R21") (pin "1") (pinfunction "1_1") (pintype "unspecified"))
      (node (ref "U13") (pin "27") (pinfunction "IO16_27") (pintype "unspecified"))
      (node (ref "U9") (pin "1") (pinfunction "CE#_1") (pintype "unspecified"))
    )
    (net (code "74") (name "JTCK{slash}SWCLK") (class "Default")
      (node (ref "U1") (pin "138") (pinfunction "PA14_138") (pintype "unspecified"))
      (node (ref "U27") (pin "5") (pinfunction "5_5") (pintype "unspecified"))
    )
    (net (code "75") (name "JTDI") (class "Default")
      (node (ref "U1") (pin "139") (pinfunction "PA15_139") (pintype "unspecified"))
      (node (ref "U27") (pin "6") (pinfunction "6_6") (pintype "unspecified"))
    )
    (net (code "76") (name "JTDO") (class "Default")
      (node (ref "U1") (pin "162") (pinfunction "PB3_162") (pintype "unspecified"))
      (node (ref "U27") (pin "7") (pinfunction "7_7") (pintype "unspecified"))
    )
    (net (code "77") (name "JTMS{slash}SWDIO") (class "Default")
      (node (ref "U1") (pin "132") (pinfunction "PA13_132") (pintype "unspecified"))
      (node (ref "U27") (pin "4") (pinfunction "4_4") (pintype "unspecified"))
    )
    (net (code "78") (name "LOS") (class "Default")
      (node (ref "R10") (pin "2") (pinfunction "2_2") (pintype "unspecified"))
      (node (ref "U5") (pin "12") (pinfunction "(PCINT0/CLKO/ICP1)PB0_12") (pintype "unspecified"))
      (node (ref "U6") (pin "12") (pinfunction "LOS_12") (pintype "unspecified"))
    )
    (net (code "79") (name "MISO_OSD") (class "Default")
      (node (ref "U5") (pin "16") (pinfunction "(PCINT4/MISO)PB4_16") (pintype "unspecified"))
      (node (ref "U6") (pin "11") (pinfunction "SDOUT_11") (pintype "unspecified"))
    )
    (net (code "80") (name "MOSI_OSD") (class "Default")
      (node (ref "U5") (pin "15") (pinfunction "(PCINT3/OC2A/MOSI)PB3_15") (pintype "unspecified"))
      (node (ref "U6") (pin "9") (pinfunction "SDIN_9") (pintype "unspecified"))
    )
    (net (code "81") (name "NJTRST") (class "Default")
      (node (ref "U1") (pin "163") (pinfunction "PB4_163") (pintype "unspecified"))
      (node (ref "U27") (pin "8") (pinfunction "8_8") (pintype "unspecified"))
    )
    (net (code "82") (name "NRST") (class "Default")
      (node (ref "C33") (pin "2") (pinfunction "2_2") (pintype "input"))
      (node (ref "SW1") (pin "1") (pinfunction "1_1") (pintype "unspecified"))
      (node (ref "SW1") (pin "3") (pinfunction "3_3") (pintype "unspecified"))
      (node (ref "U1") (pin "33") (pinfunction "NRST_33") (pintype "unspecified"))
      (node (ref "U27") (pin "9") (pinfunction "9_9") (pintype "unspecified"))
    )
    (net (code "83") (name "Net-(C45-Pad2)") (class "Default")
      (node (ref "C45") (pin "2") (pinfunction "2_2") (pintype "input"))
      (node (ref "CN20") (pin "4") (pinfunction "4_4") (pintype "unspecified"))
    )
    (net (code "84") (name "Net-(C49-Pad2)") (class "Default")
      (node (ref "C49") (pin "2") (pinfunction "2_2") (pintype "unspecified"))
      (node (ref "C50") (pin "2") (pinfunction "2_2") (pintype "unspecified"))
      (node (ref "R13") (pin "1") (pinfunction "1_1") (pintype "unspecified"))
    )
    (net (code "85") (name "Net-(C66-Pad2)") (class "Default")
      (node (ref "C66") (pin "2") (pinfunction "2_2") (pintype "unspecified"))
      (node (ref "R23") (pin "1") (pinfunction "1_1") (pintype "unspecified"))
    )
    (net (code "86") (name "Net-(C68-Pad2)") (class "Default")
      (node (ref "C68") (pin "2") (pinfunction "2_2") (pintype "input"))
      (node (ref "R34") (pin "1") (pinfunction "1_1") (pintype "unspecified"))
      (node (ref "R35") (pin "2") (pinfunction "2_2") (pintype "unspecified"))
    )
    (net (code "87") (name "Net-(CN3-Pad2)") (class "Default")
      (node (ref "CN3") (pin "2") (pinfunction "2_2") (pintype "unspecified"))
      (node (ref "D17") (pin "1") (pinfunction "1_1") (pintype "unspecified"))
      (node (ref "R78") (pin "2") (pinfunction "2_2") (pintype "unspecified"))
    )
    (net (code "88") (name "Net-(CN3-Pad3)") (class "Default")
      (node (ref "CN3") (pin "3") (pinfunction "3_3") (pintype "unspecified"))
      (node (ref "D17") (pin "5") (pinfunction "5_5") (pintype "unspecified"))
      (node (ref "R79") (pin "2") (pinfunction "2_2") (pintype "unspecified"))
    )
    (net (code "89") (name "Net-(CN3-Pad4)") (class "Default")
      (node (ref "CN3") (pin "4") (pinfunction "4_4") (pintype "unspecified"))
      (node (ref "D17") (pin "4") (pinfunction "4_4") (pintype "unspecified"))
      (node (ref "R80") (pin "2") (pinfunction "2_2") (pintype "unspecified"))
    )
    (net (code "90") (name "Net-(CN3-Pad5)") (class "Default")
      (node (ref "CN3") (pin "5") (pinfunction "5_5") (pintype "unspecified"))
      (node (ref "D17") (pin "3") (pinfunction "3_3") (pintype "unspecified"))
      (node (ref "R81") (pin "2") (pinfunction "2_2") (pintype "unspecified"))
    )
    (net (code "91") (name "Net-(CN4-Pad2)") (class "Default")
      (node (ref "CN4") (pin "2") (pinfunction "2_2") (pintype "unspecified"))
      (node (ref "D16") (pin "1") (pinfunction "1_1") (pintype "unspecified"))
      (node (ref "R74") (pin "2") (pinfunction "2_2") (pintype "unspecified"))
    )
    (net (code "92") (name "Net-(CN4-Pad3)") (class "Default")
      (node (ref "CN4") (pin "3") (pinfunction "3_3") (pintype "unspecified"))
      (node (ref "D16") (pin "5") (pinfunction "5_5") (pintype "unspecified"))
      (node (ref "R75") (pin "2") (pinfunction "2_2") (pintype "unspecified"))
    )
    (net (code "93") (name "Net-(CN4-Pad4)") (class "Default")
      (node (ref "CN4") (pin "4") (pinfunction "4_4") (pintype "unspecified"))
      (node (ref "D16") (pin "4") (pinfunction "4_4") (pintype "unspecified"))
      (node (ref "R76") (pin "2") (pinfunction "2_2") (pintype "unspecified"))
    )
    (net (code "94") (name "Net-(CN4-Pad5)") (class "Default")
      (node (ref "CN4") (pin "5") (pinfunction "5_5") (pintype "unspecified"))
      (node (ref "D16") (pin "3") (pinfunction "3_3") (pintype "unspecified"))
      (node (ref "R77") (pin "2") (pinfunction "2_2") (pintype "unspecified"))
    )
    (net (code "95") (name "Net-(CN6-Pad2)") (class "Default")
      (node (ref "CN6") (pin "2") (pinfunction "2_2") (pintype "unspecified"))
      (node (ref "D20") (pin "1") (pinfunction "1_1") (pintype "unspecified"))
      (node (ref "R84") (pin "2") (pinfunction "2_2") (pintype "unspecified"))
    )
    (net (code "96") (name "Net-(CN6-Pad3)") (class "Default")
      (node (ref "CN6") (pin "3") (pinfunction "3_3") (pintype "unspecified"))
      (node (ref "D21") (pin "1") (pinfunction "1_1") (pintype "unspecified"))
      (node (ref "R85") (pin "2") (pinfunction "2_2") (pintype "unspecified"))
    )
    (net (code "97") (name "Net-(CN7-Pad2)") (class "Default")
      (node (ref "CN7") (pin "2") (pinfunction "2_2") (pintype "unspecified"))
      (node (ref "D19") (pin "1") (pinfunction "1_1") (pintype "unspecified"))
      (node (ref "R82") (pin "2") (pinfunction "2_2") (pintype "unspecified"))
    )
    (net (code "98") (name "Net-(CN7-Pad3)") (class "Default")
      (node (ref "CN7") (pin "3") (pinfunction "3_3") (pintype "unspecified"))
      (node (ref "D18") (pin "1") (pinfunction "1_1") (pintype "unspecified"))
      (node (ref "R83") (pin "2") (pinfunction "2_2") (pintype "unspecified"))
    )
    (net (code "99") (name "Net-(CN10-Pad2)") (class "Default")
      (node (ref "CN10") (pin "2") (pinfunction "2_2") (pintype "unspecified"))
      (node (ref "D11") (pin "1") (pinfunction "1_1") (pintype "unspecified"))
      (node (ref "R53") (pin "2") (pinfunction "2_2") (pintype "unspecified"))
    )
    (net (code "100") (name "Net-(CN10-Pad3)") (class "Default")
      (node (ref "CN10") (pin "3") (pinfunction "3_3") (pintype "unspecified"))
      (node (ref "D10") (pin "1") (pinfunction "1_1") (pintype "unspecified"))
      (node (ref "R54") (pin "1") (pinfunction "1_1") (pintype "unspecified"))
    )
    (net (code "101") (name "Net-(CN11-Pad2)") (class "Default")
      (node (ref "CN11") (pin "2") (pinfunction "2_2") (pintype "unspecified"))
      (node (ref "D13") (pin "1") (pinfunction "1_1") (pintype "unspecified"))
      (node (ref "R55") (pin "2") (pinfunction "2_2") (pintype "unspecified"))
    )
    (net (code "102") (name "Net-(CN11-Pad3)") (class "Default")
      (node (ref "CN11") (pin "3") (pinfunction "3_3") (pintype "unspecified"))
      (node (ref "D12") (pin "1") (pinfunction "1_1") (pintype "unspecified"))
      (node (ref "R56") (pin "2") (pinfunction "2_2") (pintype "unspecified"))
    )
    (net (code "103") (name "Net-(CN14-Pad2)") (class "Default")
      (node (ref "CN14") (pin "2") (pinfunction "2_2") (pintype "unspecified"))
      (node (ref "D39") (pin "1") (pinfunction "1_1") (pintype "unspecified"))
      (node (ref "R57") (pin "2") (pinfunction "2_2") (pintype "unspecified"))
    )
    (net (code "104") (name "Net-(CN14-Pad3)") (class "Default")
      (node (ref "CN14") (pin "3") (pinfunction "3_3") (pintype "unspecified"))
      (node (ref "D40") (pin "1") (pinfunction "1_1") (pintype "unspecified"))
      (node (ref "R59") (pin "2") (pinfunction "2_2") (pintype "unspecified"))
    )
    (net (code "105") (name "Net-(CN14-Pad4)") (class "Default")
      (node (ref "CN14") (pin "4") (pinfunction "4_4") (pintype "unspecified"))
      (node (ref "D41") (pin "1") (pinfunction "1_1") (pintype "unspecified"))
      (node (ref "R60") (pin "2") (pinfunction "2_2") (pintype "unspecified"))
    )
    (net (code "106") (name "Net-(CN14-Pad5)") (class "Default")
      (node (ref "CN14") (pin "5") (pinfunction "5_5") (pintype "unspecified"))
      (node (ref "D42") (pin "1") (pinfunction "1_1") (pintype "unspecified"))
      (node (ref "R61") (pin "2") (pinfunction "2_2") (pintype "unspecified"))
    )
    (net (code "107") (name "Net-(CN16-Pad2)") (class "Default")
      (node (ref "CN16") (pin "2") (pinfunction "2_2") (pintype "unspecified"))
      (node (ref "D43") (pin "1") (pinfunction "1_1") (pintype "unspecified"))
      (node (ref "R66") (pin "2") (pinfunction "2_2") (pintype "unspecified"))
    )
    (net (code "108") (name "Net-(CN16-Pad3)") (class "Default")
      (node (ref "CN16") (pin "3") (pinfunction "3_3") (pintype "unspecified"))
      (node (ref "D44") (pin "1") (pinfunction "1_1") (pintype "unspecified"))
      (node (ref "R67") (pin "2") (pinfunction "2_2") (pintype "unspecified"))
    )
    (net (code "109") (name "Net-(CN16-Pad4)") (class "Default")
      (node (ref "CN16") (pin "4") (pinfunction "4_4") (pintype "unspecified"))
      (node (ref "D45") (pin "1") (pinfunction "1_1") (pintype "unspecified"))
      (node (ref "R68") (pin "2") (pinfunction "2_2") (pintype "unspecified"))
    )
    (net (code "110") (name "Net-(CN16-Pad5)") (class "Default")
      (node (ref "CN16") (pin "5") (pinfunction "5_5") (pintype "unspecified"))
      (node (ref "D46") (pin "1") (pinfunction "1_1") (pintype "unspecified"))
      (node (ref "R69") (pin "2") (pinfunction "2_2") (pintype "unspecified"))
    )
    (net (code "111") (name "Net-(CN16-Pad6)") (class "Default")
      (node (ref "CN16") (pin "6") (pinfunction "6_6") (pintype "unspecified"))
      (node (ref "D47") (pin "1") (pinfunction "1_1") (pintype "unspecified"))
      (node (ref "R70") (pin "2") (pinfunction "2_2") (pintype "unspecified"))
    )
    (net (code "112") (name "Net-(CN16-Pad7)") (class "Default")
      (node (ref "CN16") (pin "7") (pinfunction "7_7") (pintype "unspecified"))
      (node (ref "D48") (pin "1") (pinfunction "1_1") (pintype "unspecified"))
      (node (ref "R71") (pin "2") (pinfunction "2_2") (pintype "unspecified"))
    )
    (net (code "113") (name "Net-(CN16-Pad8)") (class "Default")
      (node (ref "CN16") (pin "8") (pinfunction "8_8") (pintype "unspecified"))
      (node (ref "D49") (pin "1") (pinfunction "1_1") (pintype "unspecified"))
      (node (ref "R72") (pin "2") (pinfunction "2_2") (pintype "unspecified"))
    )
    (net (code "114") (name "Net-(CN16-Pad9)") (class "Default")
      (node (ref "CN16") (pin "9") (pinfunction "9_9") (pintype "unspecified"))
      (node (ref "D50") (pin "1") (pinfunction "1_1") (pintype "unspecified"))
      (node (ref "R73") (pin "2") (pinfunction "2_2") (pintype "unspecified"))
    )
    (net (code "115") (name "Net-(CN18-Pad3)") (class "Default")
      (node (ref "CN18") (pin "3") (pinfunction "3_3") (pintype "unspecified"))
      (node (ref "R90") (pin "2") (pinfunction "2_2") (pintype "input"))
      (node (ref "R91") (pin "2") (pinfunction "2_2") (pintype "input"))
    )
    (net (code "116") (name "Net-(FPC1-Pad17)") (class "Default")
      (node (ref "FPC1") (pin "17") (pinfunction "17_17") (pintype "unspecified"))
      (node (ref "R24") (pin "1") (pinfunction "1_1") (pintype "unspecified"))
    )
    (net (code "117") (name "Net-(LED1-+)") (class "Default")
      (node (ref "LED1") (pin "1") (pinfunction "+_1") (pintype "unspecified"))
      (node (ref "R58") (pin "1") (pinfunction "1_1") (pintype "unspecified"))
    )
    (net (code "118") (name "Net-(Q3-Pad1)") (class "Default")
      (node (ref "Q3") (pin "1") (pinfunction "1_1") (pintype "input"))
      (node (ref "R30") (pin "2") (pinfunction "2_2") (pintype "unspecified"))
    )
    (net (code "119") (name "Net-(Q4-Pad1)") (class "Default")
      (node (ref "Q4") (pin "1") (pinfunction "1_1") (pintype "input"))
      (node (ref "R31") (pin "2") (pinfunction "2_2") (pintype "unspecified"))
    )
    (net (code "120") (name "Net-(R1-Pad2)") (class "Default")
      (node (ref "R1") (pin "2") (pinfunction "2_2") (pintype "unspecified"))
      (node (ref "SW2") (pin "2") (pinfunction "2_2") (pintype "unspecified"))
    )
    (net (code "121") (name "Net-(R45-Pad2)") (class "Default")
      (node (ref "R45") (pin "2") (pinfunction "2_2") (pintype "unspecified"))
      (node (ref "R86") (pin "2") (pinfunction "2_2") (pintype "input"))
    )
    (net (code "122") (name "Net-(R46-Pad1)") (class "Default")
      (node (ref "R46") (pin "1") (pinfunction "1_1") (pintype "unspecified"))
      (node (ref "R65") (pin "2") (pinfunction "2_2") (pintype "input"))
    )
    (net (code "123") (name "Net-(U1-PA9)") (class "Default")
      (node (ref "R63") (pin "2") (pinfunction "2_2") (pintype "unspecified"))
      (node (ref "R64") (pin "1") (pinfunction "1_1") (pintype "unspecified"))
      (node (ref "U1") (pin "128") (pinfunction "PA9_128") (pintype "unspecified"))
    )
    (net (code "124") (name "Net-(U1-VREF+)") (class "Default")
      (node (ref "R40") (pin "2") (pinfunction "2_2") (pintype "unspecified"))
      (node (ref "U1") (pin "39") (pinfunction "VREF+_39") (pintype "unspecified"))
    )
    (net (code "125") (name "Net-(U3-C1)") (class "Default")
      (node (ref "C34") (pin "2") (pinfunction "2_2") (pintype "input"))
      (node (ref "U3") (pin "10") (pinfunction "C1_10") (pintype "unspecified"))
    )
    (net (code "126") (name "Net-(U3-SETC)") (class "Default")
      (node (ref "C35") (pin "1") (pinfunction "1_1") (pintype "unspecified"))
      (node (ref "U3") (pin "12") (pinfunction "SETC_12") (pintype "unspecified"))
    )
    (net (code "127") (name "Net-(U3-SETP)") (class "Default")
      (node (ref "C35") (pin "2") (pinfunction "2_2") (pintype "unspecified"))
      (node (ref "U3") (pin "8") (pinfunction "SETP_8") (pintype "unspecified"))
    )
    (net (code "128") (name "Net-(U5-(PCINT6{slash}XTAL1{slash}TOSC1)PB6)") (class "Default")
      (node (ref "C44") (pin "2") (pinfunction "2_2") (pintype "unspecified"))
      (node (ref "U5") (pin "7") (pinfunction "(PCINT6/XTAL1/TOSC1)PB6_7") (pintype "unspecified"))
      (node (ref "X3") (pin "3") (pinfunction "OSC2_3") (pintype "input"))
    )
    (net (code "129") (name "Net-(U5-(PCINT7{slash}XTAL2{slash}TOSC2)PB7)") (class "Default")
      (node (ref "C43") (pin "2") (pinfunction "2_2") (pintype "unspecified"))
      (node (ref "U5") (pin "8") (pinfunction "(PCINT7/XTAL2/TOSC2)PB7_8") (pintype "unspecified"))
      (node (ref "X3") (pin "1") (pinfunction "OSC1_1") (pintype "input"))
    )
    (net (code "130") (name "Net-(U6-SAG)") (class "Default")
      (node (ref "C50") (pin "1") (pinfunction "1_1") (pintype "unspecified"))
      (node (ref "U6") (pin "25") (pinfunction "SAG_25") (pintype "unspecified"))
    )
    (net (code "131") (name "Net-(U6-VIN)") (class "Default")
      (node (ref "C51") (pin "1") (pinfunction "1_1") (pintype "input"))
      (node (ref "U6") (pin "22") (pinfunction "VIN_22") (pintype "unspecified"))
    )
    (net (code "132") (name "Net-(U6-VOUT)") (class "Default")
      (node (ref "C49") (pin "1") (pinfunction "1_1") (pintype "unspecified"))
      (node (ref "U6") (pin "26") (pinfunction "VOUT_26") (pintype "unspecified"))
    )
    (net (code "133") (name "Net-(U7-EN)") (class "Default")
      (node (ref "C85") (pin "1") (pinfunction "1_1") (pintype "unspecified"))
      (node (ref "R15") (pin "1") (pinfunction "1_1") (pintype "unspecified"))
      (node (ref "U7") (pin "7") (pinfunction "VREF2_7") (pintype "unspecified"))
      (node (ref "U7") (pin "8") (pinfunction "EN_8") (pintype "unspecified"))
    )
    (net (code "134") (name "Net-(U12-REGIN)") (class "Default")
      (node (ref "R42") (pin "2") (pinfunction "2_2") (pintype "input"))
      (node (ref "R62") (pin "2") (pinfunction "2_2") (pintype "input"))
      (node (ref "U12") (pin "7") (pinfunction "REGIN_7") (pintype "unspecified"))
    )
    (net (code "135") (name "Net-(U12-RST#)") (class "Default")
      (node (ref "R27") (pin "1") (pinfunction "1_1") (pintype "unspecified"))
      (node (ref "U12") (pin "9") (pinfunction "RST#_9") (pintype "unspecified"))
    )
    (net (code "136") (name "Net-(U12-RXD)") (class "Default")
      (node (ref "R29") (pin "2") (pinfunction "2_2") (pintype "unspecified"))
      (node (ref "U12") (pin "25") (pinfunction "RXD_25") (pintype "unspecified"))
    )
    (net (code "137") (name "Net-(U12-TXD)") (class "Default")
      (node (ref "R28") (pin "2") (pinfunction "2_2") (pintype "unspecified"))
      (node (ref "U12") (pin "26") (pinfunction "TXD_26") (pintype "unspecified"))
    )
    (net (code "138") (name "Net-(U16-ALSB)") (class "Default")
      (node (ref "R32") (pin "2") (pinfunction "2_2") (pintype "unspecified"))
      (node (ref "R33") (pin "2") (pinfunction "2_2") (pintype "input"))
      (node (ref "U16") (pin "26") (pinfunction "ALSB_26") (pintype "unspecified"))
    )
    (net (code "139") (name "Net-(U16-ELPF)") (class "Default")
      (node (ref "C69") (pin "2") (pinfunction "2_2") (pintype "unspecified"))
      (node (ref "R23") (pin "2") (pinfunction "2_2") (pintype "unspecified"))
      (node (ref "U16") (pin "17") (pinfunction "ELPF_17") (pintype "unspecified"))
    )
    (net (code "140") (name "Net-(U16-VREFN)") (class "Default")
      (node (ref "C65") (pin "2") (pinfunction "2_2") (pintype "input"))
      (node (ref "U16") (pin "21") (pinfunction "VREFN_21") (pintype "unspecified"))
    )
    (net (code "141") (name "Net-(U16-VREFP)") (class "Default")
      (node (ref "C65") (pin "1") (pinfunction "1_1") (pintype "input"))
      (node (ref "U16") (pin "20") (pinfunction "VREFP_20") (pintype "unspecified"))
    )
    (net (code "142") (name "Net-(U19-ON{slash}OFF#)") (class "Default")
      (node (ref "R37") (pin "1") (pinfunction "1_1") (pintype "unspecified"))
      (node (ref "U19") (pin "2") (pinfunction "ON/OFF#_2") (pintype "unspecified"))
    )
    (net (code "143") (name "Net-(U20-ON{slash}OFF#)") (class "Default")
      (node (ref "R38") (pin "1") (pinfunction "1_1") (pintype "unspecified"))
      (node (ref "U20") (pin "2") (pinfunction "ON/OFF#_2") (pintype "unspecified"))
    )
    (net (code "144") (name "Net-(U24-EN)") (class "Default")
      (node (ref "R92") (pin "2") (pinfunction "2_2") (pintype "unspecified"))
      (node (ref "U24") (pin "4") (pinfunction "EN_4") (pintype "unspecified"))
    )
    (net (code "145") (name "Net-(U24-ILIM)") (class "Default")
      (node (ref "R93") (pin "2") (pinfunction "2_2") (pintype "unspecified"))
      (node (ref "U24") (pin "2") (pinfunction "ILIM_2") (pintype "unspecified"))
    )
    (net (code "146") (name "Net-(U26-VCCB)") (class "Default")
      (node (ref "C91") (pin "2") (pinfunction "2_2") (pintype "input"))
      (node (ref "R88") (pin "1") (pinfunction "1_1") (pintype "input"))
      (node (ref "R89") (pin "2") (pinfunction "2_2") (pintype "input"))
      (node (ref "U26") (pin "19") (pinfunction "VCCB_19") (pintype "unspecified"))
    )
    (net (code "147") (name "PC14-OSC32_IN") (class "Default")
      (node (ref "C29") (pin "2") (pinfunction "2_2") (pintype "input"))
      (node (ref "U1") (pin "10") (pinfunction "PC14-OSC32_IN_10") (pintype "unspecified"))
      (node (ref "X1") (pin "2") (pinfunction "OSC2_2") (pintype "input"))
    )
    (net (code "148") (name "PC15-OSC32_OUT") (class "Default")
      (node (ref "C30") (pin "2") (pinfunction "2_2") (pintype "input"))
      (node (ref "U1") (pin "11") (pinfunction "PC15-OSC32_OUT_11") (pintype "unspecified"))
      (node (ref "X1") (pin "1") (pinfunction "OSC1_1") (pintype "input"))
    )
    (net (code "149") (name "PH0-OSC_IN") (class "Default")
      (node (ref "C31") (pin "2") (pinfunction "2_2") (pintype "unspecified"))
      (node (ref "U1") (pin "31") (pinfunction "PH0-OSC_IN_31") (pintype "unspecified"))
      (node (ref "X2") (pin "1") (pinfunction "1_1") (pintype "input"))
    )
    (net (code "150") (name "PH1-OSC_OUT") (class "Default")
      (node (ref "C32") (pin "2") (pinfunction "2_2") (pintype "unspecified"))
      (node (ref "U1") (pin "32") (pinfunction "PH1-OSC_OUT_32") (pintype "unspecified"))
      (node (ref "X2") (pin "3") (pinfunction "3_3") (pintype "input"))
    )
    (net (code "151") (name "POWER_BRICK1_5V") (class "Default")
      (node (ref "CN17") (pin "1") (pinfunction "1_1") (pintype "unspecified"))
      (node (ref "CN17") (pin "2") (pinfunction "2_2") (pintype "unspecified"))
      (node (ref "D1") (pin "2") (pinfunction "A_2") (pintype "unspecified"))
    )
    (net (code "152") (name "POWER_BRICK2_5V") (class "Default")
      (node (ref "CN15") (pin "1") (pinfunction "1_1") (pintype "unspecified"))
      (node (ref "CN15") (pin "2") (pinfunction "2_2") (pintype "unspecified"))
      (node (ref "D14") (pin "2") (pinfunction "A_2") (pintype "unspecified"))
      (node (ref "R91") (pin "1") (pinfunction "1_1") (pintype "input"))
    )
    (net (code "153") (name "PPM") (class "Default")
      (node (ref "CN21") (pin "2") (pinfunction "2_2") (pintype "unspecified"))
      (node (ref "D24") (pin "1") (pinfunction "1_1") (pintype "unspecified"))
      (node (ref "U1") (pin "75") (pinfunction "PE13_75") (pintype "unspecified"))
    )
    (net (code "154") (name "PSRAM_CLK") (class "Default")
      (node (ref "U13") (pin "28") (pinfunction "IO17_28") (pintype "unspecified"))
      (node (ref "U9") (pin "6") (pinfunction "SCLK_6") (pintype "unspecified"))
    )
    (net (code "155") (name "PWM1") (class "Default")
      (node (ref "U1") (pin "50") (pinfunction "PA5_50") (pintype "unspecified"))
      (node (ref "U26") (pin "9") (pinfunction "A8_9") (pintype "unspecified"))
    )
    (net (code "156") (name "PWM2") (class "Default")
      (node (ref "U1") (pin "52") (pinfunction "PA7_52") (pintype "unspecified"))
      (node (ref "U26") (pin "8") (pinfunction "A7_8") (pintype "unspecified"))
    )
    (net (code "157") (name "PWM3") (class "Default")
      (node (ref "U1") (pin "96") (pinfunction "PD13_96") (pintype "unspecified"))
      (node (ref "U26") (pin "7") (pinfunction "A6_7") (pintype "unspecified"))
    )
    (net (code "158") (name "PWM4") (class "Default")
      (node (ref "U1") (pin "46") (pinfunction "PA3_46") (pintype "unspecified"))
      (node (ref "U26") (pin "6") (pinfunction "A5_6") (pintype "unspecified"))
    )
    (net (code "159") (name "PWM5") (class "Default")
      (node (ref "U1") (pin "43") (pinfunction "PA2_43") (pintype "unspecified"))
      (node (ref "U26") (pin "5") (pinfunction "A4_5") (pintype "unspecified"))
    )
    (net (code "160") (name "PWM6") (class "Default")
      (node (ref "U1") (pin "55") (pinfunction "PB0_55") (pintype "unspecified"))
      (node (ref "U26") (pin "4") (pinfunction "A3_4") (pintype "unspecified"))
    )
    (net (code "161") (name "PWM7") (class "Default")
      (node (ref "U1") (pin "97") (pinfunction "PD14_97") (pintype "unspecified"))
      (node (ref "U26") (pin "3") (pinfunction "A2_3") (pintype "unspecified"))
    )
    (net (code "162") (name "PWM8") (class "Default")
      (node (ref "U1") (pin "56") (pinfunction "PB1_56") (pintype "unspecified"))
      (node (ref "U26") (pin "1") (pinfunction "A1_1") (pintype "unspecified"))
    )
    (net (code "163") (name "PWM_1_AUX") (class "Default")
      (node (ref "R57") (pin "1") (pinfunction "1_1") (pintype "unspecified"))
      (node (ref "U5") (pin "1") (pinfunction "(PCINT19/OC2B/INT1)PD3_1") (pintype "unspecified"))
    )
    (net (code "164") (name "PWM_1_FMU") (class "Default")
      (node (ref "R66") (pin "1") (pinfunction "1_1") (pintype "unspecified"))
      (node (ref "U26") (pin "12") (pinfunction "B8_12") (pintype "unspecified"))
    )
    (net (code "165") (name "PWM_2_AUX") (class "Default")
      (node (ref "R59") (pin "1") (pinfunction "1_1") (pintype "unspecified"))
      (node (ref "U5") (pin "9") (pinfunction "(PCINT21/OC0B/T1)PD5_9") (pintype "unspecified"))
    )
    (net (code "166") (name "PWM_2_FMU") (class "Default")
      (node (ref "R67") (pin "1") (pinfunction "1_1") (pintype "unspecified"))
      (node (ref "U26") (pin "13") (pinfunction "B7_13") (pintype "unspecified"))
    )
    (net (code "167") (name "PWM_3_AUX") (class "Default")
      (node (ref "R60") (pin "1") (pinfunction "1_1") (pintype "unspecified"))
      (node (ref "U5") (pin "14") (pinfunction "(PCINT2/SS#/OC1B)PB2_14") (pintype "unspecified"))
    )
    (net (code "168") (name "PWM_3_FMU") (class "Default")
      (node (ref "R68") (pin "1") (pinfunction "1_1") (pintype "unspecified"))
      (node (ref "U26") (pin "14") (pinfunction "B6_14") (pintype "unspecified"))
    )
    (net (code "169") (name "PWM_4_AUX") (class "Default")
      (node (ref "R61") (pin "1") (pinfunction "1_1") (pintype "unspecified"))
      (node (ref "U5") (pin "13") (pinfunction "(PCINT1/OC1A)PB1_13") (pintype "unspecified"))
    )
    (net (code "170") (name "PWM_4_FMU") (class "Default")
      (node (ref "R69") (pin "1") (pinfunction "1_1") (pintype "unspecified"))
      (node (ref "U26") (pin "15") (pinfunction "B5_15") (pintype "unspecified"))
    )
    (net (code "171") (name "PWM_5_FMU") (class "Default")
      (node (ref "R70") (pin "1") (pinfunction "1_1") (pintype "unspecified"))
      (node (ref "U26") (pin "16") (pinfunction "B4_16") (pintype "unspecified"))
    )
    (net (code "172") (name "PWM_6_FMU") (class "Default")
      (node (ref "R71") (pin "1") (pinfunction "1_1") (pintype "unspecified"))
      (node (ref "U26") (pin "17") (pinfunction "B3_17") (pintype "unspecified"))
    )
    (net (code "173") (name "PWM_7_FMU") (class "Default")
      (node (ref "R72") (pin "1") (pinfunction "1_1") (pintype "unspecified"))
      (node (ref "U26") (pin "18") (pinfunction "B2_18") (pintype "unspecified"))
    )
    (net (code "174") (name "PWM_8_FMU") (class "Default")
      (node (ref "R73") (pin "1") (pinfunction "1_1") (pintype "unspecified"))
      (node (ref "U26") (pin "20") (pinfunction "B1_20") (pintype "unspecified"))
    )
    (net (code "175") (name "RESET#") (class "Default")
      (node (ref "C45") (pin "1") (pinfunction "1_1") (pintype "input"))
      (node (ref "R9") (pin "2") (pinfunction "2_2") (pintype "unspecified"))
      (node (ref "U5") (pin "29") (pinfunction "PC6(RESET#/PCINT14)_29") (pintype "unspecified"))
    )
    (net (code "176") (name "RESET_ADV7180") (class "Default")
      (node (ref "R36") (pin "2") (pinfunction "2_2") (pintype "unspecified"))
      (node (ref "U13") (pin "26") (pinfunction "IO4_26") (pintype "unspecified"))
      (node (ref "U16") (pin "25") (pinfunction "RESET#_25") (pintype "unspecified"))
    )
    (net (code "177") (name "RSSI") (class "Default")
      (node (ref "CN22") (pin "4") (pinfunction "4_4") (pintype "unspecified"))
      (node (ref "D23") (pin "1") (pinfunction "1_1") (pintype "unspecified"))
      (node (ref "U1") (pin "37") (pinfunction "PC3_C_37") (pintype "unspecified"))
    )
    (net (code "178") (name "RTS") (class "Default")
      (node (ref "Q4") (pin "2") (pinfunction "2_2") (pintype "input"))
      (node (ref "R30") (pin "1") (pinfunction "1_1") (pintype "unspecified"))
      (node (ref "U12") (pin "24") (pinfunction "RTS_24") (pintype "unspecified"))
    )
    (net (code "179") (name "RX_OSD") (class "Default")
      (node (ref "U1") (pin "165") (pinfunction "PB6_165") (pintype "unspecified"))
      (node (ref "U7") (pin "4") (pinfunction "SDA1_4") (pintype "unspecified"))
    )
    (net (code "180") (name "RX_debug_atmega328") (class "Default")
      (node (ref "CN20") (pin "3") (pinfunction "3_3") (pintype "unspecified"))
      (node (ref "U5") (pin "30") (pinfunction "PD0(RXD/PCINT16)_30") (pintype "unspecified"))
      (node (ref "U7") (pin "5") (pinfunction "SDA2_5") (pintype "unspecified"))
    )
    (net (code "181") (name "SBUS{slash}IBUS") (class "Default")
      (node (ref "CN22") (pin "3") (pinfunction "3_3") (pintype "unspecified"))
      (node (ref "D22") (pin "1") (pinfunction "1_1") (pintype "unspecified"))
      (node (ref "U1") (pin "123") (pinfunction "PC7_123") (pintype "unspecified"))
    )
    (net (code "182") (name "SD1") (class "Default")
      (node (ref "U13") (pin "22") (pinfunction "SDI_22") (pintype "unspecified"))
      (node (ref "U9") (pin "5") (pinfunction "SI/SIO[0]_5") (pintype "unspecified"))
    )
    (net (code "183") (name "SD2") (class "Default")
      (node (ref "U13") (pin "17") (pinfunction "SHD/SD2_17") (pintype "unspecified"))
      (node (ref "U9") (pin "7") (pinfunction "SIO[3]_7") (pintype "unspecified"))
    )
    (net (code "184") (name "SD3") (class "Default")
      (node (ref "U13") (pin "18") (pinfunction "SWP/SD3_18") (pintype "unspecified"))
      (node (ref "U9") (pin "3") (pinfunction "SIO[2]_3") (pintype "unspecified"))
    )
    (net (code "185") (name "SDMMC1_0") (class "Default")
      (node (ref "CARD2") (pin "7") (pinfunction "DATA0_7") (pintype "unspecified"))
      (node (ref "D52") (pin "1") (pinfunction "1_1") (pintype "unspecified"))
      (node (ref "R7") (pin "2") (pinfunction "2_2") (pintype "unspecified"))
      (node (ref "U1") (pin "124") (pinfunction "PC8_124") (pintype "unspecified"))
    )
    (net (code "186") (name "SDMMC1_1") (class "Default")
      (node (ref "CARD2") (pin "8") (pinfunction "DATA1_8") (pintype "unspecified"))
      (node (ref "D53") (pin "1") (pinfunction "1_1") (pintype "unspecified"))
      (node (ref "R8") (pin "2") (pinfunction "2_2") (pintype "unspecified"))
      (node (ref "U1") (pin "125") (pinfunction "PC9_125") (pintype "unspecified"))
    )
    (net (code "187") (name "SDMMC1_2") (class "Default")
      (node (ref "CARD2") (pin "1") (pinfunction "DATA2_1") (pintype "unspecified"))
      (node (ref "D56") (pin "1") (pinfunction "1_1") (pintype "unspecified"))
      (node (ref "R4") (pin "2") (pinfunction "2_2") (pintype "unspecified"))
      (node (ref "U1") (pin "140") (pinfunction "PC10_140") (pintype "unspecified"))
    )
    (net (code "188") (name "SDMMC1_3") (class "Default")
      (node (ref "CARD2") (pin "2") (pinfunction "CD/DATA3_2") (pintype "unspecified"))
      (node (ref "D55") (pin "1") (pinfunction "1_1") (pintype "unspecified"))
      (node (ref "R5") (pin "2") (pinfunction "2_2") (pintype "unspecified"))
      (node (ref "U1") (pin "141") (pinfunction "PC11_141") (pintype "unspecified"))
    )
    (net (code "189") (name "SDMMC1_CLK") (class "Default")
      (node (ref "CARD2") (pin "5") (pinfunction "CLK_5") (pintype "unspecified"))
      (node (ref "D51") (pin "1") (pinfunction "1_1") (pintype "unspecified"))
      (node (ref "U1") (pin "142") (pinfunction "PC12_142") (pintype "unspecified"))
    )
    (net (code "190") (name "SDMMC1_CMD") (class "Default")
      (node (ref "CARD2") (pin "3") (pinfunction "CMD_3") (pintype "unspecified"))
      (node (ref "D54") (pin "1") (pinfunction "1_1") (pintype "unspecified"))
      (node (ref "R6") (pin "2") (pinfunction "2_2") (pintype "unspecified"))
      (node (ref "U1") (pin "145") (pinfunction "PD2_145") (pintype "unspecified"))
    )
    (net (code "191") (name "SDO") (class "Default")
      (node (ref "U13") (pin "21") (pinfunction "SDO_21") (pintype "unspecified"))
      (node (ref "U9") (pin "2") (pinfunction "SO/SIO[1]_2") (pintype "unspecified"))
    )
    (net (code "192") (name "SFL") (class "Default")
      (node (ref "U13") (pin "19") (pinfunction "SCS/CMD_19") (pintype "unspecified"))
      (node (ref "U16") (pin "4") (pinfunction "SFL_4") (pintype "unspecified"))
    )
    (net (code "193") (name "SPI4_CS1") (class "Default")
      (node (ref "CN1") (pin "5") (pinfunction "5_5") (pintype "unspecified"))
      (node (ref "D4") (pin "4") (pinfunction "4_4") (pintype "unspecified"))
      (node (ref "U1") (pin "2") (pinfunction "PE3_2") (pintype "unspecified"))
    )
    (net (code "194") (name "SPI4_CS2") (class "Default")
      (node (ref "CN1") (pin "6") (pinfunction "6_6") (pintype "unspecified"))
      (node (ref "D4") (pin "3") (pinfunction "3_3") (pintype "unspecified"))
      (node (ref "U1") (pin "3") (pinfunction "PE4_3") (pintype "unspecified"))
    )
    (net (code "195") (name "SPI4_MISO") (class "Default")
      (node (ref "CN1") (pin "4") (pinfunction "4_4") (pintype "unspecified"))
      (node (ref "D4") (pin "5") (pinfunction "5_5") (pintype "unspecified"))
      (node (ref "U1") (pin "4") (pinfunction "PE5_4") (pintype "unspecified"))
    )
    (net (code "196") (name "SPI4_MOSI") (class "Default")
      (node (ref "CN1") (pin "3") (pinfunction "3_3") (pintype "unspecified"))
      (node (ref "D4") (pin "6") (pinfunction "6_6") (pintype "unspecified"))
      (node (ref "U1") (pin "5") (pinfunction "PE6_5") (pintype "unspecified"))
    )
    (net (code "197") (name "SPI4_SCK") (class "Default")
      (node (ref "CN1") (pin "2") (pinfunction "2_2") (pintype "unspecified"))
      (node (ref "D4") (pin "1") (pinfunction "1_1") (pintype "unspecified"))
      (node (ref "U1") (pin "1") (pinfunction "PE2_1") (pintype "unspecified"))
    )
    (net (code "198") (name "SPI6_CS1") (class "Default")
      (node (ref "CN2") (pin "5") (pinfunction "5_5") (pintype "unspecified"))
      (node (ref "D5") (pin "4") (pinfunction "4_4") (pintype "unspecified"))
      (node (ref "U1") (pin "161") (pinfunction "PG15_161") (pintype "unspecified"))
    )
    (net (code "199") (name "SPI6_CS2") (class "Default")
      (node (ref "CN2") (pin "6") (pinfunction "6_6") (pintype "unspecified"))
      (node (ref "D5") (pin "3") (pinfunction "3_3") (pintype "unspecified"))
      (node (ref "U1") (pin "118") (pinfunction "PG8_118") (pintype "unspecified"))
    )
    (net (code "200") (name "SPI6_MISO") (class "Default")
      (node (ref "CN2") (pin "4") (pinfunction "4_4") (pintype "unspecified"))
      (node (ref "D5") (pin "5") (pinfunction "5_5") (pintype "unspecified"))
      (node (ref "U1") (pin "156") (pinfunction "PG12_156") (pintype "unspecified"))
    )
    (net (code "201") (name "SPI6_MOSI") (class "Default")
      (node (ref "CN2") (pin "3") (pinfunction "3_3") (pintype "unspecified"))
      (node (ref "D5") (pin "6") (pinfunction "6_6") (pintype "unspecified"))
      (node (ref "U1") (pin "158") (pinfunction "PG14_158") (pintype "unspecified"))
    )
    (net (code "202") (name "SPI6_SCK") (class "Default")
      (node (ref "CN2") (pin "2") (pinfunction "2_2") (pintype "unspecified"))
      (node (ref "D5") (pin "1") (pinfunction "1_1") (pintype "unspecified"))
      (node (ref "U1") (pin "157") (pinfunction "PG13_157") (pintype "unspecified"))
    )
    (net (code "203") (name "SPI_CS_BARO") (class "Default")
      (node (ref "U1") (pin "34") (pinfunction "PC0_34") (pintype "unspecified"))
      (node (ref "U2") (pin "6") (pinfunction "CSB_6") (pintype "unspecified"))
    )
    (net (code "204") (name "SPI_SCK_BARO") (class "Default")
      (node (ref "U1") (pin "78") (pinfunction "PB10_78") (pintype "unspecified"))
      (node (ref "U2") (pin "2") (pinfunction "SCK_2") (pintype "unspecified"))
    )
    (net (code "205") (name "SPI_SCL_IMU") (class "Default")
      (node (ref "U1") (pin "155") (pinfunction "PG11_155") (pintype "unspecified"))
      (node (ref "U4") (pin "13") (pinfunction "SCL_13") (pintype "unspecified"))
    )
    (net (code "206") (name "SPI_SDI_BARO") (class "Default")
      (node (ref "U1") (pin "35") (pinfunction "PC1_35") (pintype "unspecified"))
      (node (ref "U2") (pin "4") (pinfunction "SDI_4") (pintype "unspecified"))
    )
    (net (code "207") (name "SPI_SDI_IMU") (class "Default")
      (node (ref "U1") (pin "150") (pinfunction "PD7_150") (pintype "unspecified"))
      (node (ref "U4") (pin "14") (pinfunction "SDA_14") (pintype "unspecified"))
    )
    (net (code "208") (name "SPI_SDO_BARO") (class "Default")
      (node (ref "U1") (pin "36") (pinfunction "PC2_C_36") (pintype "unspecified"))
      (node (ref "U2") (pin "5") (pinfunction "SDO_5") (pintype "unspecified"))
    )
    (net (code "209") (name "SPI_SDO_IMU") (class "Default")
      (node (ref "U1") (pin "153") (pinfunction "PG9_153") (pintype "unspecified"))
      (node (ref "U4") (pin "1") (pinfunction "SDO/SA0_1") (pintype "unspecified"))
    )
    (net (code "210") (name "STM32_DN") (class "Default")
      (node (ref "U1") (pin "130") (pinfunction "PA11_130") (pintype "unspecified"))
      (node (ref "U22") (pin "4") (pinfunction "D2(0)_4") (pintype "unspecified"))
      (node (ref "U23") (pin "A7") (pinfunction "DN1_A7") (pintype "unspecified"))
      (node (ref "U23") (pin "B7") (pinfunction "DN2_B7") (pintype "unspecified"))
    )
    (net (code "211") (name "STM32_DP") (class "Default")
      (node (ref "U1") (pin "131") (pinfunction "PA12_131") (pintype "unspecified"))
      (node (ref "U22") (pin "6") (pinfunction "D1(0)_6") (pintype "unspecified"))
      (node (ref "U23") (pin "A6") (pinfunction "DP1_A6") (pintype "unspecified"))
      (node (ref "U23") (pin "B6") (pinfunction "DP2_B6") (pintype "unspecified"))
    )
    (net (code "212") (name "TWI_SCK") (class "Default")
      (node (ref "FPC1") (pin "20") (pinfunction "20_20") (pintype "unspecified"))
      (node (ref "R17") (pin "1") (pinfunction "1_1") (pintype "unspecified"))
      (node (ref "U13") (pin "12") (pinfunction "IO27_12") (pintype "unspecified"))
      (node (ref "U16") (pin "28") (pinfunction "SCLK_28") (pintype "unspecified"))
    )
    (net (code "213") (name "TWI_SDA") (class "Default")
      (node (ref "FPC1") (pin "22") (pinfunction "22_22") (pintype "unspecified"))
      (node (ref "R16") (pin "1") (pinfunction "1_1") (pintype "unspecified"))
      (node (ref "U13") (pin "11") (pinfunction "IO26_11") (pintype "unspecified"))
      (node (ref "U16") (pin "27") (pinfunction "SDATA_27") (pintype "unspecified"))
    )
    (net (code "214") (name "TX_OSD") (class "Default")
      (node (ref "U1") (pin "164") (pinfunction "PB5_164") (pintype "unspecified"))
      (node (ref "U7") (pin "3") (pinfunction "SCL1_3") (pintype "unspecified"))
    )
    (net (code "215") (name "TX_debug_atmega328") (class "Default")
      (node (ref "CN20") (pin "2") (pinfunction "2_2") (pintype "unspecified"))
      (node (ref "U5") (pin "31") (pinfunction "PD1(TXD/PCINT17)_31") (pintype "unspecified"))
      (node (ref "U7") (pin "6") (pinfunction "SCL2_6") (pintype "unspecified"))
    )
    (net (code "216") (name "U0RX_ESP32") (class "Default")
      (node (ref "R28") (pin "1") (pinfunction "1_1") (pintype "unspecified"))
      (node (ref "U13") (pin "34") (pinfunction "U0RXD_34") (pintype "unspecified"))
    )
    (net (code "217") (name "U0TX_ESP32") (class "Default")
      (node (ref "R29") (pin "1") (pinfunction "1_1") (pintype "unspecified"))
      (node (ref "U13") (pin "35") (pinfunction "U0TXD_35") (pintype "unspecified"))
    )
    (net (code "218") (name "U2RX_ESP32") (class "Default")
      (node (ref "U1") (pin "27") (pinfunction "PF7_27") (pintype "unspecified"))
      (node (ref "U13") (pin "23") (pinfunction "IO15_23") (pintype "unspecified"))
    )
    (net (code "219") (name "U2TX_ESP32") (class "Default")
      (node (ref "U1") (pin "26") (pinfunction "PF6_26") (pintype "unspecified"))
      (node (ref "U13") (pin "24") (pinfunction "IO2_24") (pintype "unspecified"))
    )
    (net (code "220") (name "UART1_RX") (class "Default")
      (node (ref "U1") (pin "88") (pinfunction "PB15_88") (pintype "unspecified"))
      (node (ref "U29") (pin "4") (pinfunction "A3_4") (pintype "unspecified"))
    )
    (net (code "221") (name "UART1_RX_PORT") (class "Default")
      (node (ref "R83") (pin "1") (pinfunction "1_1") (pintype "unspecified"))
      (node (ref "U29") (pin "17") (pinfunction "B3_17") (pintype "unspecified"))
    )
    (net (code "222") (name "UART1_TX") (class "Default")
      (node (ref "U1") (pin "87") (pinfunction "PB14_87") (pintype "unspecified"))
      (node (ref "U29") (pin "3") (pinfunction "A2_3") (pintype "unspecified"))
    )
    (net (code "223") (name "UART1_TX_PORT") (class "Default")
      (node (ref "R82") (pin "1") (pinfunction "1_1") (pintype "unspecified"))
      (node (ref "U29") (pin "18") (pinfunction "B2_18") (pintype "unspecified"))
    )
    (net (code "224") (name "UART2_CTS") (class "Default")
      (node (ref "U1") (pin "146") (pinfunction "PD3_146") (pintype "unspecified"))
      (node (ref "U25") (pin "8") (pinfunction "A7_8") (pintype "unspecified"))
    )
    (net (code "225") (name "UART2_CTS_PORT") (class "Default")
      (node (ref "R80") (pin "1") (pinfunction "1_1") (pintype "unspecified"))
      (node (ref "U25") (pin "13") (pinfunction "B7_13") (pintype "unspecified"))
    )
    (net (code "226") (name "UART2_RTS") (class "Default")
      (node (ref "U1") (pin "147") (pinfunction "PD4_147") (pintype "unspecified"))
      (node (ref "U25") (pin "9") (pinfunction "A8_9") (pintype "unspecified"))
    )
    (net (code "227") (name "UART2_RTS_PORT") (class "Default")
      (node (ref "R81") (pin "1") (pinfunction "1_1") (pintype "unspecified"))
      (node (ref "U25") (pin "12") (pinfunction "B8_12") (pintype "unspecified"))
    )
    (net (code "228") (name "UART2_RX") (class "Default")
      (node (ref "U1") (pin "149") (pinfunction "PD6_149") (pintype "unspecified"))
      (node (ref "U25") (pin "7") (pinfunction "A6_7") (pintype "unspecified"))
    )
    (net (code "229") (name "UART2_RX_PORT") (class "Default")
      (node (ref "R79") (pin "1") (pinfunction "1_1") (pintype "unspecified"))
      (node (ref "U25") (pin "14") (pinfunction "B6_14") (pintype "unspecified"))
    )
    (net (code "230") (name "UART2_TX") (class "Default")
      (node (ref "U1") (pin "148") (pinfunction "PD5_148") (pintype "unspecified"))
      (node (ref "U25") (pin "6") (pinfunction "A5_6") (pintype "unspecified"))
    )
    (net (code "231") (name "UART2_TX_PORT") (class "Default")
      (node (ref "R78") (pin "1") (pinfunction "1_1") (pintype "unspecified"))
      (node (ref "U25") (pin "15") (pinfunction "B5_15") (pintype "unspecified"))
    )
    (net (code "232") (name "UART3_CTS") (class "Default")
      (node (ref "U1") (pin "94") (pinfunction "PD11_94") (pintype "unspecified"))
      (node (ref "U25") (pin "5") (pinfunction "A4_5") (pintype "unspecified"))
    )
    (net (code "233") (name "UART3_CTS_PORT") (class "Default")
      (node (ref "R76") (pin "1") (pinfunction "1_1") (pintype "unspecified"))
      (node (ref "U25") (pin "16") (pinfunction "B4_16") (pintype "unspecified"))
    )
    (net (code "234") (name "UART3_RTS") (class "Default")
      (node (ref "U1") (pin "95") (pinfunction "PD12_95") (pintype "unspecified"))
      (node (ref "U25") (pin "1") (pinfunction "A1_1") (pintype "unspecified"))
    )
    (net (code "235") (name "UART3_RTS_PORT") (class "Default")
      (node (ref "R77") (pin "1") (pinfunction "1_1") (pintype "unspecified"))
      (node (ref "U25") (pin "20") (pinfunction "B1_20") (pintype "unspecified"))
    )
    (net (code "236") (name "UART3_RX") (class "Default")
      (node (ref "U1") (pin "79") (pinfunction "PB11_79") (pintype "unspecified"))
      (node (ref "U25") (pin "3") (pinfunction "A2_3") (pintype "unspecified"))
    )
    (net (code "237") (name "UART3_RX_PORT") (class "Default")
      (node (ref "R75") (pin "1") (pinfunction "1_1") (pintype "unspecified"))
      (node (ref "U25") (pin "18") (pinfunction "B2_18") (pintype "unspecified"))
    )
    (net (code "238") (name "UART3_TX") (class "Default")
      (node (ref "U1") (pin "89") (pinfunction "PD8_89") (pintype "unspecified"))
      (node (ref "U25") (pin "4") (pinfunction "A3_4") (pintype "unspecified"))
    )
    (net (code "239") (name "UART3_TX_PORT") (class "Default")
      (node (ref "R74") (pin "1") (pinfunction "1_1") (pintype "unspecified"))
      (node (ref "U25") (pin "17") (pinfunction "B3_17") (pintype "unspecified"))
    )
    (net (code "240") (name "UART8_RX") (class "Default")
      (node (ref "U1") (pin "170") (pinfunction "PE0_170") (pintype "unspecified"))
      (node (ref "U29") (pin "5") (pinfunction "A4_5") (pintype "unspecified"))
    )
    (net (code "241") (name "UART8_RX_PORT") (class "Default")
      (node (ref "R85") (pin "1") (pinfunction "1_1") (pintype "unspecified"))
      (node (ref "U29") (pin "16") (pinfunction "B4_16") (pintype "unspecified"))
    )
    (net (code "242") (name "UART8_TX") (class "Default")
      (node (ref "U1") (pin "171") (pinfunction "PE1_171") (pintype "unspecified"))
      (node (ref "U29") (pin "6") (pinfunction "A5_6") (pintype "unspecified"))
    )
    (net (code "243") (name "UART8_TX_PORT") (class "Default")
      (node (ref "R84") (pin "1") (pinfunction "1_1") (pintype "unspecified"))
      (node (ref "U29") (pin "15") (pinfunction "B5_15") (pintype "unspecified"))
    )
    (net (code "244") (name "VBUS_ESP") (class "Default")
      (node (ref "D64") (pin "1") (pinfunction "1_1") (pintype "unspecified"))
      (node (ref "U10") (pin "A4B9") (pinfunction "VBUS_A4B9") (pintype "unspecified"))
      (node (ref "U10") (pin "B4A9") (pinfunction "VBUS_B4A9") (pintype "unspecified"))
      (node (ref "U14") (pin "1") (pinfunction "1_1") (pintype "unspecified"))
    )
    (net (code "245") (name "VBUS_ESP32") (class "Default")
      (node (ref "R62") (pin "1") (pinfunction "1_1") (pintype "input"))
      (node (ref "U12") (pin "8") (pinfunction "VBUS_8") (pintype "unspecified"))
      (node (ref "U14") (pin "2") (pinfunction "2_2") (pintype "unspecified"))
    )
    (net (code "246") (name "VBUS_STM32") (class "Default")
      (node (ref "D3") (pin "2") (pinfunction "A_2") (pintype "unspecified"))
      (node (ref "R64") (pin "2") (pinfunction "2_2") (pintype "unspecified"))
      (node (ref "U22") (pin "5") (pinfunction "VBUS_5") (pintype "unspecified"))
      (node (ref "U23") (pin "A4B9") (pinfunction "VBUS_A4B9") (pintype "unspecified"))
      (node (ref "U23") (pin "B4A9") (pinfunction "VBUS_B4A9") (pintype "unspecified"))
    )
    (net (code "247") (name "VCAP_1") (class "Default")
      (node (ref "C23") (pin "2") (pinfunction "2_2") (pintype "unspecified"))
      (node (ref "C25") (pin "2") (pinfunction "2_2") (pintype "unspecified"))
      (node (ref "U1") (pin "133") (pinfunction "VCAP_133") (pintype "unspecified"))
      (node (ref "U1") (pin "172") (pinfunction "VCAP_172") (pintype "unspecified"))
      (node (ref "U1") (pin "80") (pinfunction "VCAP_80") (pintype "unspecified"))
    )
    (net (code "248") (name "VDDA") (class "Default")
      (node (ref "C24") (pin "1") (pinfunction "1_1") (pintype "unspecified"))
      (node (ref "C28") (pin "1") (pinfunction "1_1") (pintype "input"))
      (node (ref "L1") (pin "2") (pinfunction "2_2") (pintype "unspecified"))
      (node (ref "R40") (pin "1") (pinfunction "1_1") (pintype "unspecified"))
      (node (ref "U1") (pin "40") (pinfunction "VDDA_40") (pintype "unspecified"))
    )
    (net (code "249") (name "VIN") (class "Default")
      (node (ref "C81") (pin "1") (pinfunction "1_1") (pintype "unspecified"))
      (node (ref "C83") (pin "2") (pinfunction "2_2") (pintype "unspecified"))
      (node (ref "C94") (pin "2") (pinfunction "2_2") (pintype "input"))
      (node (ref "D1") (pin "1") (pinfunction "C_1") (pintype "unspecified"))
      (node (ref "D14") (pin "1") (pinfunction "C_1") (pintype "unspecified"))
      (node (ref "D3") (pin "1") (pinfunction "C_1") (pintype "unspecified"))
      (node (ref "R37") (pin "2") (pinfunction "2_2") (pintype "unspecified"))
      (node (ref "R38") (pin "2") (pinfunction "2_2") (pintype "unspecified"))
      (node (ref "R92") (pin "1") (pinfunction "1_1") (pintype "unspecified"))
      (node (ref "U19") (pin "8") (pinfunction "VIN_8") (pintype "unspecified"))
      (node (ref "U20") (pin "8") (pinfunction "VIN_8") (pintype "unspecified"))
      (node (ref "U24") (pin "6") (pinfunction "IN_6") (pintype "unspecified"))
    )
    (net (code "250") (name "VOLTAGE_SENSE_1") (class "Default")
      (node (ref "CN17") (pin "4") (pinfunction "4_4") (pintype "unspecified"))
      (node (ref "D62") (pin "1") (pinfunction "1_1") (pintype "unspecified"))
      (node (ref "U1") (pin "51") (pinfunction "PA6_51") (pintype "unspecified"))
    )
    (net (code "251") (name "VOLTAGE_SENSE_2") (class "Default")
      (node (ref "CN15") (pin "4") (pinfunction "4_4") (pintype "unspecified"))
      (node (ref "D60") (pin "1") (pinfunction "1_1") (pintype "unspecified"))
      (node (ref "U1") (pin "58") (pinfunction "PF11_58") (pintype "unspecified"))
    )
    (net (code "252") (name "VSYNC") (class "Default")
      (node (ref "R11") (pin "2") (pinfunction "2_2") (pintype "unspecified"))
      (node (ref "U5") (pin "32") (pinfunction "PD2(INT0/PCINT18)_32") (pintype "unspecified"))
      (node (ref "U6") (pin "17") (pinfunction "VSYNC#_17") (pintype "unspecified"))
    )
    (net (code "253") (name "Video_IN") (class "Default")
      (node (ref "C51") (pin "2") (pinfunction "2_2") (pintype "input"))
      (node (ref "CN19") (pin "2") (pinfunction "2_2") (pintype "unspecified"))
      (node (ref "D58") (pin "1") (pinfunction "1_1") (pintype "unspecified"))
      (node (ref "R14") (pin "2") (pinfunction "2_2") (pintype "unspecified"))
    )
    (net (code "254") (name "Video_OUT") (class "Default")
      (node (ref "CN18") (pin "2") (pinfunction "2_2") (pintype "unspecified"))
      (node (ref "D57") (pin "1") (pinfunction "1_1") (pintype "unspecified"))
      (node (ref "R13") (pin "2") (pinfunction "2_2") (pintype "unspecified"))
      (node (ref "R34") (pin "2") (pinfunction "2_2") (pintype "unspecified"))
    )
    (net (code "255") (name "XFB") (class "Default")
      (node (ref "U6") (pin "6") (pinfunction "XFB_6") (pintype "unspecified"))
      (node (ref "X4") (pin "1") (pinfunction "OSC1_1") (pintype "input"))
    )
    (net (code "256") (name "XTAL") (class "Default")
      (node (ref "C63") (pin "1") (pinfunction "1_1") (pintype "unspecified"))
      (node (ref "R22") (pin "2") (pinfunction "2_2") (pintype "unspecified"))
      (node (ref "U16") (pin "13") (pinfunction "XTAL_13") (pintype "unspecified"))
      (node (ref "X5") (pin "1") (pinfunction "1_1") (pintype "input"))
    )
    (net (code "257") (name "XTAL1") (class "Default")
      (node (ref "C64") (pin "2") (pinfunction "2_2") (pintype "unspecified"))
      (node (ref "R22") (pin "1") (pinfunction "1_1") (pintype "unspecified"))
      (node (ref "U16") (pin "12") (pinfunction "XTAL1_12") (pintype "unspecified"))
      (node (ref "X5") (pin "3") (pinfunction "3_3") (pintype "input"))
    )
    (net (code "258") (name "unconnected-(FPC1-Pad1)") (class "Default")
      (node (ref "FPC1") (pin "1") (pinfunction "1_1") (pintype "unspecified+no_connect"))
    )
    (net (code "259") (name "unconnected-(FPC1-Pad2)") (class "Default")
      (node (ref "FPC1") (pin "2") (pinfunction "2_2") (pintype "unspecified+no_connect"))
    )
    (net (code "260") (name "unconnected-(FPC1-Pad24)") (class "Default")
      (node (ref "FPC1") (pin "24") (pinfunction "24_24") (pintype "unspecified+no_connect"))
    )
    (net (code "261") (name "unconnected-(U1-DSI_CKN-Pad107)") (class "Default")
      (node (ref "U1") (pin "107") (pinfunction "DSI_CKN_107") (pintype "unspecified+no_connect"))
    )
    (net (code "262") (name "unconnected-(U1-DSI_CKP-Pad106)") (class "Default")
      (node (ref "U1") (pin "106") (pinfunction "DSI_CKP_106") (pintype "unspecified+no_connect"))
    )
    (net (code "263") (name "unconnected-(U1-DSI_D0N-Pad104)") (class "Default")
      (node (ref "U1") (pin "104") (pinfunction "DSI_D0N_104") (pintype "unspecified+no_connect"))
    )
    (net (code "264") (name "unconnected-(U1-DSI_D0P-Pad103)") (class "Default")
      (node (ref "U1") (pin "103") (pinfunction "DSI_D0P_103") (pintype "unspecified+no_connect"))
    )
    (net (code "265") (name "unconnected-(U1-PA10-Pad129)") (class "Default")
      (node (ref "U1") (pin "129") (pinfunction "PA10_129") (pintype "unspecified+no_connect"))
    )
    (net (code "266") (name "unconnected-(U1-PB2-Pad57)") (class "Default")
      (node (ref "U1") (pin "57") (pinfunction "PB2_57") (pintype "unspecified+no_connect"))
    )
    (net (code "267") (name "unconnected-(U1-PB7-Pad166)") (class "Default")
      (node (ref "U1") (pin "166") (pinfunction "PB7_166") (pintype "unspecified+no_connect"))
    )
    (net (code "268") (name "unconnected-(U1-PC5-Pad54)") (class "Default")
      (node (ref "U1") (pin "54") (pinfunction "PC5_54") (pintype "unspecified+no_connect"))
    )
    (net (code "269") (name "unconnected-(U1-PC13-Pad9)") (class "Default")
      (node (ref "U1") (pin "9") (pinfunction "PC13_9") (pintype "unspecified+no_connect"))
    )
    (net (code "270") (name "unconnected-(U1-PD9-Pad90)") (class "Default")
      (node (ref "U1") (pin "90") (pinfunction "PD9_90") (pintype "unspecified+no_connect"))
    )
    (net (code "271") (name "unconnected-(U1-PD10-Pad91)") (class "Default")
      (node (ref "U1") (pin "91") (pinfunction "PD10_91") (pintype "unspecified+no_connect"))
    )
    (net (code "272") (name "unconnected-(U1-PD15-Pad98)") (class "Default")
      (node (ref "U1") (pin "98") (pinfunction "PD15_98") (pintype "unspecified+no_connect"))
    )
    (net (code "273") (name "unconnected-(U1-PE7-Pad67)") (class "Default")
      (node (ref "U1") (pin "67") (pinfunction "PE7_67") (pintype "unspecified+no_connect"))
    )
    (net (code "274") (name "unconnected-(U1-PE8-Pad68)") (class "Default")
      (node (ref "U1") (pin "68") (pinfunction "PE8_68") (pintype "unspecified+no_connect"))
    )
    (net (code "275") (name "unconnected-(U1-PE10-Pad72)") (class "Default")
      (node (ref "U1") (pin "72") (pinfunction "PE10_72") (pintype "unspecified+no_connect"))
    )
    (net (code "276") (name "unconnected-(U1-PE12-Pad74)") (class "Default")
      (node (ref "U1") (pin "74") (pinfunction "PE12_74") (pintype "unspecified+no_connect"))
    )
    (net (code "277") (name "unconnected-(U1-PE15-Pad77)") (class "Default")
      (node (ref "U1") (pin "77") (pinfunction "PE15_77") (pintype "unspecified+no_connect"))
    )
    (net (code "278") (name "unconnected-(U1-PF2-Pad20)") (class "Default")
      (node (ref "U1") (pin "20") (pinfunction "PF2_20") (pintype "unspecified+no_connect"))
    )
    (net (code "279") (name "unconnected-(U1-PF4-Pad22)") (class "Default")
      (node (ref "U1") (pin "22") (pinfunction "PF4_22") (pintype "unspecified+no_connect"))
    )
    (net (code "280") (name "unconnected-(U1-PF10-Pad30)") (class "Default")
      (node (ref "U1") (pin "30") (pinfunction "PF10_30") (pintype "unspecified+no_connect"))
    )
    (net (code "281") (name "unconnected-(U1-PF12-Pad59)") (class "Default")
      (node (ref "U1") (pin "59") (pinfunction "PF12_59") (pintype "unspecified+no_connect"))
    )
    (net (code "282") (name "unconnected-(U1-PG0-Pad63)") (class "Default")
      (node (ref "U1") (pin "63") (pinfunction "PG0_63") (pintype "unspecified+no_connect"))
    )
    (net (code "283") (name "unconnected-(U1-PG1-Pad66)") (class "Default")
      (node (ref "U1") (pin "66") (pinfunction "PG1_66") (pintype "unspecified+no_connect"))
    )
    (net (code "284") (name "unconnected-(U1-PG3-Pad111)") (class "Default")
      (node (ref "U1") (pin "111") (pinfunction "PG3_111") (pintype "unspecified+no_connect"))
    )
    (net (code "285") (name "unconnected-(U1-PG7-Pad117)") (class "Default")
      (node (ref "U1") (pin "117") (pinfunction "PG7_117") (pintype "unspecified+no_connect"))
    )
    (net (code "286") (name "unconnected-(U1-VCAPDSI-Pad101)") (class "Default")
      (node (ref "U1") (pin "101") (pinfunction "VCAPDSI_101") (pintype "unspecified+no_connect"))
    )
    (net (code "287") (name "unconnected-(U1-VDD12DSI-Pad102)") (class "Default")
      (node (ref "U1") (pin "102") (pinfunction "VDD12DSI_102") (pintype "unspecified+no_connect"))
    )
    (net (code "288") (name "unconnected-(U1-VDD12DSI-Pad108)") (class "Default")
      (node (ref "U1") (pin "108") (pinfunction "VDD12DSI_108") (pintype "unspecified+no_connect"))
    )
    (net (code "289") (name "unconnected-(U1-VDDSMPS-Pad16)") (class "Default")
      (node (ref "U1") (pin "16") (pinfunction "VDDSMPS_16") (pintype "unspecified+no_connect"))
    )
    (net (code "290") (name "unconnected-(U1-VFBSMPs-Pad17)") (class "Default")
      (node (ref "U1") (pin "17") (pinfunction "VFBSMPs_17") (pintype "unspecified+no_connect"))
    )
    (net (code "291") (name "unconnected-(U1-VLXSMPS-Pad15)") (class "Default")
      (node (ref "U1") (pin "15") (pinfunction "VLXSMPS_15") (pintype "unspecified+no_connect"))
    )
    (net (code "292") (name "unconnected-(U2-INT-Pad7)") (class "Default")
      (node (ref "U2") (pin "7") (pinfunction "INT_7") (pintype "unspecified+no_connect"))
    )
    (net (code "293") (name "unconnected-(U3-DRDY-Pad15)") (class "Default")
      (node (ref "U3") (pin "15") (pinfunction "DRDY_15") (pintype "unspecified+no_connect"))
    )
    (net (code "294") (name "unconnected-(U3-NC-Pad3)") (class "Default")
      (node (ref "U3") (pin "3") (pinfunction "NC_3") (pintype "unspecified+no_connect"))
    )
    (net (code "295") (name "unconnected-(U3-NC-Pad5)") (class "Default")
      (node (ref "U3") (pin "5") (pinfunction "NC_5") (pintype "unspecified+no_connect"))
    )
    (net (code "296") (name "unconnected-(U3-NC-Pad6)") (class "Default")
      (node (ref "U3") (pin "6") (pinfunction "NC_6") (pintype "unspecified+no_connect"))
    )
    (net (code "297") (name "unconnected-(U3-NC-Pad7)") (class "Default")
      (node (ref "U3") (pin "7") (pinfunction "NC_7") (pintype "unspecified+no_connect"))
    )
    (net (code "298") (name "unconnected-(U3-NC-Pad14)") (class "Default")
      (node (ref "U3") (pin "14") (pinfunction "NC_14") (pintype "unspecified+no_connect"))
    )
    (net (code "299") (name "unconnected-(U4-INT1-Pad4)") (class "Default")
      (node (ref "U4") (pin "4") (pinfunction "INT1_4") (pintype "unspecified+no_connect"))
    )
    (net (code "300") (name "unconnected-(U4-INT2-Pad9)") (class "Default")
      (node (ref "U4") (pin "9") (pinfunction "INT2_9") (pintype "unspecified+no_connect"))
    )
    (net (code "301") (name "unconnected-(U4-OCS_Aux-Pad10)") (class "Default")
      (node (ref "U4") (pin "10") (pinfunction "OCS_Aux_10") (pintype "unspecified+no_connect"))
    )
    (net (code "302") (name "unconnected-(U4-SDO_Aux-Pad11)") (class "Default")
      (node (ref "U4") (pin "11") (pinfunction "SDO_Aux_11") (pintype "unspecified+no_connect"))
    )
    (net (code "303") (name "unconnected-(U5-(PCINT20{slash}XCK{slash}T0)PD4-Pad2)") (class "Default")
      (node (ref "U5") (pin "2") (pinfunction "(PCINT20/XCK/T0)PD4_2") (pintype "unspecified+no_connect"))
    )
    (net (code "304") (name "unconnected-(U5-ADC6-Pad19)") (class "Default")
      (node (ref "U5") (pin "19") (pinfunction "ADC6_19") (pintype "unspecified+no_connect"))
    )
    (net (code "305") (name "unconnected-(U5-ADC7-Pad22)") (class "Default")
      (node (ref "U5") (pin "22") (pinfunction "ADC7_22") (pintype "unspecified+no_connect"))
    )
    (net (code "306") (name "unconnected-(U5-AREF-Pad20)") (class "Default")
      (node (ref "U5") (pin "20") (pinfunction "AREF_20") (pintype "unspecified+no_connect"))
    )
    (net (code "307") (name "unconnected-(U5-PC0(ADC0{slash}PCINT8)-Pad23)") (class "Default")
      (node (ref "U5") (pin "23") (pinfunction "PC0(ADC0/PCINT8)_23") (pintype "unspecified+no_connect"))
    )
    (net (code "308") (name "unconnected-(U5-PC3(ADC3{slash}PCINT11)-Pad26)") (class "Default")
      (node (ref "U5") (pin "26") (pinfunction "PC3(ADC3/PCINT11)_26") (pintype "unspecified+no_connect"))
    )
    (net (code "309") (name "unconnected-(U6-CLKOUT-Pad7)") (class "Default")
      (node (ref "U6") (pin "7") (pinfunction "CLKOUT_7") (pintype "unspecified+no_connect"))
    )
    (net (code "310") (name "unconnected-(U6-NC-Pad1)") (class "Default")
      (node (ref "U6") (pin "1") (pinfunction "NC_1") (pintype "unspecified+no_connect"))
    )
    (net (code "311") (name "unconnected-(U6-NC-Pad2)") (class "Default")
      (node (ref "U6") (pin "2") (pinfunction "NC_2") (pintype "unspecified+no_connect"))
    )
    (net (code "312") (name "unconnected-(U6-NC-Pad14)") (class "Default")
      (node (ref "U6") (pin "14") (pinfunction "NC_14") (pintype "unspecified+no_connect"))
    )
    (net (code "313") (name "unconnected-(U6-NC-Pad15)") (class "Default")
      (node (ref "U6") (pin "15") (pinfunction "NC_15") (pintype "unspecified+no_connect"))
    )
    (net (code "314") (name "unconnected-(U6-NC-Pad16)") (class "Default")
      (node (ref "U6") (pin "16") (pinfunction "NC_16") (pintype "unspecified+no_connect"))
    )
    (net (code "315") (name "unconnected-(U6-NC-Pad27)") (class "Default")
      (node (ref "U6") (pin "27") (pinfunction "NC_27") (pintype "unspecified+no_connect"))
    )
    (net (code "316") (name "unconnected-(U6-NC-Pad28)") (class "Default")
      (node (ref "U6") (pin "28") (pinfunction "NC_28") (pintype "unspecified+no_connect"))
    )
    (net (code "317") (name "unconnected-(U6-SYNC_IN-Pad13)") (class "Default")
      (node (ref "U6") (pin "13") (pinfunction "SYNC_IN_13") (pintype "unspecified+no_connect"))
    )
    (net (code "318") (name "unconnected-(U10-SBU1-PadA8)") (class "Default")
      (node (ref "U10") (pin "A8") (pinfunction "SBU1_A8") (pintype "unspecified+no_connect"))
    )
    (net (code "319") (name "unconnected-(U10-SBU2-PadB8)") (class "Default")
      (node (ref "U10") (pin "B8") (pinfunction "SBU2_B8") (pintype "unspecified+no_connect"))
    )
    (net (code "320") (name "unconnected-(U12-CTS-Pad23)") (class "Default")
      (node (ref "U12") (pin "23") (pinfunction "CTS_23") (pintype "unspecified+no_connect"))
    )
    (net (code "321") (name "unconnected-(U12-DCD-Pad1)") (class "Default")
      (node (ref "U12") (pin "1") (pinfunction "DCD_1") (pintype "unspecified+no_connect"))
    )
    (net (code "322") (name "unconnected-(U12-DSR-Pad27)") (class "Default")
      (node (ref "U12") (pin "27") (pinfunction "DSR_27") (pintype "unspecified+no_connect"))
    )
    (net (code "323") (name "unconnected-(U12-NC-Pad10)") (class "Default")
      (node (ref "U12") (pin "10") (pinfunction "NC_10") (pintype "unspecified+no_connect"))
    )
    (net (code "324") (name "unconnected-(U12-NC-Pad13)") (class "Default")
      (node (ref "U12") (pin "13") (pinfunction "NC_13") (pintype "unspecified+no_connect"))
    )
    (net (code "325") (name "unconnected-(U12-NC-Pad14)") (class "Default")
      (node (ref "U12") (pin "14") (pinfunction "NC_14") (pintype "unspecified+no_connect"))
    )
    (net (code "326") (name "unconnected-(U12-NC-Pad15)") (class "Default")
      (node (ref "U12") (pin "15") (pinfunction "NC_15") (pintype "unspecified+no_connect"))
    )
    (net (code "327") (name "unconnected-(U12-NC-Pad16)") (class "Default")
      (node (ref "U12") (pin "16") (pinfunction "NC_16") (pintype "unspecified+no_connect"))
    )
    (net (code "328") (name "unconnected-(U12-NC-Pad17)") (class "Default")
      (node (ref "U12") (pin "17") (pinfunction "NC_17") (pintype "unspecified+no_connect"))
    )
    (net (code "329") (name "unconnected-(U12-NC-Pad18)") (class "Default")
      (node (ref "U12") (pin "18") (pinfunction "NC_18") (pintype "unspecified+no_connect"))
    )
    (net (code "330") (name "unconnected-(U12-NC-Pad19)") (class "Default")
      (node (ref "U12") (pin "19") (pinfunction "NC_19") (pintype "unspecified+no_connect"))
    )
    (net (code "331") (name "unconnected-(U12-NC-Pad20)") (class "Default")
      (node (ref "U12") (pin "20") (pinfunction "NC_20") (pintype "unspecified+no_connect"))
    )
    (net (code "332") (name "unconnected-(U12-NC-Pad21)") (class "Default")
      (node (ref "U12") (pin "21") (pinfunction "NC_21") (pintype "unspecified+no_connect"))
    )
    (net (code "333") (name "unconnected-(U12-NC-Pad22)") (class "Default")
      (node (ref "U12") (pin "22") (pinfunction "NC_22") (pintype "unspecified+no_connect"))
    )
    (net (code "334") (name "unconnected-(U12-RI-Pad2)") (class "Default")
      (node (ref "U12") (pin "2") (pinfunction "RI_2") (pintype "unspecified+no_connect"))
    )
    (net (code "335") (name "unconnected-(U12-SUSPEND#-Pad11)") (class "Default")
      (node (ref "U12") (pin "11") (pinfunction "SUSPEND#_11") (pintype "unspecified+no_connect"))
    )
    (net (code "336") (name "unconnected-(U12-SUSPEND-Pad12)") (class "Default")
      (node (ref "U12") (pin "12") (pinfunction "SUSPEND_12") (pintype "unspecified+no_connect"))
    )
    (net (code "337") (name "unconnected-(U13-IO12-Pad14)") (class "Default")
      (node (ref "U13") (pin "14") (pinfunction "IO12_14") (pintype "unspecified+no_connect"))
    )
    (net (code "338") (name "unconnected-(U13-IO13-Pad16)") (class "Default")
      (node (ref "U13") (pin "16") (pinfunction "IO13_16") (pintype "unspecified+no_connect"))
    )
    (net (code "339") (name "unconnected-(U13-IO14-Pad13)") (class "Default")
      (node (ref "U13") (pin "13") (pinfunction "IO14_13") (pintype "unspecified+no_connect"))
    )
    (net (code "340") (name "unconnected-(U13-IO33-Pad9)") (class "Default")
      (node (ref "U13") (pin "9") (pinfunction "IO33_9") (pintype "unspecified+no_connect"))
    )
    (net (code "341") (name "unconnected-(U13-NC-Pad32)") (class "Default")
      (node (ref "U13") (pin "32") (pinfunction "NC_32") (pintype "unspecified+no_connect"))
    )
    (net (code "342") (name "unconnected-(U13-SCK{slash}CLK-Pad20)") (class "Default")
      (node (ref "U13") (pin "20") (pinfunction "SCK/CLK_20") (pintype "unspecified+no_connect"))
    )
    (net (code "343") (name "unconnected-(U16-AIN2-Pad23)") (class "Default")
      (node (ref "U16") (pin "23") (pinfunction "AIN2_23") (pintype "unspecified+no_connect"))
    )
    (net (code "344") (name "unconnected-(U16-AIN3-Pad24)") (class "Default")
      (node (ref "U16") (pin "24") (pinfunction "AIN3_24") (pintype "unspecified+no_connect"))
    )
    (net (code "345") (name "unconnected-(U19-NC-Pad3)") (class "Default")
      (node (ref "U19") (pin "3") (pinfunction "NC_3") (pintype "unspecified+no_connect"))
    )
    (net (code "346") (name "unconnected-(U19-NC-Pad5)") (class "Default")
      (node (ref "U19") (pin "5") (pinfunction "NC_5") (pintype "unspecified+no_connect"))
    )
    (net (code "347") (name "unconnected-(U19-NC-Pad6)") (class "Default")
      (node (ref "U19") (pin "6") (pinfunction "NC_6") (pintype "unspecified+no_connect"))
    )
    (net (code "348") (name "unconnected-(U19-NC-Pad7)") (class "Default")
      (node (ref "U19") (pin "7") (pinfunction "NC_7") (pintype "unspecified+no_connect"))
    )
    (net (code "349") (name "unconnected-(U20-NC-Pad3)") (class "Default")
      (node (ref "U20") (pin "3") (pinfunction "NC_3") (pintype "unspecified+no_connect"))
    )
    (net (code "350") (name "unconnected-(U20-NC-Pad5)") (class "Default")
      (node (ref "U20") (pin "5") (pinfunction "NC_5") (pintype "unspecified+no_connect"))
    )
    (net (code "351") (name "unconnected-(U20-NC-Pad6)") (class "Default")
      (node (ref "U20") (pin "6") (pinfunction "NC_6") (pintype "unspecified+no_connect"))
    )
    (net (code "352") (name "unconnected-(U20-NC-Pad7)") (class "Default")
      (node (ref "U20") (pin "7") (pinfunction "NC_7") (pintype "unspecified+no_connect"))
    )
    (net (code "353") (name "unconnected-(U22-D1(i)-Pad1)") (class "Default")
      (node (ref "U22") (pin "1") (pinfunction "D1(i)_1") (pintype "unspecified+no_connect"))
    )
    (net (code "354") (name "unconnected-(U22-D2(i)-Pad3)") (class "Default")
      (node (ref "U22") (pin "3") (pinfunction "D2(i)_3") (pintype "unspecified+no_connect"))
    )
    (net (code "355") (name "unconnected-(U23-SBU1-PadA8)") (class "Default")
      (node (ref "U23") (pin "A8") (pinfunction "SBU1_A8") (pintype "unspecified+no_connect"))
    )
    (net (code "356") (name "unconnected-(U23-SBU2-PadB8)") (class "Default")
      (node (ref "U23") (pin "B8") (pinfunction "SBU2_B8") (pintype "unspecified+no_connect"))
    )
    (net (code "357") (name "unconnected-(U29-A1-Pad1)") (class "Default")
      (node (ref "U29") (pin "1") (pinfunction "A1_1") (pintype "unspecified+no_connect"))
    )
    (net (code "358") (name "unconnected-(U29-A6-Pad7)") (class "Default")
      (node (ref "U29") (pin "7") (pinfunction "A6_7") (pintype "unspecified+no_connect"))
    )
    (net (code "359") (name "unconnected-(U29-A7-Pad8)") (class "Default")
      (node (ref "U29") (pin "8") (pinfunction "A7_8") (pintype "unspecified+no_connect"))
    )
    (net (code "360") (name "unconnected-(U29-A8-Pad9)") (class "Default")
      (node (ref "U29") (pin "9") (pinfunction "A8_9") (pintype "unspecified+no_connect"))
    )
    (net (code "361") (name "unconnected-(U29-B1-Pad20)") (class "Default")
      (node (ref "U29") (pin "20") (pinfunction "B1_20") (pintype "unspecified+no_connect"))
    )
    (net (code "362") (name "unconnected-(U29-B6-Pad14)") (class "Default")
      (node (ref "U29") (pin "14") (pinfunction "B6_14") (pintype "unspecified+no_connect"))
    )
    (net (code "363") (name "unconnected-(U29-B7-Pad13)") (class "Default")
      (node (ref "U29") (pin "13") (pinfunction "B7_13") (pintype "unspecified+no_connect"))
    )
    (net (code "364") (name "unconnected-(U29-B8-Pad12)") (class "Default")
      (node (ref "U29") (pin "12") (pinfunction "B8_12") (pintype "unspecified+no_connect"))
    )
  )
)
